# G80_a.net
KiCad netlist of a schematic drawn in EAGLE
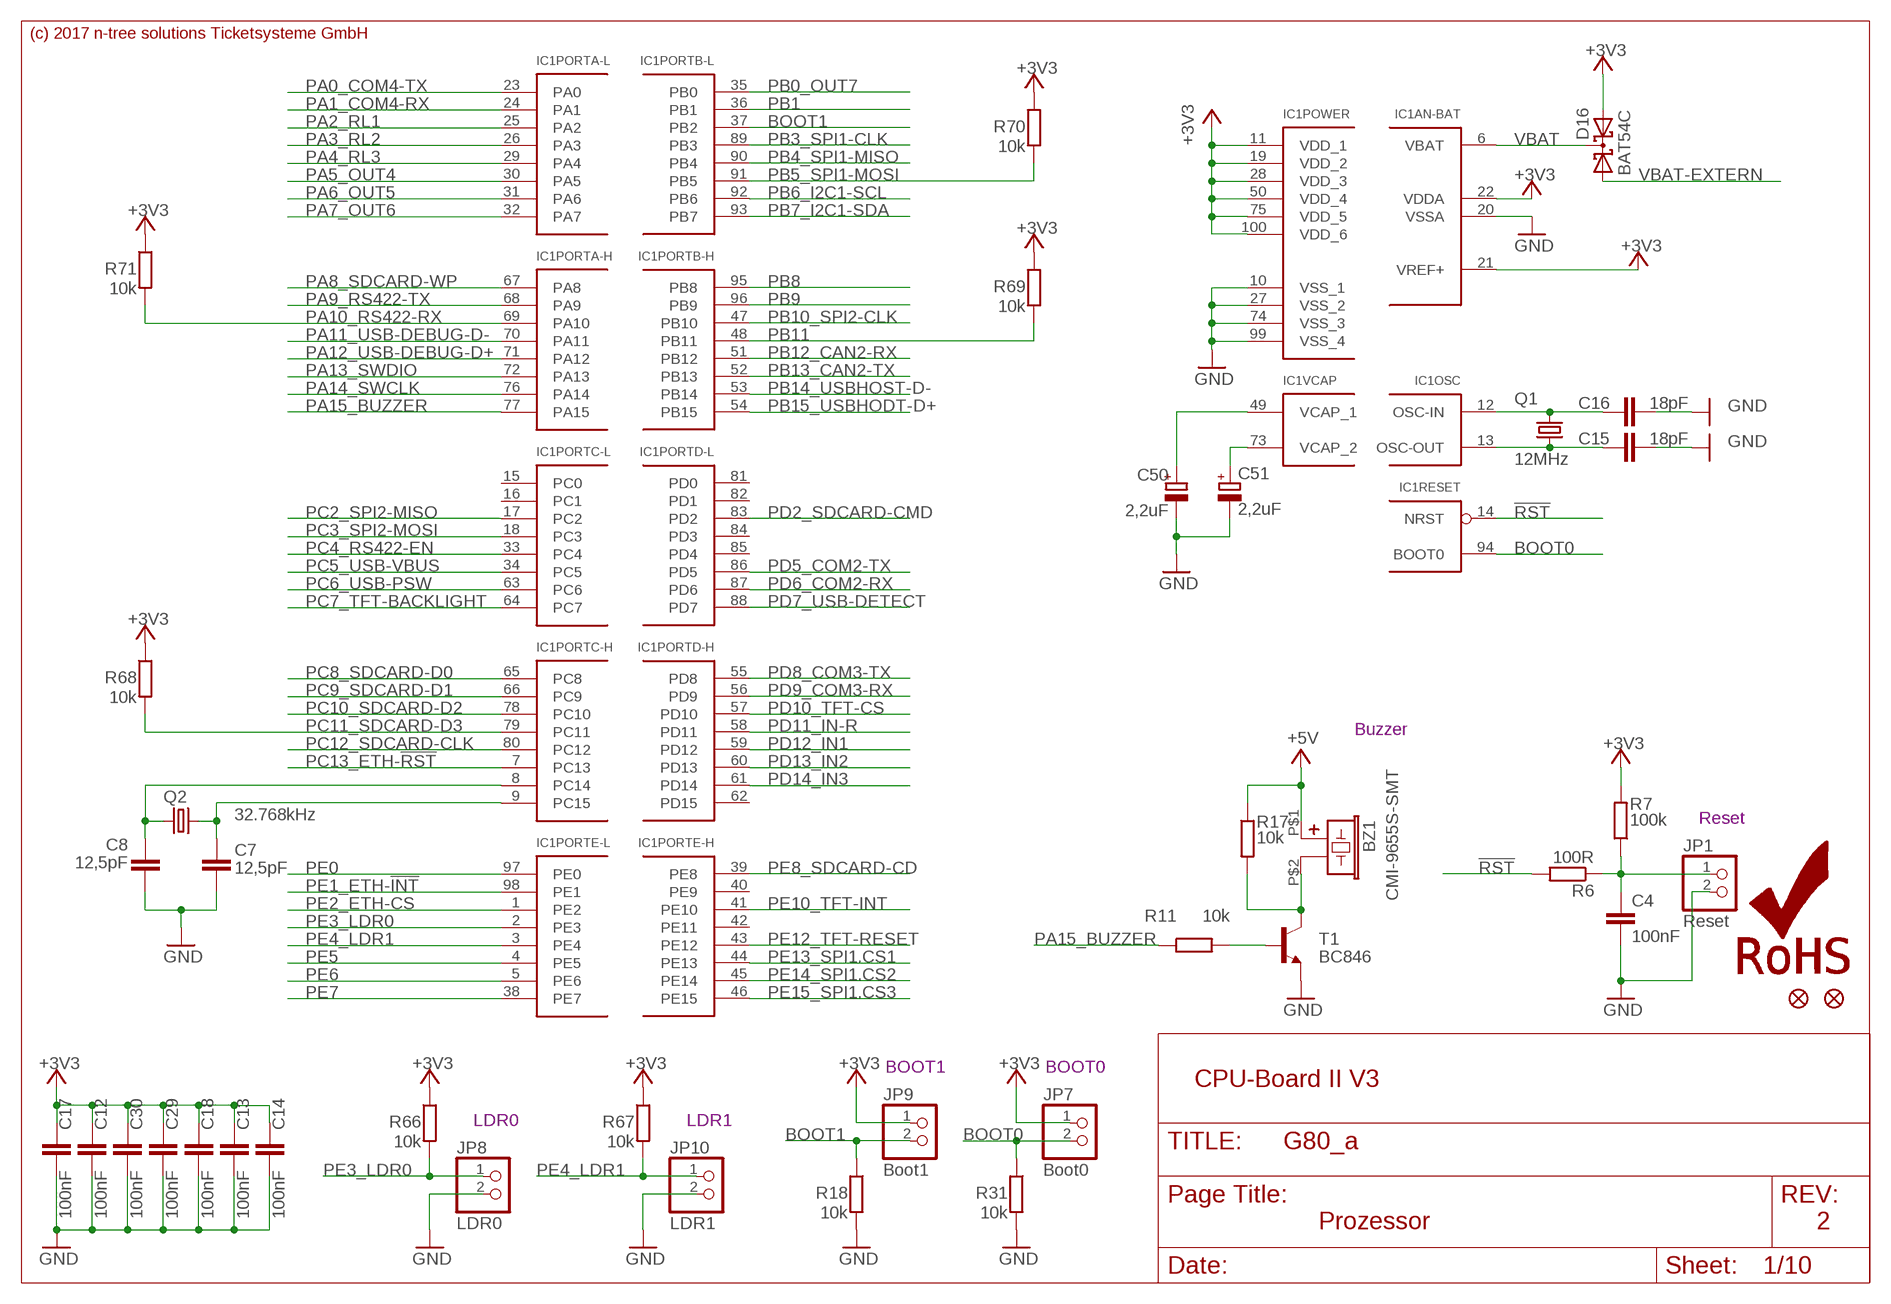
[diagram p0: schematic, sheet 1]
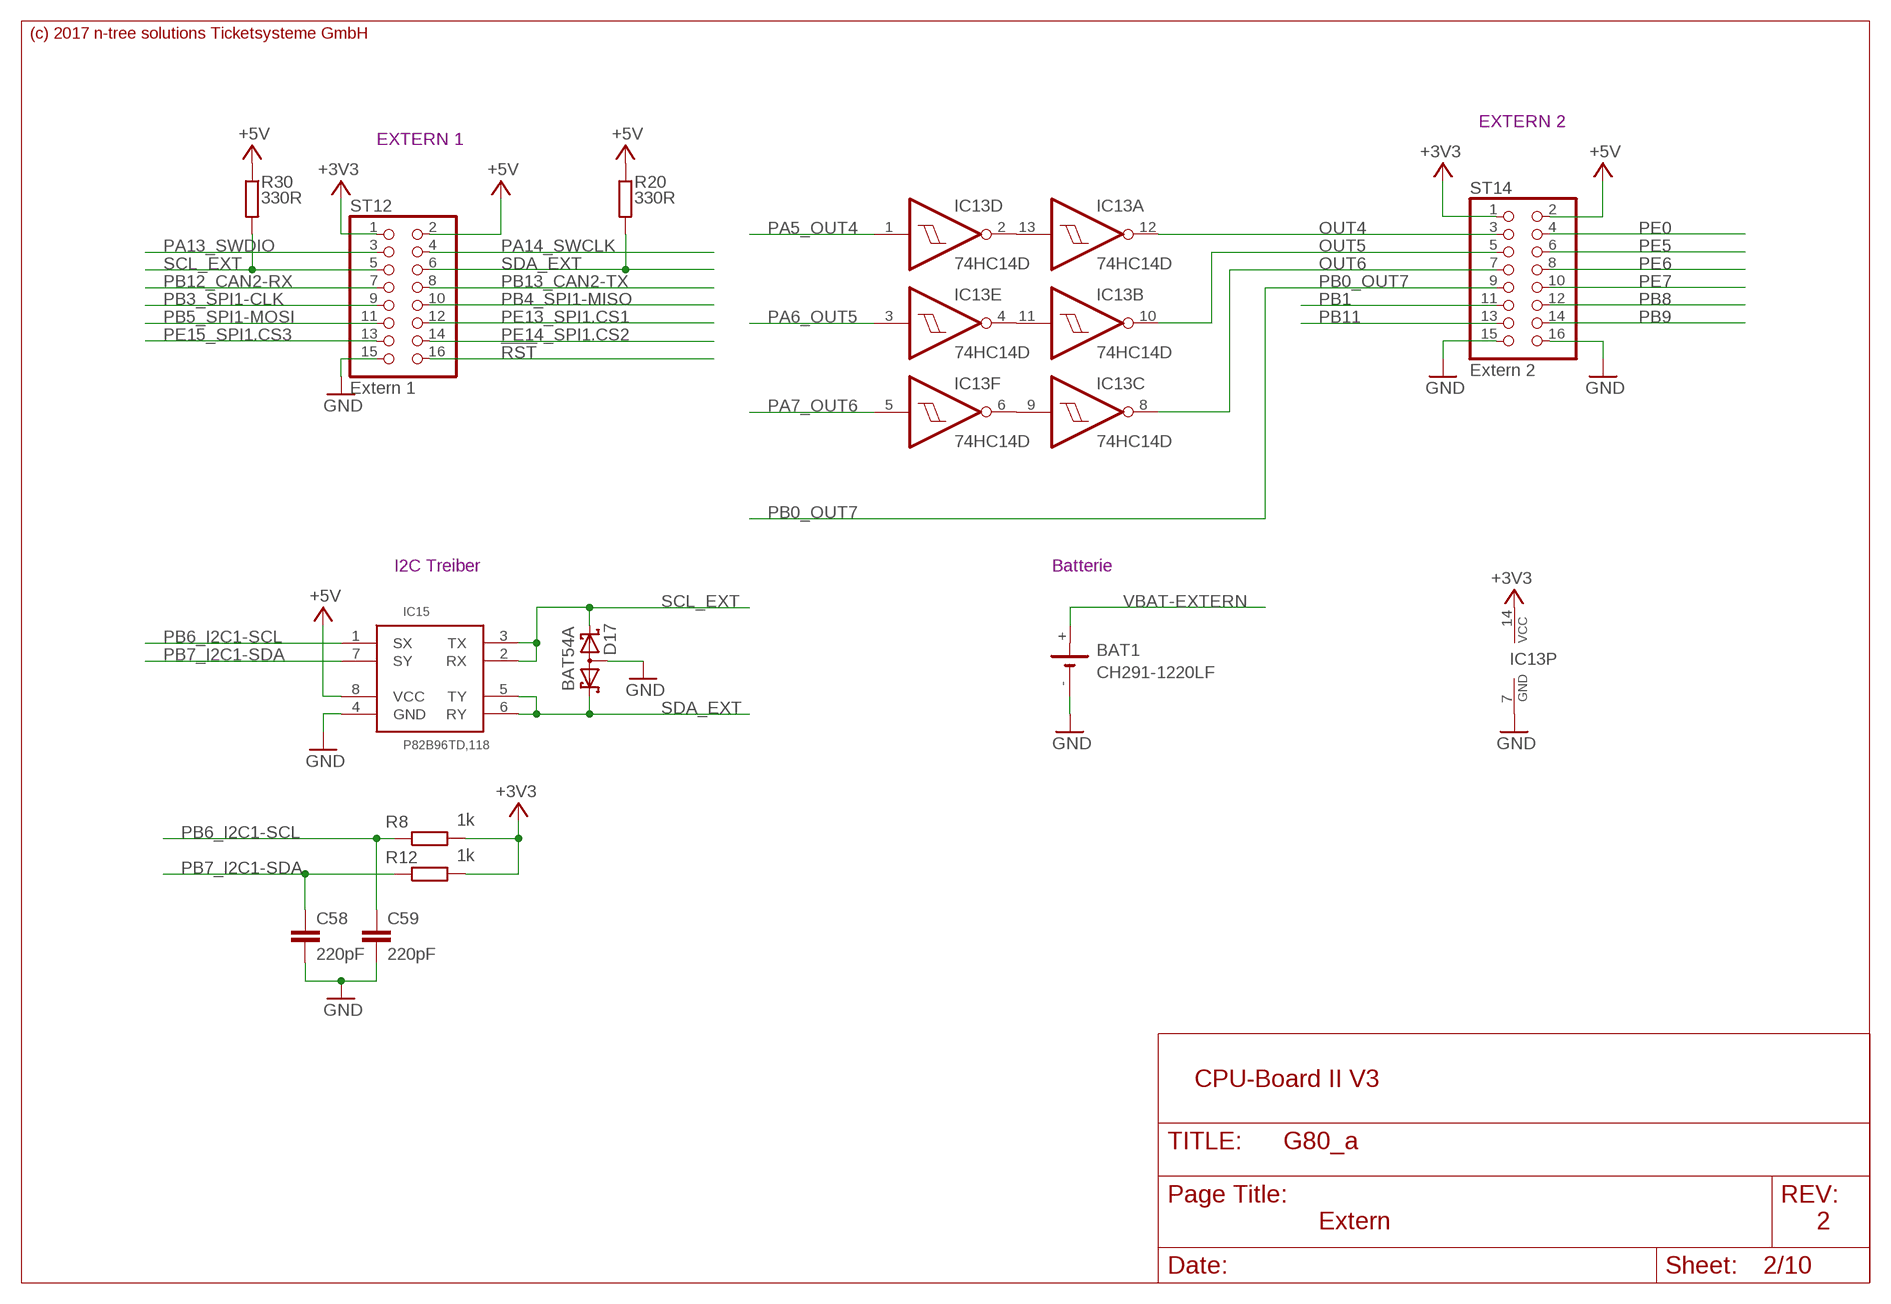
[diagram p1: schematic, sheet 2]
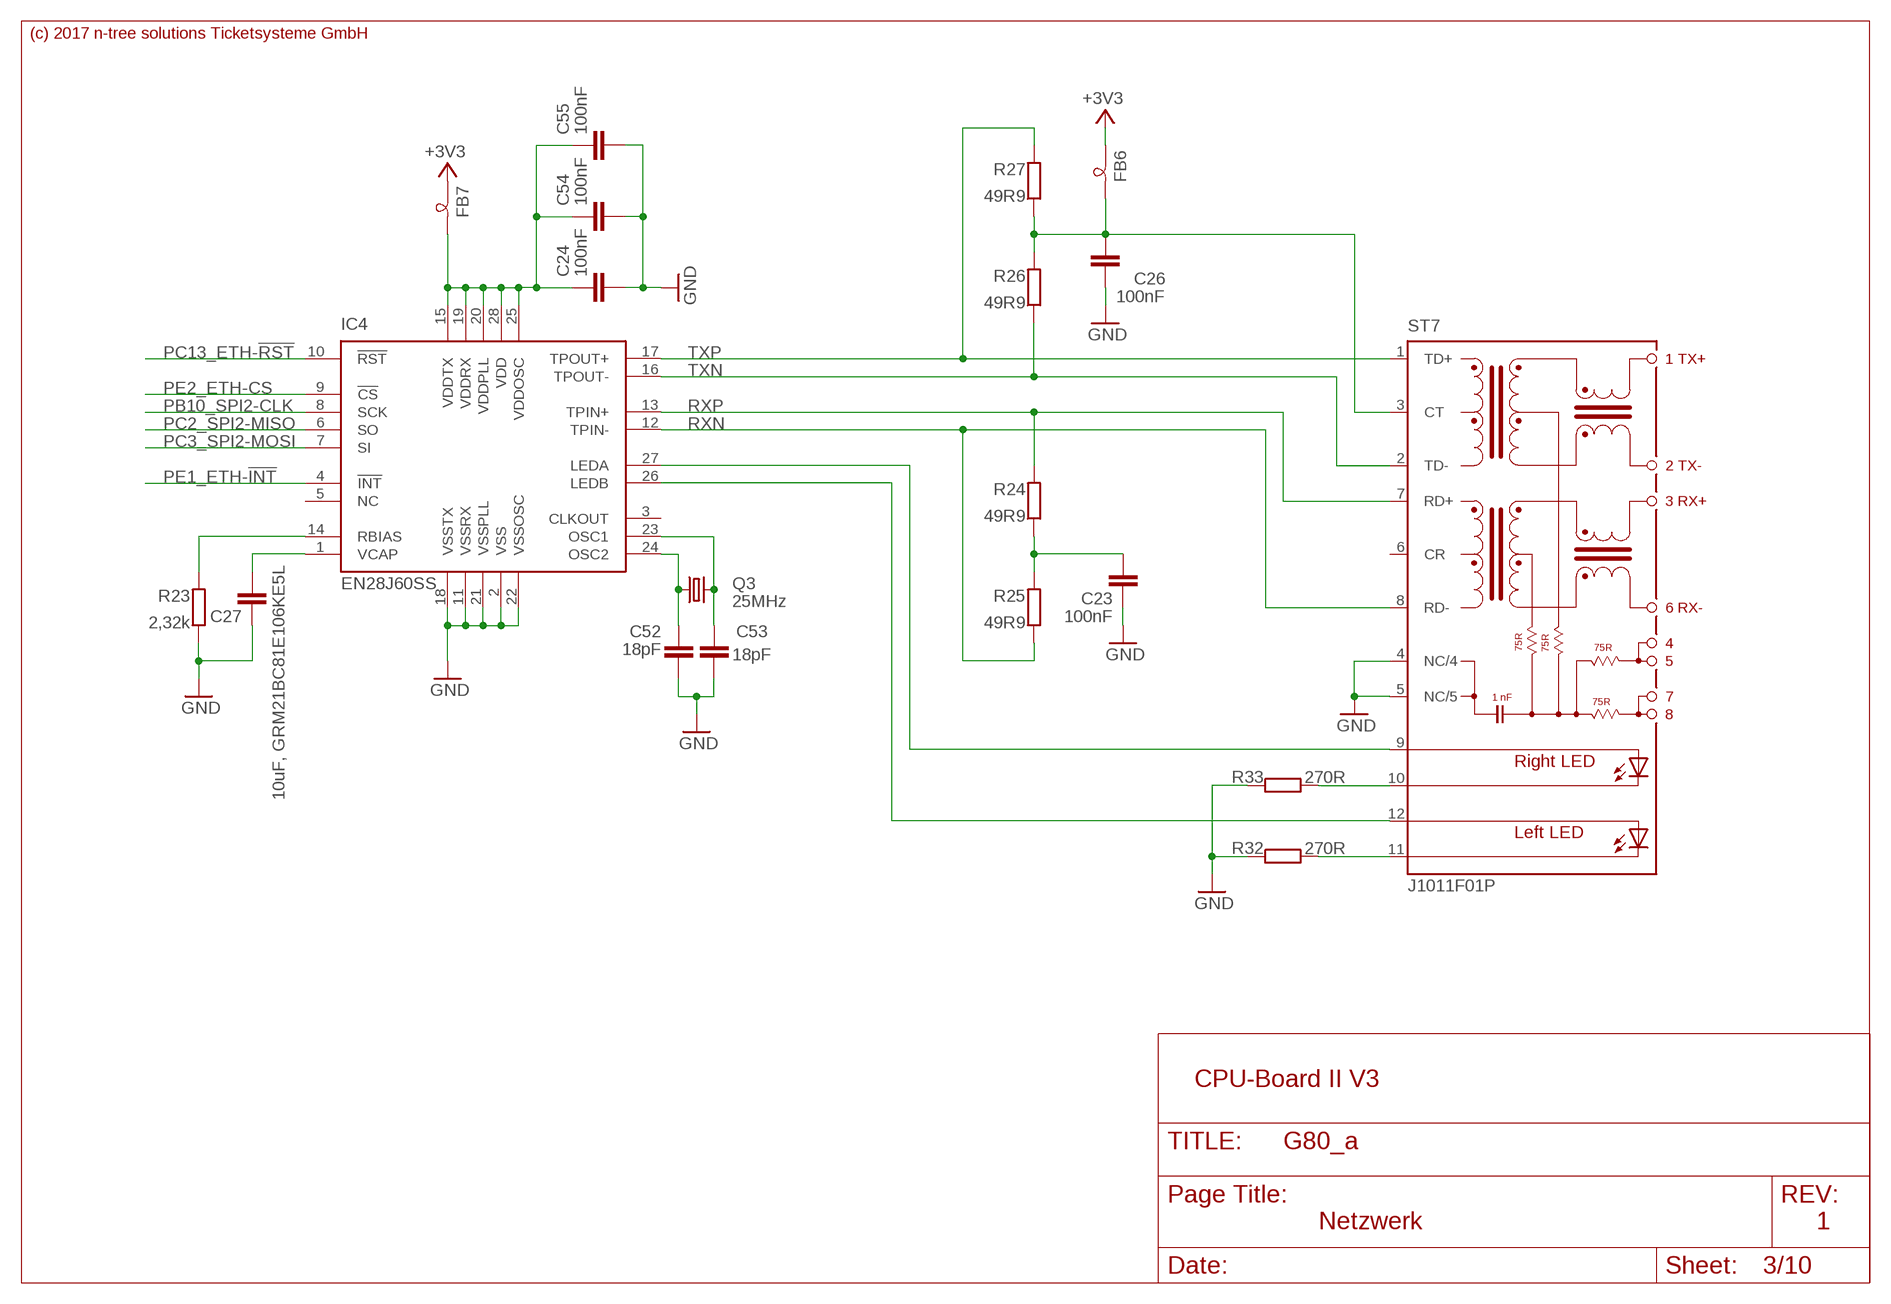
[diagram p2: schematic, sheet 3]
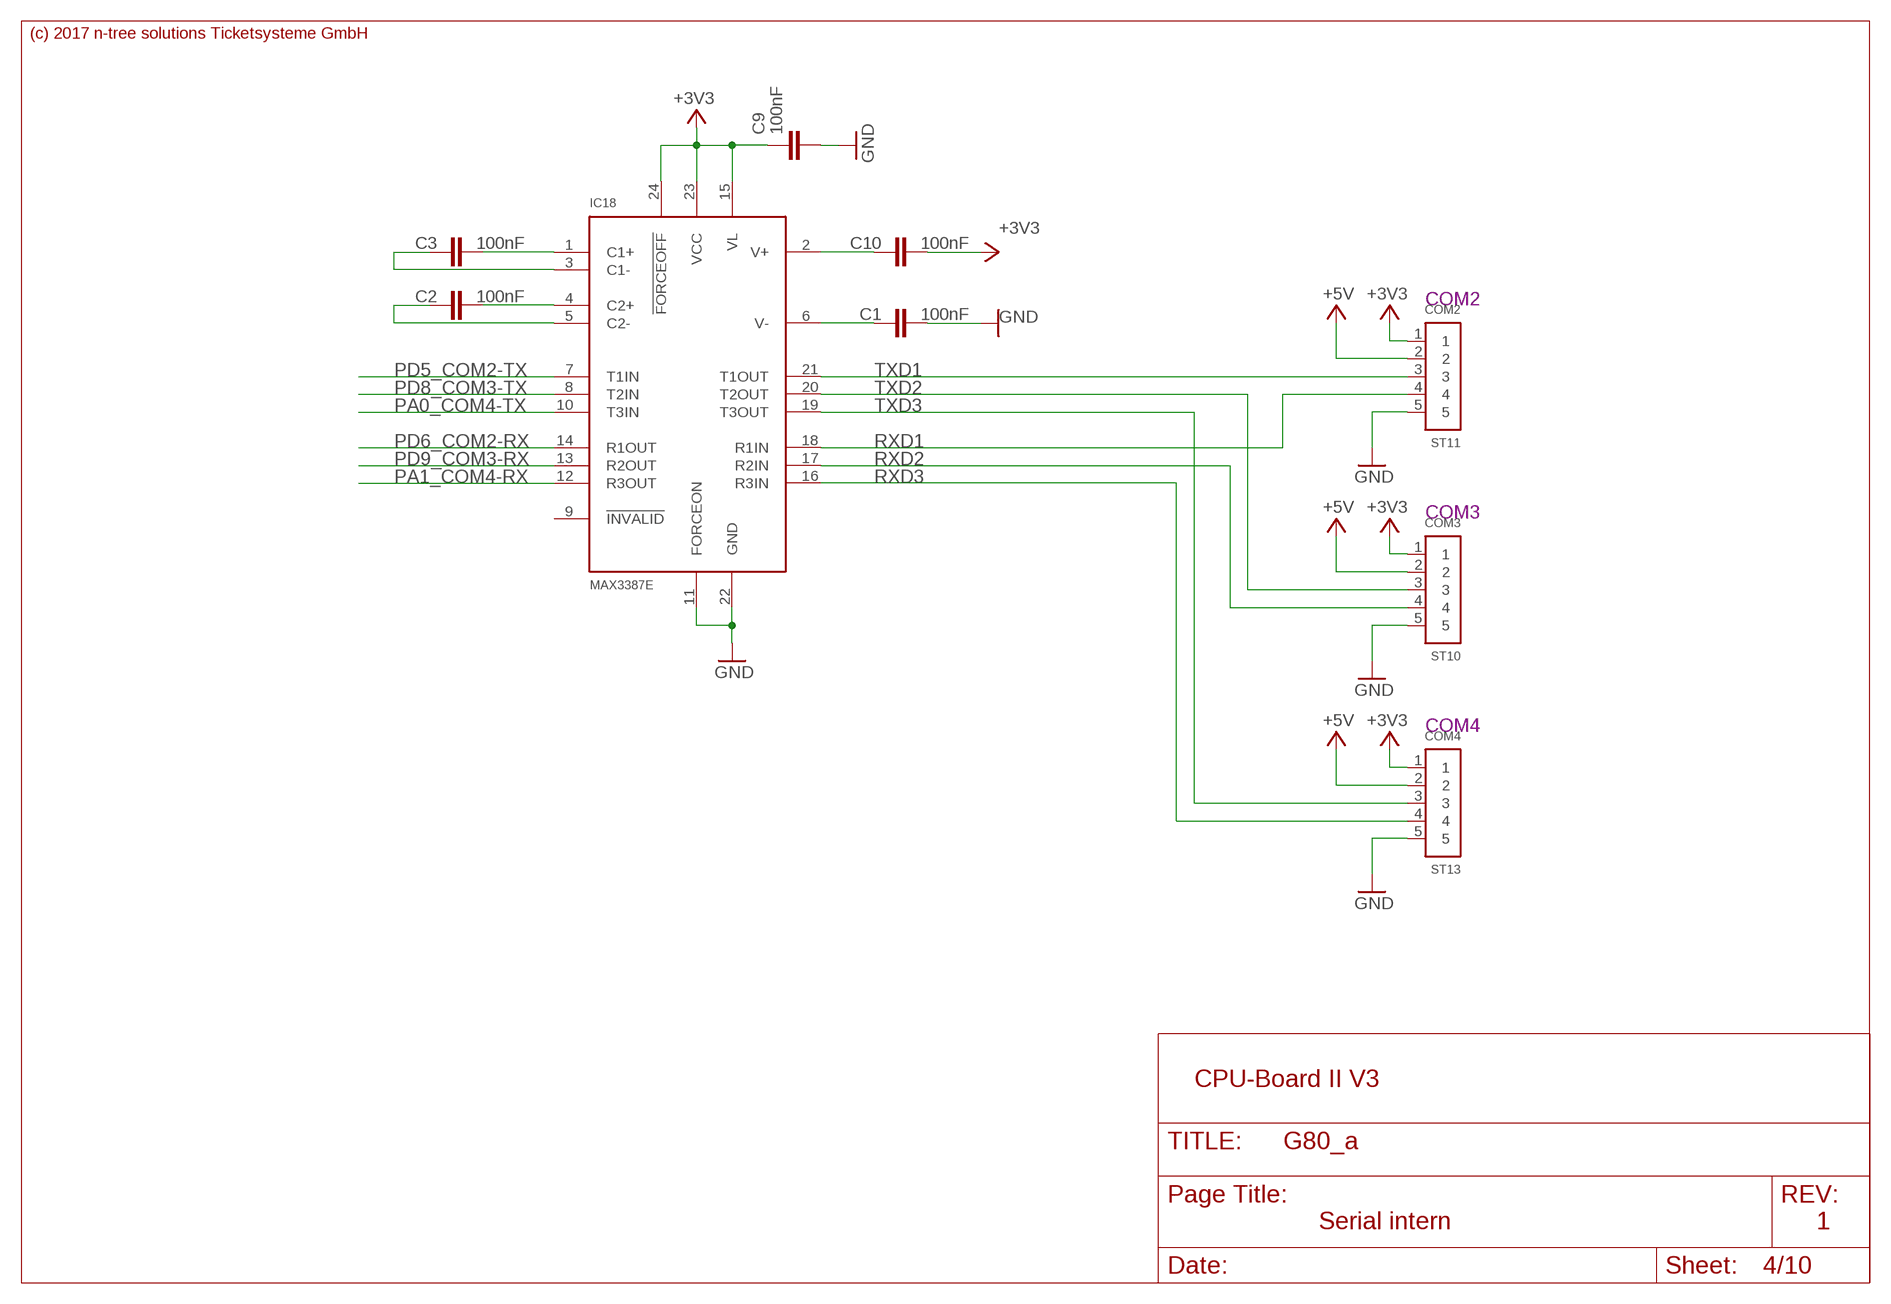
[diagram p3: schematic, sheet 4]
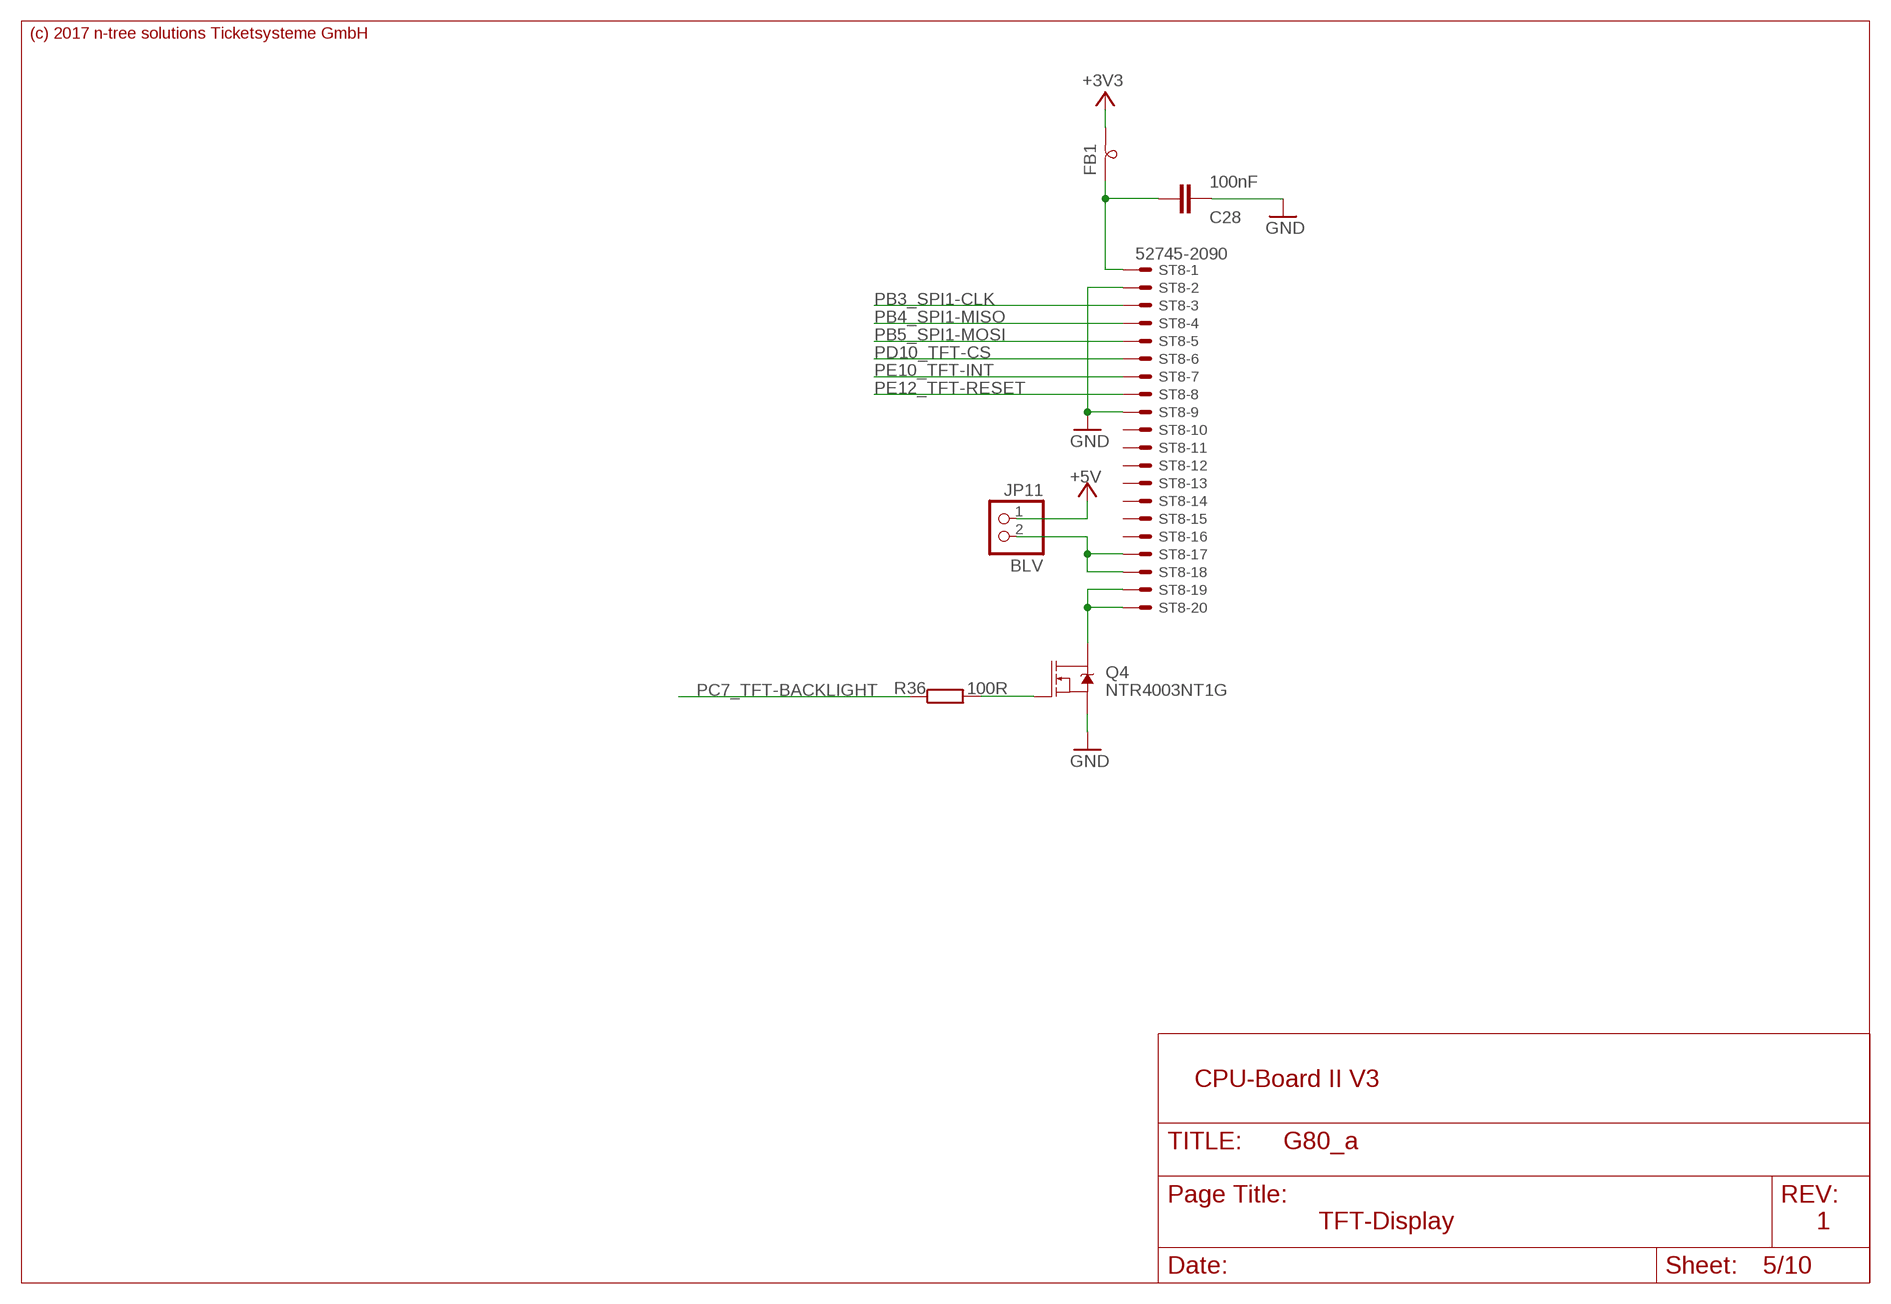
[diagram p4: schematic, sheet 5]
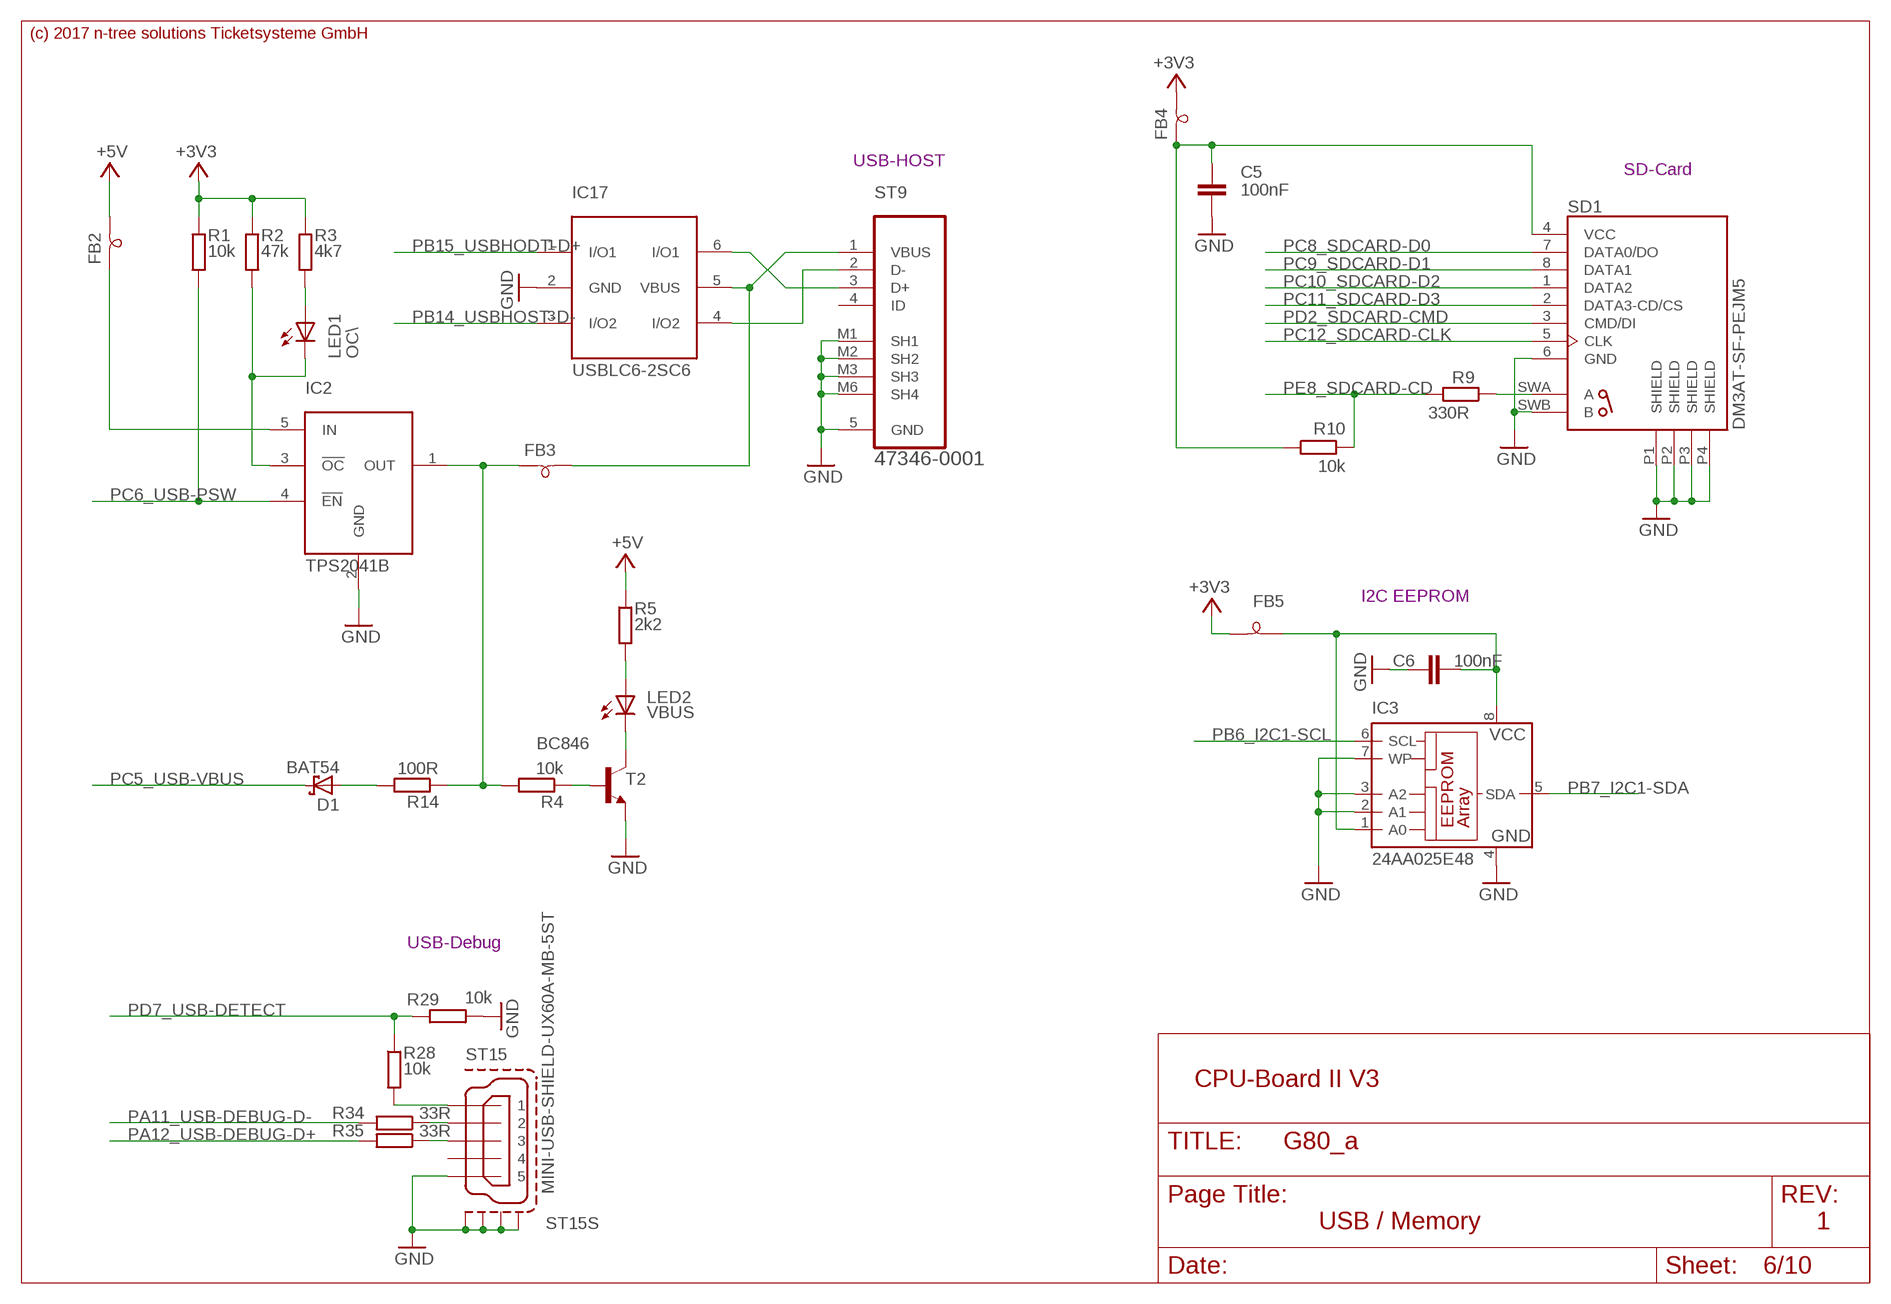
[diagram p5: schematic, sheet 6]
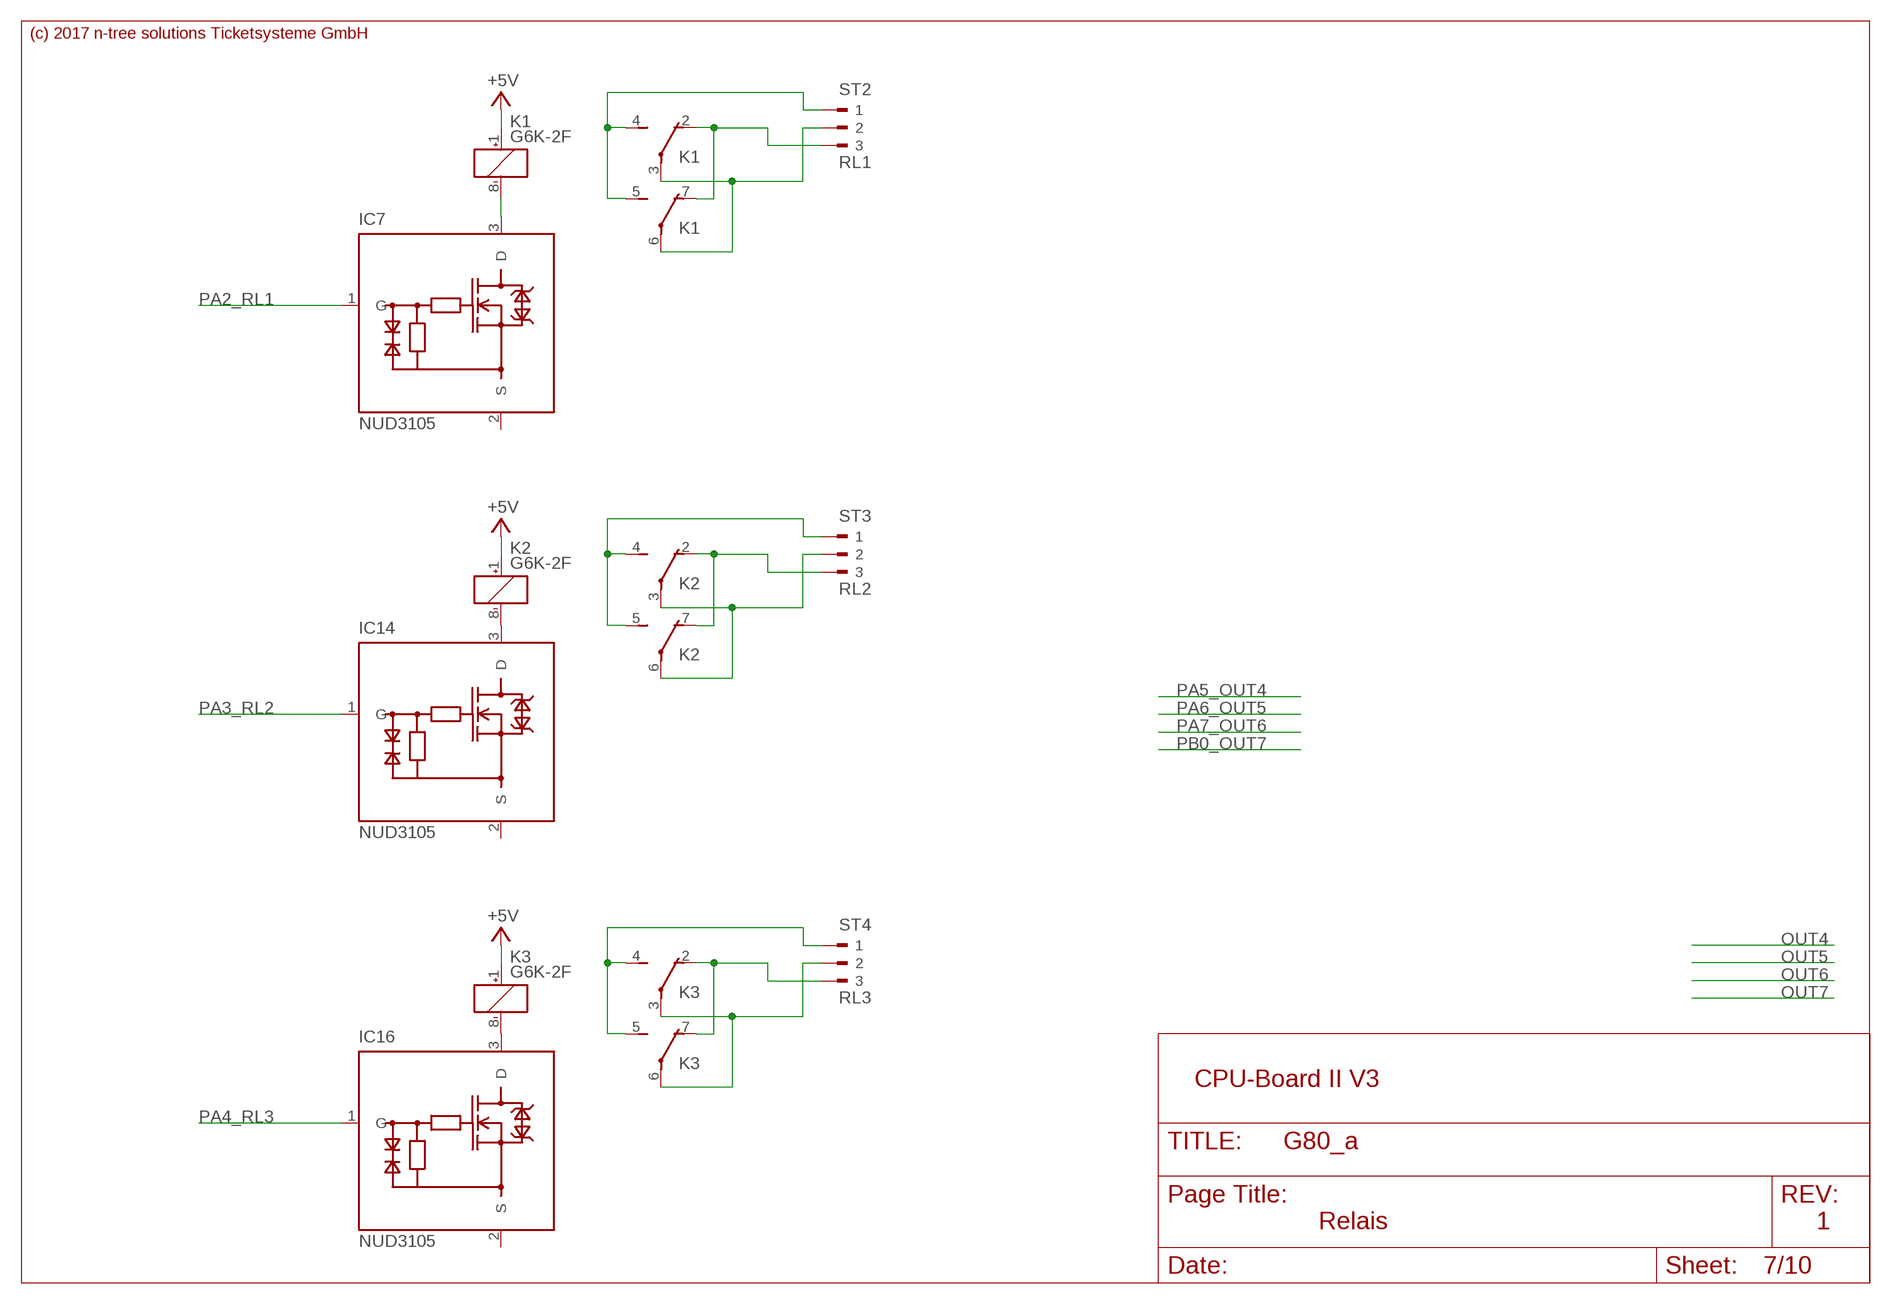
[diagram p6: schematic, sheet 7]
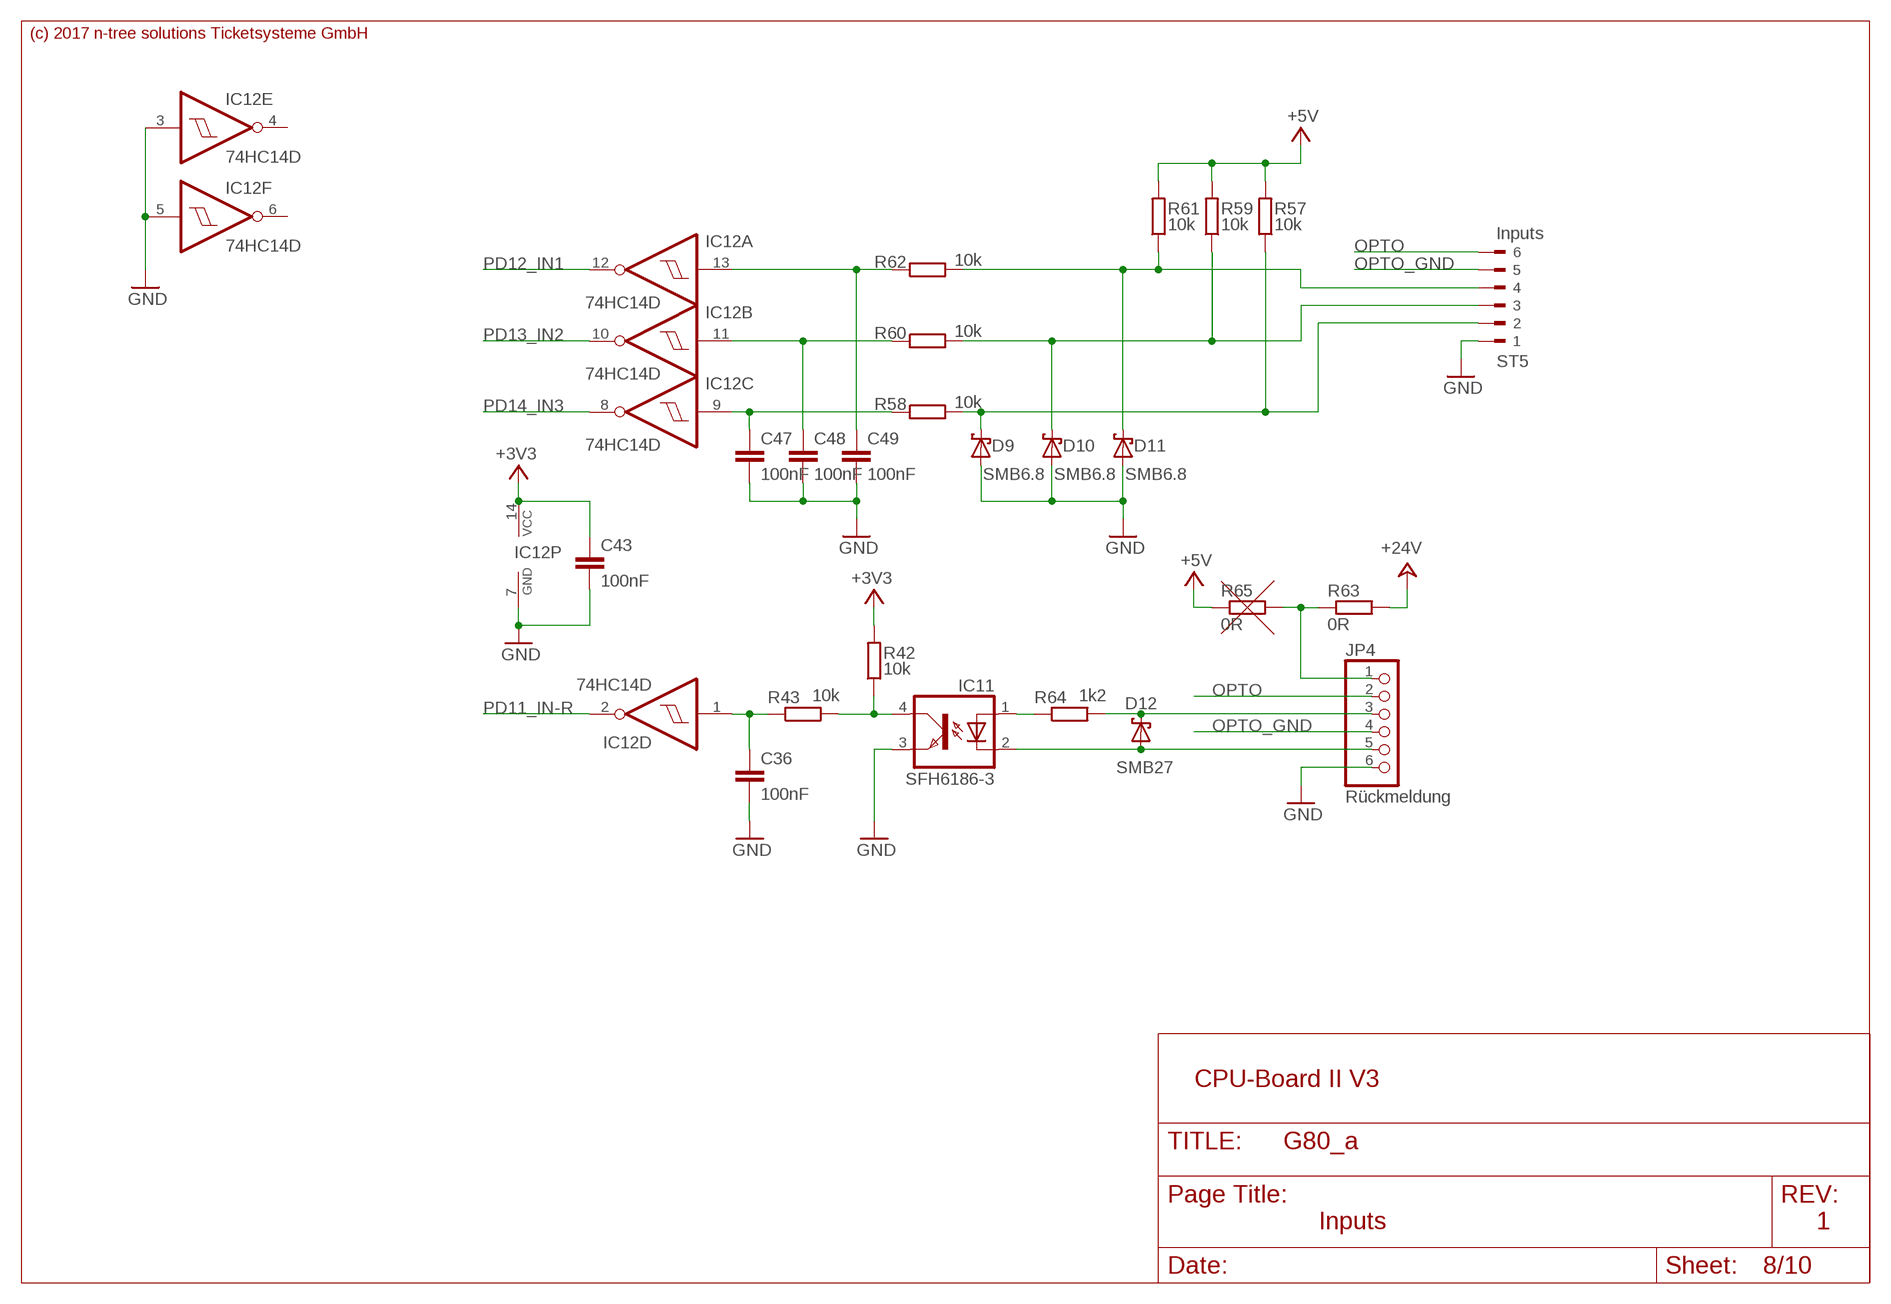
[diagram p7: schematic, sheet 8]
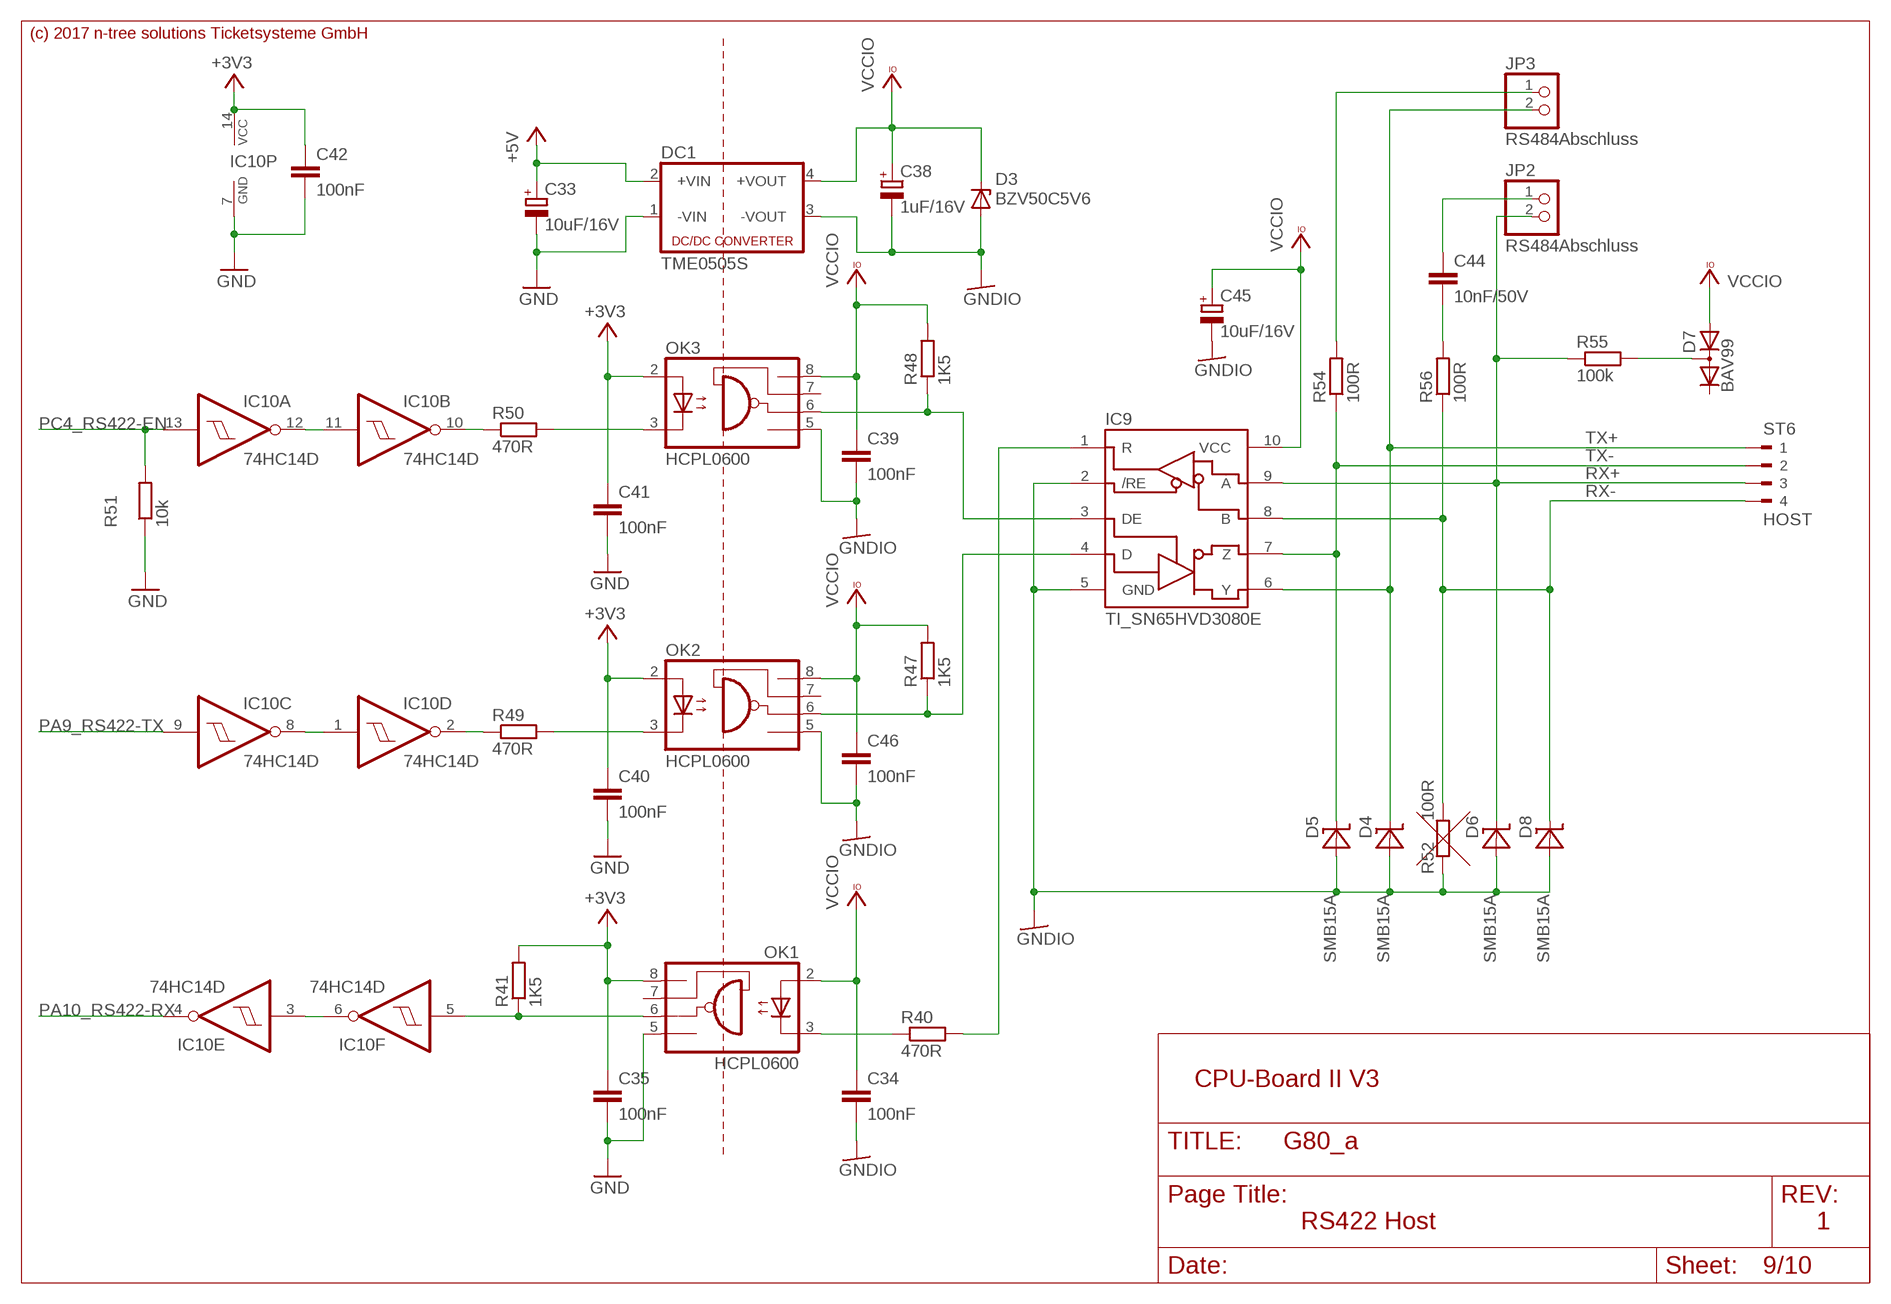
[diagram p8: schematic, sheet 9]
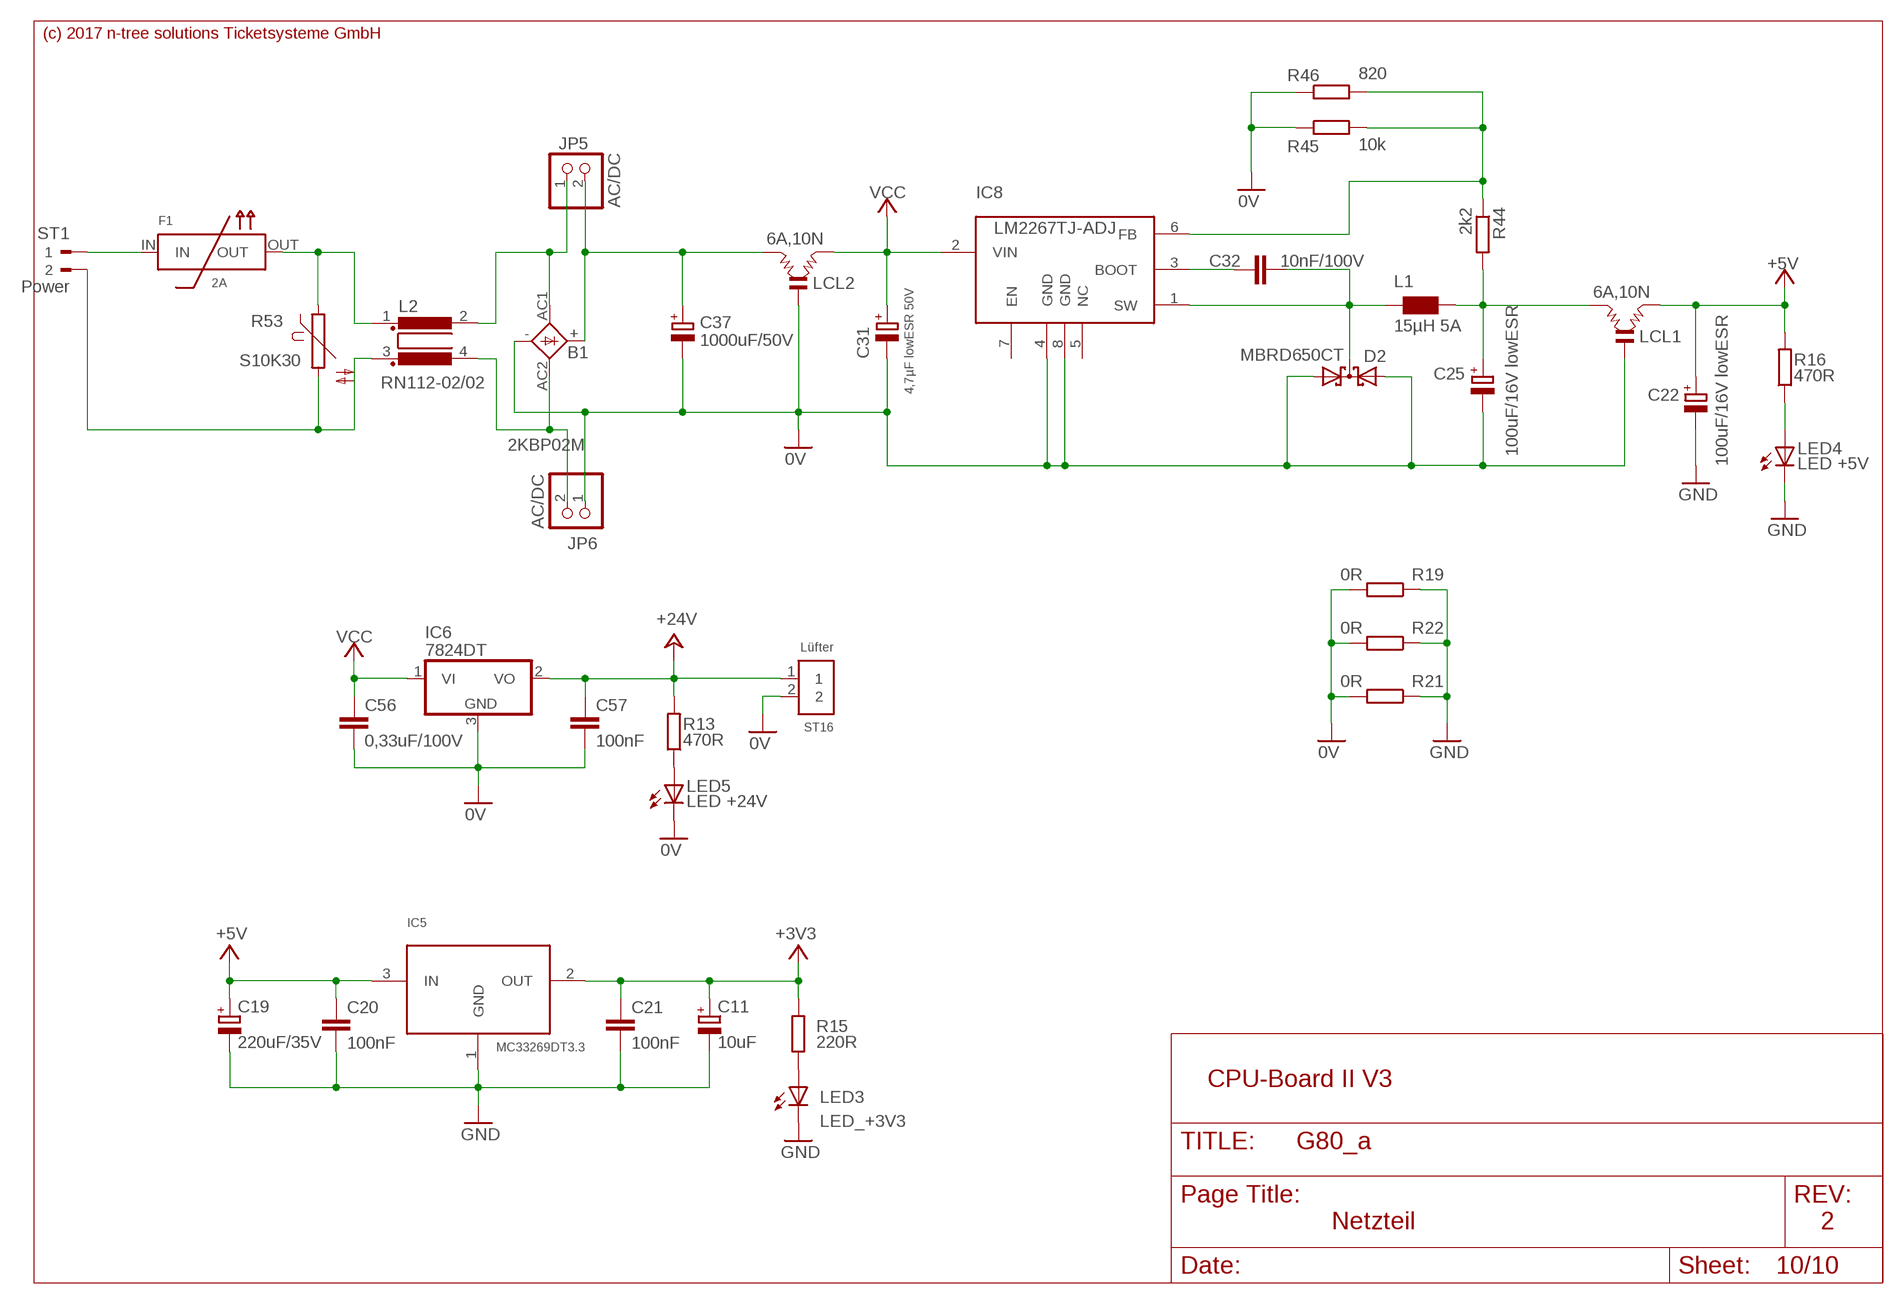
[diagram p9: schematic, sheet 10]

(export (version "E")
  (design (tool "Eeschema 10.0.6"))
  (components
    (comp (ref "C23")
      (value "100nF")
      (footprint "eagle-import:C0603")
      (libsource (lib "eagle-import") (part "C-EUC0603"))
    )
    (comp (ref "C24")
      (value "100nF")
      (footprint "eagle-import:C0603")
      (libsource (lib "eagle-import") (part "C-EUC0603"))
    )
    (comp (ref "C26")
      (value "100nF")
      (footprint "eagle-import:C0603")
      (libsource (lib "eagle-import") (part "C-EUC0603"))
    )
    (comp (ref "C27")
      (value "10uF, GRM21BC81E106KE5L")
      (footprint "eagle-import:C0805")
      (libsource (lib "eagle-import") (part "C-EUC0805"))
    )
    (comp (ref "C52")
      (value "18pF")
      (footprint "eagle-import:C0603")
      (libsource (lib "eagle-import") (part "C-EUC0603"))
    )
    (comp (ref "C53")
      (value "18pF")
      (footprint "eagle-import:C0603")
      (libsource (lib "eagle-import") (part "C-EUC0603"))
    )
    (comp (ref "C54")
      (value "100nF")
      (footprint "eagle-import:C0603")
      (libsource (lib "eagle-import") (part "C-EUC0603"))
    )
    (comp (ref "C55")
      (value "100nF")
      (footprint "eagle-import:C0603")
      (libsource (lib "eagle-import") (part "C-EUC0603"))
    )
    (comp (ref "FB6")
      (value "FERITTE-CHIP-BEAD")
      (footprint "eagle-import:R805")
      (libsource (lib "eagle-import") (part "FERITTE-CHIP-BEAD"))
    )
    (comp (ref "FB7")
      (value "FERITTE-CHIP-BEAD")
      (footprint "eagle-import:R805")
      (libsource (lib "eagle-import") (part "FERITTE-CHIP-BEAD"))
    )
    (comp (ref "IC4")
      (value "EN28J60SS")
      (footprint "eagle-import:SSOP28")
      (libsource (lib "eagle-import") (part "EN28J60SS"))
    )
    (comp (ref "Q3")
      (value "25MHz")
      (footprint "eagle-import:CTS406")
      (libsource (lib "eagle-import") (part "CRYSTALCTS406"))
    )
    (comp (ref "R23")
      (value "2,32k")
      (footprint "eagle-import:R0603")
      (libsource (lib "eagle-import") (part "R-EU_R0603"))
    )
    (comp (ref "R24")
      (value "49R9")
      (footprint "eagle-import:R0603")
      (libsource (lib "eagle-import") (part "R-EU_R0603"))
    )
    (comp (ref "R25")
      (value "49R9")
      (footprint "eagle-import:R0603")
      (libsource (lib "eagle-import") (part "R-EU_R0603"))
    )
    (comp (ref "R26")
      (value "49R9")
      (footprint "eagle-import:R0603")
      (libsource (lib "eagle-import") (part "R-EU_R0603"))
    )
    (comp (ref "R27")
      (value "49R9")
      (footprint "eagle-import:R0603")
      (libsource (lib "eagle-import") (part "R-EU_R0603"))
    )
    (comp (ref "R32")
      (value "270R")
      (footprint "eagle-import:R0603")
      (libsource (lib "eagle-import") (part "R-EU_R0603"))
    )
    (comp (ref "R33")
      (value "270R")
      (footprint "eagle-import:R0603")
      (libsource (lib "eagle-import") (part "R-EU_R0603"))
    )
    (comp (ref "ST7")
      (value "J1011F01P")
      (footprint "eagle-import:J1")
      (libsource (lib "eagle-import") (part "J1011F01P"))
    )
    (comp (ref "C28")
      (value "100nF")
      (footprint "eagle-import:C0603")
      (libsource (lib "eagle-import") (part "C-EUC0603"))
    )
    (comp (ref "FB1")
      (value "FERITTE-CHIP-BEAD")
      (footprint "eagle-import:R805")
      (libsource (lib "eagle-import") (part "FERITTE-CHIP-BEAD"))
    )
    (comp (ref "JP11")
      (value "BLV")
      (footprint "eagle-import:1X02")
      (libsource (lib "eagle-import") (part "PINHD-1X2"))
    )
    (comp (ref "Q4")
      (value "NTR4003NT1G")
      (footprint "eagle-import:SOT23-3")
      (libsource (lib "eagle-import") (part "MOSFET-NCH-BSS138"))
    )
    (comp (ref "R36")
      (value "100R")
      (footprint "eagle-import:R0603")
      (libsource (lib "eagle-import") (part "R-EU_R0603"))
    )
    (comp (ref "ST8")
      (value "52745-2090")
      (footprint "eagle-import:52745-2090")
      (fields (field (name "MF") "WALDOM/MOLEX"))
      (libsource (lib "eagle-import") (part "52745-2090"))
    )
    (comp (ref "C5")
      (value "100nF")
      (footprint "eagle-import:C0603")
      (libsource (lib "eagle-import") (part "C-EUC0603"))
    )
    (comp (ref "C6")
      (value "100nF")
      (footprint "eagle-import:C0603")
      (libsource (lib "eagle-import") (part "C-EUC0603"))
    )
    (comp (ref "D1")
      (value "BAT54")
      (footprint "eagle-import:SOT23")
      (libsource (lib "eagle-import") (part "BAT54"))
    )
    (comp (ref "FB2")
      (value "FERITTE-CHIP-BEAD")
      (footprint "eagle-import:R805")
      (libsource (lib "eagle-import") (part "FERITTE-CHIP-BEAD"))
    )
    (comp (ref "FB3")
      (value "FERITTE-CHIP-BEAD")
      (footprint "eagle-import:R805")
      (libsource (lib "eagle-import") (part "FERITTE-CHIP-BEAD"))
    )
    (comp (ref "FB4")
      (value "FERITTE-CHIP-BEAD")
      (footprint "eagle-import:R805")
      (libsource (lib "eagle-import") (part "FERITTE-CHIP-BEAD"))
    )
    (comp (ref "FB5")
      (value "FERITTE-CHIP-BEAD")
      (footprint "eagle-import:R805")
      (libsource (lib "eagle-import") (part "FERITTE-CHIP-BEAD"))
    )
    (comp (ref "IC2")
      (value "TPS2041B")
      (footprint "eagle-import:SOT23-5")
      (libsource (lib "eagle-import") (part "TPS2041B"))
    )
    (comp (ref "IC3")
      (value "24AA025E48")
      (footprint "eagle-import:SO-08M")
      (fields (field (name "MF") "MICROCHIP") (field (name "MPN") "24AA01-I/SN"))
      (libsource (lib "eagle-import") (part "24SMAA01"))
    )
    (comp (ref "IC17")
      (value "USBLC6-2SC6")
      (footprint "eagle-import:SO23-6L")
      (libsource (lib "eagle-import") (part "USBLC6-2SC6"))
    )
    (comp (ref "LED1")
      (value "OC\\")
      (footprint "eagle-import:CHIPLED_0603")
      (libsource (lib "eagle-import") (part "LEDCHIPLED_0603"))
    )
    (comp (ref "LED2")
      (value "VBUS")
      (footprint "eagle-import:CHIPLED_0603")
      (libsource (lib "eagle-import") (part "LEDCHIPLED_0603"))
    )
    (comp (ref "R1")
      (value "10k")
      (footprint "eagle-import:R0603")
      (libsource (lib "eagle-import") (part "R-EU_R0603"))
    )
    (comp (ref "R2")
      (value "47k")
      (footprint "eagle-import:R0603")
      (libsource (lib "eagle-import") (part "R-EU_R0603"))
    )
    (comp (ref "R3")
      (value "4k7")
      (footprint "eagle-import:R0603")
      (libsource (lib "eagle-import") (part "R-EU_R0603"))
    )
    (comp (ref "R4")
      (value "10k")
      (footprint "eagle-import:R0603")
      (libsource (lib "eagle-import") (part "R-EU_R0603"))
    )
    (comp (ref "R5")
      (value "2k2")
      (footprint "eagle-import:R0603")
      (libsource (lib "eagle-import") (part "R-EU_R0603"))
    )
    (comp (ref "R9")
      (value "330R")
      (footprint "eagle-import:R0603")
      (libsource (lib "eagle-import") (part "R-EU_R0603"))
    )
    (comp (ref "R10")
      (value "10k")
      (footprint "eagle-import:R0603")
      (libsource (lib "eagle-import") (part "R-EU_R0603"))
    )
    (comp (ref "R14")
      (value "100R")
      (footprint "eagle-import:R0603")
      (libsource (lib "eagle-import") (part "R-EU_R0603"))
    )
    (comp (ref "R28")
      (value "10k")
      (footprint "eagle-import:R0603")
      (libsource (lib "eagle-import") (part "R-EU_R0603"))
    )
    (comp (ref "R29")
      (value "10k")
      (footprint "eagle-import:R0603")
      (libsource (lib "eagle-import") (part "R-EU_R0603"))
    )
    (comp (ref "R34")
      (value "33R")
      (footprint "eagle-import:R0603")
      (libsource (lib "eagle-import") (part "R-EU_R0603"))
    )
    (comp (ref "R35")
      (value "33R")
      (footprint "eagle-import:R0603")
      (libsource (lib "eagle-import") (part "R-EU_R0603"))
    )
    (comp (ref "SD1")
      (value "DM3AT-SF-PEJM5")
      (footprint "eagle-import:HRS_DM3AT-SF-PEJM5")
      (fields (field (name "MF") "Hirose"))
      (libsource (lib "eagle-import") (part "DM3AT-SF-PEJM5"))
    )
    (comp (ref "ST9")
      (value "47346-0001")
      (footprint "eagle-import:MOLEX_47346-0001")
      (fields (field (name "MF") "Molex"))
      (libsource (lib "eagle-import") (part "47346-0001"))
    )
    (comp (ref "ST15")
      (value "MINI-USB-SHIELD-UX60A-MB-5ST")
      (footprint "eagle-import:UX60A-MB-5ST")
      (libsource (lib "eagle-import") (part "MINI-USB-SHIELD-UX60A-MB-5ST"))
    )
    (comp (ref "T2")
      (value "BC846")
      (footprint "eagle-import:SOT23-BEC")
      (libsource (lib "eagle-import") (part "-NPN-SOT23-BECBC846"))
    )
    (comp (ref "C33")
      (value "10uF/16V")
      (footprint "eagle-import:C_6032-28R")
      (libsource (lib "eagle-import") (part "CPOL-EUC/6032-28R"))
    )
    (comp (ref "C34")
      (value "100nF")
      (footprint "eagle-import:C0603")
      (libsource (lib "eagle-import") (part "C-EUC0603"))
    )
    (comp (ref "C35")
      (value "100nF")
      (footprint "eagle-import:C0603")
      (libsource (lib "eagle-import") (part "C-EUC0603"))
    )
    (comp (ref "C38")
      (value "1uF/16V")
      (footprint "eagle-import:A_3216-18R")
      (libsource (lib "eagle-import") (part "CPOL-EUA/3216-18R"))
    )
    (comp (ref "C39")
      (value "100nF")
      (footprint "eagle-import:C0603")
      (libsource (lib "eagle-import") (part "C-EUC0603"))
    )
    (comp (ref "C40")
      (value "100nF")
      (footprint "eagle-import:C0603")
      (libsource (lib "eagle-import") (part "C-EUC0603"))
    )
    (comp (ref "C41")
      (value "100nF")
      (footprint "eagle-import:C0603")
      (libsource (lib "eagle-import") (part "C-EUC0603"))
    )
    (comp (ref "C42")
      (value "100nF")
      (footprint "eagle-import:C0603")
      (libsource (lib "eagle-import") (part "C-EUC0603"))
    )
    (comp (ref "C44")
      (value "10nF/50V")
      (footprint "eagle-import:C0603")
      (libsource (lib "eagle-import") (part "C-EUC0603"))
    )
    (comp (ref "C45")
      (value "10uF/16V")
      (footprint "eagle-import:C_6032-28R")
      (libsource (lib "eagle-import") (part "CPOL-EUC/6032-28R"))
    )
    (comp (ref "C46")
      (value "100nF")
      (footprint "eagle-import:C0603")
      (libsource (lib "eagle-import") (part "C-EUC0603"))
    )
    (comp (ref "D3")
      (value "BZV50C5V6")
      (footprint "eagle-import:SOD80C")
      (libsource (lib "eagle-import") (part "ZENER-DIODESOD80C"))
    )
    (comp (ref "D4")
      (value "SMB15A")
      (footprint "eagle-import:SMB")
      (libsource (lib "eagle-import") (part "SMB15A"))
    )
    (comp (ref "D5")
      (value "SMB15A")
      (footprint "eagle-import:SMB")
      (libsource (lib "eagle-import") (part "SMB15A"))
    )
    (comp (ref "D6")
      (value "SMB15A")
      (footprint "eagle-import:SMB")
      (libsource (lib "eagle-import") (part "SMB15A"))
    )
    (comp (ref "D7")
      (value "BAV99")
      (footprint "eagle-import:SOT23")
      (libsource (lib "eagle-import") (part "BAV99"))
    )
    (comp (ref "D8")
      (value "SMB15A")
      (footprint "eagle-import:SMB")
      (libsource (lib "eagle-import") (part "SMB15A"))
    )
    (comp (ref "DC1")
      (value "TME0505S")
      (footprint "eagle-import:NME")
      (libsource (lib "eagle-import") (part "TME0505S"))
    )
    (comp (ref "IC9")
      (value "TI_SN65HVD3080E")
      (footprint "eagle-import:TI_SN65HVD3080E")
      (libsource (lib "eagle-import") (part "TI_SN65HVD3080E"))
    )
    (comp (ref "IC10")
      (value "74HC14D")
      (footprint "eagle-import:SO14")
      (libsource (lib "eagle-import") (part "7414DHC"))
    )
    (comp (ref "JP2")
      (value "RS484Abschluss")
      (footprint "eagle-import:1X02")
      (libsource (lib "eagle-import") (part "PINHD-1X2"))
    )
    (comp (ref "JP3")
      (value "RS484Abschluss")
      (footprint "eagle-import:1X02")
      (libsource (lib "eagle-import") (part "PINHD-1X2"))
    )
    (comp (ref "OK1")
      (value "HCPL0600")
      (footprint "eagle-import:SOIC08")
      (fields (field (name "MF") "AGILENT TECHNOLOGIES") (field (name "MPN") "HCPL-0600-000E"))
      (libsource (lib "eagle-import") (part "HCPL0600"))
    )
    (comp (ref "OK2")
      (value "HCPL0600")
      (footprint "eagle-import:SOIC08")
      (fields (field (name "MF") "AGILENT TECHNOLOGIES") (field (name "MPN") "HCPL-0600-000E"))
      (libsource (lib "eagle-import") (part "HCPL0600"))
    )
    (comp (ref "OK3")
      (value "HCPL0600")
      (footprint "eagle-import:SOIC08")
      (fields (field (name "MF") "AGILENT TECHNOLOGIES") (field (name "MPN") "HCPL-0600-000E"))
      (libsource (lib "eagle-import") (part "HCPL0600"))
    )
    (comp (ref "R40")
      (value "470R")
      (footprint "eagle-import:R0603")
      (libsource (lib "eagle-import") (part "R-EU_R0603"))
    )
    (comp (ref "R41")
      (value "1K5")
      (footprint "eagle-import:R0603")
      (libsource (lib "eagle-import") (part "R-EU_R0603"))
    )
    (comp (ref "R47")
      (value "1K5")
      (footprint "eagle-import:R0603")
      (libsource (lib "eagle-import") (part "R-EU_R0603"))
    )
    (comp (ref "R48")
      (value "1K5")
      (footprint "eagle-import:R0603")
      (libsource (lib "eagle-import") (part "R-EU_R0603"))
    )
    (comp (ref "R49")
      (value "470R")
      (footprint "eagle-import:R0603")
      (libsource (lib "eagle-import") (part "R-EU_R0603"))
    )
    (comp (ref "R50")
      (value "470R")
      (footprint "eagle-import:R0603")
      (libsource (lib "eagle-import") (part "R-EU_R0603"))
    )
    (comp (ref "R51")
      (value "10k")
      (footprint "eagle-import:R0603")
      (libsource (lib "eagle-import") (part "R-EU_R0603"))
    )
    (comp (ref "R52")
      (value "100R")
      (footprint "eagle-import:R0603")
      (libsource (lib "eagle-import") (part "R-EU_R0603"))
    )
    (comp (ref "R54")
      (value "100R")
      (footprint "eagle-import:R0603")
      (libsource (lib "eagle-import") (part "R-EU_R0603"))
    )
    (comp (ref "R55")
      (value "100k")
      (footprint "eagle-import:R0603")
      (libsource (lib "eagle-import") (part "R-EU_R0603"))
    )
    (comp (ref "R56")
      (value "100R")
      (footprint "eagle-import:R0603")
      (libsource (lib "eagle-import") (part "R-EU_R0603"))
    )
    (comp (ref "ST6")
      (value "HOST")
      (footprint "eagle-import:180G-4")
      (libsource (lib "eagle-import") (part "180G-4"))
    )
    (comp (ref "C36")
      (value "100nF")
      (footprint "eagle-import:C0603")
      (libsource (lib "eagle-import") (part "C-EUC0603"))
    )
    (comp (ref "C43")
      (value "100nF")
      (footprint "eagle-import:C0603")
      (libsource (lib "eagle-import") (part "C-EUC0603"))
    )
    (comp (ref "C47")
      (value "100nF")
      (footprint "eagle-import:C0603")
      (libsource (lib "eagle-import") (part "C-EUC0603"))
    )
    (comp (ref "C48")
      (value "100nF")
      (footprint "eagle-import:C0603")
      (libsource (lib "eagle-import") (part "C-EUC0603"))
    )
    (comp (ref "C49")
      (value "100nF")
      (footprint "eagle-import:C0603")
      (libsource (lib "eagle-import") (part "C-EUC0603"))
    )
    (comp (ref "D9")
      (value "SMB6.8")
      (footprint "eagle-import:SMB")
      (libsource (lib "eagle-import") (part "SCHOTTKY-DIODESMD"))
    )
    (comp (ref "D10")
      (value "SMB6.8")
      (footprint "eagle-import:SMB")
      (libsource (lib "eagle-import") (part "SCHOTTKY-DIODESMD"))
    )
    (comp (ref "D11")
      (value "SMB6.8")
      (footprint "eagle-import:SMB")
      (libsource (lib "eagle-import") (part "SCHOTTKY-DIODESMD"))
    )
    (comp (ref "D12")
      (value "SMB27")
      (footprint "eagle-import:SMB")
      (libsource (lib "eagle-import") (part "SCHOTTKY-DIODESMD"))
    )
    (comp (ref "IC11")
      (value "SFH6186-3")
      (footprint "eagle-import:SO-6_4")
      (libsource (lib "eagle-import") (part "SHF6186-3"))
    )
    (comp (ref "IC12")
      (value "74HC14D")
      (footprint "eagle-import:SO14")
      (libsource (lib "eagle-import") (part "7414DHC"))
    )
    (comp (ref "JP4")
      (value "Rückmeldung")
      (footprint "eagle-import:1X06")
      (libsource (lib "eagle-import") (part "PINHD-1X6"))
    )
    (comp (ref "R42")
      (value "10k")
      (footprint "eagle-import:R0603")
      (libsource (lib "eagle-import") (part "R-EU_R0603"))
    )
    (comp (ref "R43")
      (value "10k")
      (footprint "eagle-import:R0603")
      (libsource (lib "eagle-import") (part "R-EU_R0603"))
    )
    (comp (ref "R57")
      (value "10k")
      (footprint "eagle-import:R0603")
      (libsource (lib "eagle-import") (part "R-EU_R0603"))
    )
    (comp (ref "R58")
      (value "10k")
      (footprint "eagle-import:R0603")
      (libsource (lib "eagle-import") (part "R-EU_R0603"))
    )
    (comp (ref "R59")
      (value "10k")
      (footprint "eagle-import:R0603")
      (libsource (lib "eagle-import") (part "R-EU_R0603"))
    )
    (comp (ref "R60")
      (value "10k")
      (footprint "eagle-import:R0603")
      (libsource (lib "eagle-import") (part "R-EU_R0603"))
    )
    (comp (ref "R61")
      (value "10k")
      (footprint "eagle-import:R0603")
      (libsource (lib "eagle-import") (part "R-EU_R0603"))
    )
    (comp (ref "R62")
      (value "10k")
      (footprint "eagle-import:R0603")
      (libsource (lib "eagle-import") (part "R-EU_R0603"))
    )
    (comp (ref "R63")
      (value "0R")
      (footprint "eagle-import:R0603")
      (libsource (lib "eagle-import") (part "R-EU_R0603"))
    )
    (comp (ref "R64")
      (value "1k2")
      (footprint "eagle-import:R0603")
      (libsource (lib "eagle-import") (part "R-EU_R0603"))
    )
    (comp (ref "R65")
      (value "0R")
      (footprint "eagle-import:R0603")
      (libsource (lib "eagle-import") (part "R-EU_R0603"))
    )
    (comp (ref "ST5")
      (value "Inputs")
      (footprint "eagle-import:180G-6")
      (libsource (lib "eagle-import") (part "180G-6"))
    )
    (comp (ref "BAT1")
      (value "CH291-1220LF")
      (footprint "eagle-import:CH291-1220LF")
      (libsource (lib "eagle-import") (part "CH291-1220LF"))
    )
    (comp (ref "C58")
      (value "220pF")
      (footprint "eagle-import:C0603")
      (libsource (lib "eagle-import") (part "C-EUC0603"))
    )
    (comp (ref "C59")
      (value "220pF")
      (footprint "eagle-import:C0603")
      (libsource (lib "eagle-import") (part "C-EUC0603"))
    )
    (comp (ref "D17")
      (value "BAT54A")
      (footprint "eagle-import:SOT23")
      (libsource (lib "eagle-import") (part "BAT54A"))
    )
    (comp (ref "IC13")
      (value "74HC14D")
      (footprint "eagle-import:SO14")
      (libsource (lib "eagle-import") (part "7414DHC"))
    )
    (comp (ref "IC15")
      (value "P82B96TD,118")
      (footprint "eagle-import:SO08")
      (libsource (lib "eagle-import") (part "P82B96'SO8'"))
    )
    (comp (ref "R8")
      (value "1k")
      (footprint "eagle-import:R0603")
      (libsource (lib "eagle-import") (part "R-EU_R0603"))
    )
    (comp (ref "R12")
      (value "1k")
      (footprint "eagle-import:R0603")
      (libsource (lib "eagle-import") (part "R-EU_R0603"))
    )
    (comp (ref "R20")
      (value "330R")
      (footprint "eagle-import:R0603")
      (libsource (lib "eagle-import") (part "R-EU_R0603"))
    )
    (comp (ref "R30")
      (value "330R")
      (footprint "eagle-import:R0603")
      (libsource (lib "eagle-import") (part "R-EU_R0603"))
    )
    (comp (ref "ST12")
      (value "Extern 1")
      (footprint "eagle-import:2X08")
      (libsource (lib "eagle-import") (part "PINHD-2X8"))
    )
    (comp (ref "ST14")
      (value "Extern 2")
      (footprint "eagle-import:2X08")
      (libsource (lib "eagle-import") (part "PINHD-2X8"))
    )
    (comp (ref "C1")
      (value "100nF")
      (footprint "eagle-import:C0603")
      (libsource (lib "eagle-import") (part "C-EUC0603"))
    )
    (comp (ref "C2")
      (value "100nF")
      (footprint "eagle-import:C0603")
      (libsource (lib "eagle-import") (part "C-EUC0603"))
    )
    (comp (ref "C3")
      (value "100nF")
      (footprint "eagle-import:C0603")
      (libsource (lib "eagle-import") (part "C-EUC0603"))
    )
    (comp (ref "C9")
      (value "100nF")
      (footprint "eagle-import:C0603")
      (libsource (lib "eagle-import") (part "C-EUC0603"))
    )
    (comp (ref "C10")
      (value "100nF")
      (footprint "eagle-import:C0603")
      (libsource (lib "eagle-import") (part "C-EUC0603"))
    )
    (comp (ref "IC18")
      (value "MAX3387E")
      (footprint "eagle-import:SSOP24")
      (libsource (lib "eagle-import") (part "MAX3387E"))
    )
    (comp (ref "ST10")
      (value "COM3")
      (footprint "eagle-import:JST-EH5")
      (libsource (lib "eagle-import") (part "JST-EH5"))
    )
    (comp (ref "ST11")
      (value "COM2")
      (footprint "eagle-import:JST-EH5")
      (libsource (lib "eagle-import") (part "JST-EH5"))
    )
    (comp (ref "ST13")
      (value "COM4")
      (footprint "eagle-import:JST-EH5")
      (libsource (lib "eagle-import") (part "JST-EH5"))
    )
    (comp (ref "B1")
      (value "2KBP02M")
      (footprint "eagle-import:2KBP")
      (libsource (lib "eagle-import") (part "2KBP"))
    )
    (comp (ref "C11")
      (value "10uF")
      (footprint "eagle-import:C_6032-28R")
      (libsource (lib "eagle-import") (part "CPOL-EUC/6032-28R"))
    )
    (comp (ref "C19")
      (value "220uF/35V")
      (footprint "eagle-import:150CLZ-0810")
      (libsource (lib "eagle-import") (part "CPOL-EU150CLZ-0810"))
    )
    (comp (ref "C20")
      (value "100nF")
      (footprint "eagle-import:C0603")
      (libsource (lib "eagle-import") (part "C-EUC0603"))
    )
    (comp (ref "C21")
      (value "100nF")
      (footprint "eagle-import:C0603")
      (libsource (lib "eagle-import") (part "C-EUC0603"))
    )
    (comp (ref "C22")
      (value "100uF/16V lowESR")
      (footprint "eagle-import:D_7343-31R")
      (libsource (lib "eagle-import") (part "CPOL-EUD/7343-31R"))
    )
    (comp (ref "C25")
      (value "100uF/16V lowESR")
      (footprint "eagle-import:D_7343-31R")
      (libsource (lib "eagle-import") (part "CPOL-EUD/7343-31R"))
    )
    (comp (ref "C31")
      (value "4,7µF lowESR 50V")
      (footprint "eagle-import:D_7343-31R")
      (libsource (lib "eagle-import") (part "CPOL-EUD/7343-31R"))
    )
    (comp (ref "C32")
      (value "10nF/100V")
      (footprint "eagle-import:C0603")
      (libsource (lib "eagle-import") (part "C-EUC0603"))
    )
    (comp (ref "C37")
      (value "1000uF/50V")
      (footprint "eagle-import:E5-13")
      (libsource (lib "eagle-import") (part "CPOL-EUE5-13"))
    )
    (comp (ref "C56")
      (value "0,33uF/100V")
      (footprint "eagle-import:C1206")
      (libsource (lib "eagle-import") (part "C-EUC1206"))
    )
    (comp (ref "C57")
      (value "100nF")
      (footprint "eagle-import:C0603")
      (libsource (lib "eagle-import") (part "C-EUC0603"))
    )
    (comp (ref "D2")
      (value "MBRD650CT")
      (footprint "eagle-import:DPACK_3")
      (libsource (lib "eagle-import") (part "MBRD650CT"))
    )
    (comp (ref "F1")
      (value "2A")
      (footprint "eagle-import:RXEF025-2")
      (libsource (lib "eagle-import") (part "RXEF0252"))
    )
    (comp (ref "IC5")
      (value "MC33269DT3.3")
      (footprint "eagle-import:D-PAK")
      (libsource (lib "eagle-import") (part "MC33269DT3.3"))
    )
    (comp (ref "IC6")
      (value "7824DT")
      (footprint "eagle-import:TO252")
      (libsource (lib "eagle-import") (part "78DT24"))
    )
    (comp (ref "IC8")
      (value "LM2267TJ-ADJ")
      (footprint "eagle-import:TO263-7")
      (libsource (lib "eagle-import") (part "LM22678"))
    )
    (comp (ref "JP5")
      (value "AC/DC")
      (footprint "eagle-import:1X02")
      (libsource (lib "eagle-import") (part "PINHD-1X2"))
    )
    (comp (ref "JP6")
      (value "AC/DC")
      (footprint "eagle-import:1X02")
      (libsource (lib "eagle-import") (part "PINHD-1X2"))
    )
    (comp (ref "L1")
      (value "15µH 5A")
      (footprint "eagle-import:WE-PD_L_XL_XXL")
      (libsource (lib "eagle-import") (part "WE-PD_L/XL/XXL"))
    )
    (comp (ref "L2")
      (value "RN112-02/02")
      (footprint "eagle-import:RN112")
      (libsource (lib "eagle-import") (part "RN112-2/02"))
    )
    (comp (ref "LCL1")
      (value "6A,10N")
      (footprint "eagle-import:T-FILTERSIL")
      (libsource (lib "eagle-import") (part "DSS6NZ82A103"))
    )
    (comp (ref "LCL2")
      (value "6A,10N")
      (footprint "eagle-import:T-FILTERSIL")
      (libsource (lib "eagle-import") (part "DSS6NZ82A103"))
    )
    (comp (ref "LED3")
      (value "LED_+3V3")
      (footprint "eagle-import:CHIPLED_0603")
      (libsource (lib "eagle-import") (part "LEDCHIPLED_0603"))
    )
    (comp (ref "LED4")
      (value "LED +5V")
      (footprint "eagle-import:CHIPLED_0603")
      (libsource (lib "eagle-import") (part "LEDCHIPLED_0603"))
    )
    (comp (ref "LED5")
      (value "LED +24V")
      (footprint "eagle-import:CHIPLED_0603")
      (libsource (lib "eagle-import") (part "LEDCHIPLED_0603"))
    )
    (comp (ref "R13")
      (value "470R")
      (footprint "eagle-import:R0603")
      (libsource (lib "eagle-import") (part "R-EU_R0603"))
    )
    (comp (ref "R15")
      (value "220R")
      (footprint "eagle-import:R0603")
      (libsource (lib "eagle-import") (part "R-EU_R0603"))
    )
    (comp (ref "R16")
      (value "470R")
      (footprint "eagle-import:R0603")
      (libsource (lib "eagle-import") (part "R-EU_R0603"))
    )
    (comp (ref "R19")
      (value "0R")
      (footprint "eagle-import:R1206")
      (libsource (lib "eagle-import") (part "R-EU_R1206"))
    )
    (comp (ref "R21")
      (value "0R")
      (footprint "eagle-import:R1206")
      (libsource (lib "eagle-import") (part "R-EU_R1206"))
    )
    (comp (ref "R22")
      (value "0R")
      (footprint "eagle-import:R1206")
      (libsource (lib "eagle-import") (part "R-EU_R1206"))
    )
    (comp (ref "R44")
      (value "2k2")
      (footprint "eagle-import:R0603")
      (libsource (lib "eagle-import") (part "R-EU_R0603"))
    )
    (comp (ref "R45")
      (value "10k")
      (footprint "eagle-import:R0603")
      (libsource (lib "eagle-import") (part "R-EU_R0603"))
    )
    (comp (ref "R46")
      (value "820")
      (footprint "eagle-import:R0603")
      (libsource (lib "eagle-import") (part "R-EU_R0603"))
    )
    (comp (ref "R53")
      (value "S10K30")
      (footprint "eagle-import:S10K17")
      (libsource (lib "eagle-import") (part "S10K17"))
    )
    (comp (ref "ST1")
      (value "Power")
      (footprint "eagle-import:180G-2")
      (libsource (lib "eagle-import") (part "180G-2"))
    )
    (comp (ref "ST16")
      (value "Lüfter")
      (footprint "eagle-import:JST-EH2")
      (libsource (lib "eagle-import") (part "JST-EH2"))
    )
    (comp (ref "BZ1")
      (value "CMI-9655S-SMT")
      (footprint "eagle-import:KTG0905CL")
      (libsource (lib "eagle-import") (part "KTG0905CL"))
    )
    (comp (ref "C4")
      (value "100nF")
      (footprint "eagle-import:C0603")
      (libsource (lib "eagle-import") (part "C-EUC0603"))
    )
    (comp (ref "C7")
      (value "12,5pF")
      (footprint "eagle-import:C0603")
      (libsource (lib "eagle-import") (part "C-EUC0603"))
    )
    (comp (ref "C8")
      (value "12,5pF")
      (footprint "eagle-import:C0603")
      (libsource (lib "eagle-import") (part "C-EUC0603"))
    )
    (comp (ref "C12")
      (value "100nF")
      (footprint "eagle-import:C0603")
      (libsource (lib "eagle-import") (part "C-EUC0603"))
    )
    (comp (ref "C13")
      (value "100nF")
      (footprint "eagle-import:C0603")
      (libsource (lib "eagle-import") (part "C-EUC0603"))
    )
    (comp (ref "C14")
      (value "100nF")
      (footprint "eagle-import:C0603")
      (libsource (lib "eagle-import") (part "C-EUC0603"))
    )
    (comp (ref "C15")
      (value "18pF")
      (footprint "eagle-import:C0603")
      (libsource (lib "eagle-import") (part "C-EUC0603"))
    )
    (comp (ref "C16")
      (value "18pF")
      (footprint "eagle-import:C0603")
      (libsource (lib "eagle-import") (part "C-EUC0603"))
    )
    (comp (ref "C17")
      (value "100nF")
      (footprint "eagle-import:C0603")
      (libsource (lib "eagle-import") (part "C-EUC0603"))
    )
    (comp (ref "C18")
      (value "100nF")
      (footprint "eagle-import:C0603")
      (libsource (lib "eagle-import") (part "C-EUC0603"))
    )
    (comp (ref "C29")
      (value "100nF")
      (footprint "eagle-import:C0603")
      (libsource (lib "eagle-import") (part "C-EUC0603"))
    )
    (comp (ref "C30")
      (value "100nF")
      (footprint "eagle-import:C0603")
      (libsource (lib "eagle-import") (part "C-EUC0603"))
    )
    (comp (ref "C50")
      (value "2,2uF")
      (footprint "eagle-import:CT3216")
      (libsource (lib "eagle-import") (part "CPOL-EUCT3216"))
    )
    (comp (ref "C51")
      (value "2,2uF")
      (footprint "eagle-import:CT3216")
      (libsource (lib "eagle-import") (part "CPOL-EUCT3216"))
    )
    (comp (ref "D16")
      (value "BAT54C")
      (footprint "eagle-import:SOT23")
      (libsource (lib "eagle-import") (part "BAT54C"))
    )
    (comp (ref "FID1")
      (value "FIDUCIAL1X2")
      (footprint "eagle-import:FIDUCIAL-1X2")
      (libsource (lib "eagle-import") (part "FIDUCIAL1X2"))
    )
    (comp (ref "FID2")
      (value "FIDUCIAL1X2")
      (footprint "eagle-import:FIDUCIAL-1X2")
      (libsource (lib "eagle-import") (part "FIDUCIAL1X2"))
    )
    (comp (ref "IC1")
      (value "STM32F107")
      (footprint "eagle-import:LQFP100")
      (libsource (lib "eagle-import") (part "G80_SOC"))
    )
    (comp (ref "JP1")
      (value "Reset")
      (footprint "eagle-import:1X02")
      (libsource (lib "eagle-import") (part "PINHD-1X2"))
    )
    (comp (ref "JP7")
      (value "Boot0")
      (footprint "eagle-import:1X02")
      (libsource (lib "eagle-import") (part "PINHD-1X2"))
    )
    (comp (ref "JP8")
      (value "LDR0")
      (footprint "eagle-import:1X02")
      (libsource (lib "eagle-import") (part "PINHD-1X2"))
    )
    (comp (ref "JP9")
      (value "Boot1")
      (footprint "eagle-import:1X02")
      (libsource (lib "eagle-import") (part "PINHD-1X2"))
    )
    (comp (ref "JP10")
      (value "LDR1")
      (footprint "eagle-import:1X02")
      (libsource (lib "eagle-import") (part "PINHD-1X2"))
    )
    (comp (ref "LOGO1")
      (value "ROHS_LOGO")
      (footprint "eagle-import:ROHS_LOGO_0.18_IN")
      (libsource (lib "eagle-import") (part "ROHS_LOGO"))
    )
    (comp (ref "Q1")
      (value "12MHz")
      (footprint "eagle-import:CTS406")
      (libsource (lib "eagle-import") (part "CRYSTALCTS406"))
    )
    (comp (ref "Q2")
      (value "32.768kHz")
      (footprint "eagle-import:3.2X1.5-2-PAD")
      (libsource (lib "eagle-import") (part "CRYSTALS-NOGND-CFPX-217"))
    )
    (comp (ref "R6")
      (value "100R")
      (footprint "eagle-import:R0603")
      (libsource (lib "eagle-import") (part "R-EU_R0603"))
    )
    (comp (ref "R7")
      (value "100k")
      (footprint "eagle-import:R0603")
      (libsource (lib "eagle-import") (part "R-EU_R0603"))
    )
    (comp (ref "R11")
      (value "10k")
      (footprint "eagle-import:R0603")
      (libsource (lib "eagle-import") (part "R-EU_R0603"))
    )
    (comp (ref "R17")
      (value "10k")
      (footprint "eagle-import:R0603")
      (libsource (lib "eagle-import") (part "R-EU_R0603"))
    )
    (comp (ref "R18")
      (value "10k")
      (footprint "eagle-import:R0603")
      (libsource (lib "eagle-import") (part "R-EU_R0603"))
    )
    (comp (ref "R31")
      (value "10k")
      (footprint "eagle-import:R0603")
      (libsource (lib "eagle-import") (part "R-EU_R0603"))
    )
    (comp (ref "R66")
      (value "10k")
      (footprint "eagle-import:R0603")
      (libsource (lib "eagle-import") (part "R-EU_R0603"))
    )
    (comp (ref "R67")
      (value "10k")
      (footprint "eagle-import:R0603")
      (libsource (lib "eagle-import") (part "R-EU_R0603"))
    )
    (comp (ref "R68")
      (value "10k")
      (footprint "eagle-import:R0603")
      (libsource (lib "eagle-import") (part "R-EU_R0603"))
    )
    (comp (ref "R69")
      (value "10k")
      (footprint "eagle-import:R0603")
      (libsource (lib "eagle-import") (part "R-EU_R0603"))
    )
    (comp (ref "R70")
      (value "10k")
      (footprint "eagle-import:R0603")
      (libsource (lib "eagle-import") (part "R-EU_R0603"))
    )
    (comp (ref "R71")
      (value "10k")
      (footprint "eagle-import:R0603")
      (libsource (lib "eagle-import") (part "R-EU_R0603"))
    )
    (comp (ref "T1")
      (value "BC846")
      (footprint "eagle-import:SOT23")
      (libsource (lib "eagle-import") (part "BC846"))
    )
    (comp (ref "IC7")
      (value "NUD3105")
      (footprint "eagle-import:SOT23")
      (libsource (lib "eagle-import") (part "NUD3105"))
    )
    (comp (ref "IC14")
      (value "NUD3105")
      (footprint "eagle-import:SOT23")
      (libsource (lib "eagle-import") (part "NUD3105"))
    )
    (comp (ref "IC16")
      (value "NUD3105")
      (footprint "eagle-import:SOT23")
      (libsource (lib "eagle-import") (part "NUD3105"))
    )
    (comp (ref "K1")
      (value "G6K-2F")
      (footprint "eagle-import:G6K-2F")
      (fields (field (name "MF") "OMRON COMPONENTS USA") (field (name "MPN") "G6K-2F DC24"))
      (libsource (lib "eagle-import") (part "G6K-2F"))
    )
    (comp (ref "K2")
      (value "G6K-2F")
      (footprint "eagle-import:G6K-2F")
      (fields (field (name "MF") "OMRON COMPONENTS USA") (field (name "MPN") "G6K-2F DC24"))
      (libsource (lib "eagle-import") (part "G6K-2F"))
    )
    (comp (ref "K3")
      (value "G6K-2F")
      (footprint "eagle-import:G6K-2F")
      (fields (field (name "MF") "OMRON COMPONENTS USA") (field (name "MPN") "G6K-2F DC24"))
      (libsource (lib "eagle-import") (part "G6K-2F"))
    )
    (comp (ref "ST2")
      (value "RL1")
      (footprint "eagle-import:180G-3")
      (libsource (lib "eagle-import") (part "180G-3"))
    )
    (comp (ref "ST3")
      (value "RL2")
      (footprint "eagle-import:180G-3")
      (libsource (lib "eagle-import") (part "180G-3"))
    )
    (comp (ref "ST4")
      (value "RL3")
      (footprint "eagle-import:180G-3")
      (libsource (lib "eagle-import") (part "180G-3"))
    )
  )
  (nets
    (net (code "1") (name "+3V3") (class "Default")
      (node (ref "C10") (pin "2") (pinfunction "2_2") (pintype "passive"))
      (node (ref "C11") (pin "+") (pinfunction "+_+") (pintype "passive"))
      (node (ref "C12") (pin "1") (pinfunction "1_1") (pintype "passive"))
      (node (ref "C13") (pin "1") (pinfunction "1_1") (pintype "passive"))
      (node (ref "C14") (pin "1") (pinfunction "1_1") (pintype "passive"))
      (node (ref "C17") (pin "1") (pinfunction "1_1") (pintype "passive"))
      (node (ref "C18") (pin "1") (pinfunction "1_1") (pintype "passive"))
      (node (ref "C21") (pin "1") (pinfunction "1_1") (pintype "passive"))
      (node (ref "C29") (pin "1") (pinfunction "1_1") (pintype "passive"))
      (node (ref "C30") (pin "1") (pinfunction "1_1") (pintype "passive"))
      (node (ref "C35") (pin "1") (pinfunction "1_1") (pintype "passive"))
      (node (ref "C40") (pin "1") (pinfunction "1_1") (pintype "passive"))
      (node (ref "C41") (pin "1") (pinfunction "1_1") (pintype "passive"))
      (node (ref "C42") (pin "1") (pinfunction "1_1") (pintype "passive"))
      (node (ref "C43") (pin "1") (pinfunction "1_1") (pintype "passive"))
      (node (ref "C9") (pin "1") (pinfunction "1_1") (pintype "passive"))
      (node (ref "D16") (pin "2") (pinfunction "A2_2") (pintype "passive"))
      (node (ref "FB1") (pin "2") (pinfunction "2_2") (pintype "passive"))
      (node (ref "FB4") (pin "2") (pinfunction "2_2") (pintype "passive"))
      (node (ref "FB5") (pin "2") (pinfunction "2_2") (pintype "passive"))
      (node (ref "FB6") (pin "1") (pinfunction "1_1") (pintype "passive"))
      (node (ref "FB7") (pin "1") (pinfunction "1_1") (pintype "passive"))
      (node (ref "IC1") (pin "100") (pinfunction "VDD_6_100") (pintype "power_in"))
      (node (ref "IC1") (pin "11") (pinfunction "VDD_1_11") (pintype "power_in"))
      (node (ref "IC1") (pin "19") (pinfunction "VDD_2_19") (pintype "power_in"))
      (node (ref "IC1") (pin "21") (pinfunction "VREF+_21") (pintype "bidirectional"))
      (node (ref "IC1") (pin "22") (pinfunction "VDDA_22") (pintype "bidirectional"))
      (node (ref "IC1") (pin "28") (pinfunction "VDD_3_28") (pintype "power_in"))
      (node (ref "IC1") (pin "50") (pinfunction "VDD_4_50") (pintype "power_in"))
      (node (ref "IC1") (pin "75") (pinfunction "VDD_5_75") (pintype "power_in"))
      (node (ref "IC10") (pin "14") (pinfunction "VCC_14") (pintype "power_in"))
      (node (ref "IC12") (pin "14") (pinfunction "VCC_14") (pintype "power_in"))
      (node (ref "IC13") (pin "14") (pinfunction "VCC_14") (pintype "power_in"))
      (node (ref "IC18") (pin "15") (pinfunction "VL_15") (pintype "power_in"))
      (node (ref "IC18") (pin "23") (pinfunction "VCC_23") (pintype "power_in"))
      (node (ref "IC18") (pin "24") (pinfunction "~{FORCEOFF}_24") (pintype "bidirectional"))
      (node (ref "IC5") (pin "2") (pinfunction "OUT_2") (pintype "bidirectional"))
      (node (ref "JP7") (pin "1") (pinfunction "1_1") (pintype "passive"))
      (node (ref "JP9") (pin "1") (pinfunction "1_1") (pintype "passive"))
      (node (ref "OK1") (pin "8") (pinfunction "VCC_8") (pintype "passive"))
      (node (ref "OK2") (pin "2") (pinfunction "A_2") (pintype "passive"))
      (node (ref "OK3") (pin "2") (pinfunction "A_2") (pintype "passive"))
      (node (ref "R1") (pin "1") (pinfunction "1_1") (pintype "passive"))
      (node (ref "R12") (pin "2") (pinfunction "2_2") (pintype "passive"))
      (node (ref "R15") (pin "2") (pinfunction "2_2") (pintype "passive"))
      (node (ref "R2") (pin "1") (pinfunction "1_1") (pintype "passive"))
      (node (ref "R3") (pin "1") (pinfunction "1_1") (pintype "passive"))
      (node (ref "R41") (pin "2") (pinfunction "2_2") (pintype "passive"))
      (node (ref "R42") (pin "2") (pinfunction "2_2") (pintype "passive"))
      (node (ref "R66") (pin "1") (pinfunction "1_1") (pintype "passive"))
      (node (ref "R67") (pin "1") (pinfunction "1_1") (pintype "passive"))
      (node (ref "R68") (pin "1") (pinfunction "1_1") (pintype "passive"))
      (node (ref "R69") (pin "1") (pinfunction "1_1") (pintype "passive"))
      (node (ref "R7") (pin "2") (pinfunction "2_2") (pintype "passive"))
      (node (ref "R70") (pin "1") (pinfunction "1_1") (pintype "passive"))
      (node (ref "R71") (pin "1") (pinfunction "1_1") (pintype "passive"))
      (node (ref "R8") (pin "2") (pinfunction "2_2") (pintype "passive"))
      (node (ref "ST10") (pin "1") (pinfunction "1_1") (pintype "bidirectional"))
      (node (ref "ST11") (pin "1") (pinfunction "1_1") (pintype "bidirectional"))
      (node (ref "ST12") (pin "1") (pinfunction "1_1") (pintype "passive"))
      (node (ref "ST13") (pin "1") (pinfunction "1_1") (pintype "bidirectional"))
      (node (ref "ST14") (pin "1") (pinfunction "1_1") (pintype "passive"))
    )
    (net (code "2") (name "+5V") (class "Default")
      (node (ref "BZ1") (pin "P$1") (pinfunction "1_P$1") (pintype "passive"))
      (node (ref "C19") (pin "+") (pinfunction "+_+") (pintype "passive"))
      (node (ref "C20") (pin "1") (pinfunction "1_1") (pintype "passive"))
      (node (ref "C22") (pin "+") (pinfunction "+_+") (pintype "passive"))
      (node (ref "C33") (pin "+") (pinfunction "+_+") (pintype "passive"))
      (node (ref "DC1") (pin "2") (pinfunction "+VIN_2") (pintype "passive"))
      (node (ref "FB2") (pin "2") (pinfunction "2_2") (pintype "passive"))
      (node (ref "IC15") (pin "8") (pinfunction "VCC_8") (pintype "power_in"))
      (node (ref "IC5") (pin "3") (pinfunction "IN_3") (pintype "bidirectional"))
      (node (ref "JP11") (pin "1") (pinfunction "1_1") (pintype "passive"))
      (node (ref "K1") (pin "1") (pinfunction "+_1") (pintype "passive"))
      (node (ref "K2") (pin "1") (pinfunction "+_1") (pintype "passive"))
      (node (ref "K3") (pin "1") (pinfunction "+_1") (pintype "passive"))
      (node (ref "LCL1") (pin "3") (pinfunction "2_3") (pintype "passive"))
      (node (ref "R16") (pin "2") (pinfunction "2_2") (pintype "passive"))
      (node (ref "R17") (pin "1") (pinfunction "1_1") (pintype "passive"))
      (node (ref "R20") (pin "1") (pinfunction "1_1") (pintype "passive"))
      (node (ref "R30") (pin "1") (pinfunction "1_1") (pintype "passive"))
      (node (ref "R5") (pin "1") (pinfunction "1_1") (pintype "passive"))
      (node (ref "R57") (pin "2") (pinfunction "2_2") (pintype "passive"))
      (node (ref "R59") (pin "2") (pinfunction "2_2") (pintype "passive"))
      (node (ref "R61") (pin "2") (pinfunction "2_2") (pintype "passive"))
      (node (ref "R65") (pin "1") (pinfunction "1_1") (pintype "passive"))
      (node (ref "ST10") (pin "2") (pinfunction "2_2") (pintype "bidirectional"))
      (node (ref "ST11") (pin "2") (pinfunction "2_2") (pintype "bidirectional"))
      (node (ref "ST12") (pin "2") (pinfunction "2_2") (pintype "passive"))
      (node (ref "ST13") (pin "2") (pinfunction "2_2") (pintype "bidirectional"))
      (node (ref "ST14") (pin "2") (pinfunction "2_2") (pintype "passive"))
    )
    (net (code "3") (name "+24V") (class "Default")
      (node (ref "C57") (pin "1") (pinfunction "1_1") (pintype "passive"))
      (node (ref "IC6") (pin "2") (pinfunction "VO_2") (pintype "passive"))
      (node (ref "R13") (pin "2") (pinfunction "2_2") (pintype "passive"))
      (node (ref "R63") (pin "2") (pinfunction "2_2") (pintype "passive"))
      (node (ref "ST16") (pin "1") (pinfunction "1_1") (pintype "bidirectional"))
    )
    (net (code "4") (name "0V") (class "Default")
      (node (ref "B1") (pin "-") (pinfunction "-_-") (pintype "passive"))
      (node (ref "C25") (pin "-") (pinfunction "-_-") (pintype "passive"))
      (node (ref "C31") (pin "-") (pinfunction "-_-") (pintype "passive"))
      (node (ref "C37") (pin "-") (pinfunction "-_-") (pintype "passive"))
      (node (ref "C56") (pin "2") (pinfunction "2_2") (pintype "passive"))
      (node (ref "C57") (pin "2") (pinfunction "2_2") (pintype "passive"))
      (node (ref "D2") (pin "1") (pinfunction "1_1") (pintype "passive"))
      (node (ref "D2") (pin "3") (pinfunction "3_3") (pintype "passive"))
      (node (ref "IC6") (pin "3") (pinfunction "GND_3") (pintype "passive"))
      (node (ref "IC8") (pin "4") (pinfunction "GND_4") (pintype "power_in"))
      (node (ref "IC8") (pin "8") (pinfunction "GND_8") (pintype "power_in"))
      (node (ref "JP6") (pin "1") (pinfunction "1_1") (pintype "passive"))
      (node (ref "LCL1") (pin "2") (pinfunction "GND_2") (pintype "power_in"))
      (node (ref "LCL2") (pin "2") (pinfunction "GND_2") (pintype "power_in"))
      (node (ref "LED5") (pin "C") (pinfunction "C_C") (pintype "passive"))
      (node (ref "R19") (pin "2") (pinfunction "2_2") (pintype "passive"))
      (node (ref "R21") (pin "2") (pinfunction "2_2") (pintype "passive"))
      (node (ref "R22") (pin "2") (pinfunction "2_2") (pintype "passive"))
      (node (ref "R45") (pin "1") (pinfunction "1_1") (pintype "passive"))
      (node (ref "R46") (pin "1") (pinfunction "1_1") (pintype "passive"))
      (node (ref "ST16") (pin "2") (pinfunction "2_2") (pintype "bidirectional"))
    )
    (net (code "5") (name "BOOT0") (class "Default")
      (node (ref "IC1") (pin "94") (pinfunction "BOOT0_94") (pintype "bidirectional"))
      (node (ref "JP7") (pin "2") (pinfunction "2_2") (pintype "passive"))
      (node (ref "R31") (pin "1") (pinfunction "1_1") (pintype "passive"))
    )
    (net (code "6") (name "BOOT1") (class "Default")
      (node (ref "IC1") (pin "37") (pinfunction "PB2_37") (pintype "bidirectional"))
      (node (ref "JP9") (pin "2") (pinfunction "2_2") (pintype "passive"))
      (node (ref "R18") (pin "1") (pinfunction "1_1") (pintype "passive"))
    )
    (net (code "7") (name "GND") (class "Default")
      (node (ref "BAT1") (pin "-") (pinfunction "-_-") (pintype "passive"))
      (node (ref "C1") (pin "2") (pinfunction "2_2") (pintype "passive"))
      (node (ref "C11") (pin "-") (pinfunction "-_-") (pintype "passive"))
      (node (ref "C12") (pin "2") (pinfunction "2_2") (pintype "passive"))
      (node (ref "C13") (pin "2") (pinfunction "2_2") (pintype "passive"))
      (node (ref "C14") (pin "2") (pinfunction "2_2") (pintype "passive"))
      (node (ref "C15") (pin "2") (pinfunction "2_2") (pintype "passive"))
      (node (ref "C16") (pin "2") (pinfunction "2_2") (pintype "passive"))
      (node (ref "C17") (pin "2") (pinfunction "2_2") (pintype "passive"))
      (node (ref "C18") (pin "2") (pinfunction "2_2") (pintype "passive"))
      (node (ref "C19") (pin "-") (pinfunction "-_-") (pintype "passive"))
      (node (ref "C20") (pin "2") (pinfunction "2_2") (pintype "passive"))
      (node (ref "C21") (pin "2") (pinfunction "2_2") (pintype "passive"))
      (node (ref "C22") (pin "-") (pinfunction "-_-") (pintype "passive"))
      (node (ref "C23") (pin "2") (pinfunction "2_2") (pintype "passive"))
      (node (ref "C24") (pin "2") (pinfunction "2_2") (pintype "passive"))
      (node (ref "C26") (pin "2") (pinfunction "2_2") (pintype "passive"))
      (node (ref "C27") (pin "2") (pinfunction "2_2") (pintype "passive"))
      (node (ref "C28") (pin "2") (pinfunction "2_2") (pintype "passive"))
      (node (ref "C29") (pin "2") (pinfunction "2_2") (pintype "passive"))
      (node (ref "C30") (pin "2") (pinfunction "2_2") (pintype "passive"))
      (node (ref "C33") (pin "-") (pinfunction "-_-") (pintype "passive"))
      (node (ref "C35") (pin "2") (pinfunction "2_2") (pintype "passive"))
      (node (ref "C36") (pin "2") (pinfunction "2_2") (pintype "passive"))
      (node (ref "C4") (pin "2") (pinfunction "2_2") (pintype "passive"))
      (node (ref "C40") (pin "2") (pinfunction "2_2") (pintype "passive"))
      (node (ref "C41") (pin "2") (pinfunction "2_2") (pintype "passive"))
      (node (ref "C42") (pin "2") (pinfunction "2_2") (pintype "passive"))
      (node (ref "C43") (pin "2") (pinfunction "2_2") (pintype "passive"))
      (node (ref "C47") (pin "2") (pinfunction "2_2") (pintype "passive"))
      (node (ref "C48") (pin "2") (pinfunction "2_2") (pintype "passive"))
      (node (ref "C49") (pin "2") (pinfunction "2_2") (pintype "passive"))
      (node (ref "C5") (pin "2") (pinfunction "2_2") (pintype "passive"))
      (node (ref "C50") (pin "-") (pinfunction "-_-") (pintype "passive"))
      (node (ref "C51") (pin "-") (pinfunction "-_-") (pintype "passive"))
      (node (ref "C52") (pin "2") (pinfunction "2_2") (pintype "passive"))
      (node (ref "C53") (pin "2") (pinfunction "2_2") (pintype "passive"))
      (node (ref "C54") (pin "2") (pinfunction "2_2") (pintype "passive"))
      (node (ref "C55") (pin "2") (pinfunction "2_2") (pintype "passive"))
      (node (ref "C58") (pin "2") (pinfunction "2_2") (pintype "passive"))
      (node (ref "C59") (pin "2") (pinfunction "2_2") (pintype "passive"))
      (node (ref "C6") (pin "1") (pinfunction "1_1") (pintype "passive"))
      (node (ref "C7") (pin "2") (pinfunction "2_2") (pintype "passive"))
      (node (ref "C8") (pin "2") (pinfunction "2_2") (pintype "passive"))
      (node (ref "C9") (pin "2") (pinfunction "2_2") (pintype "passive"))
      (node (ref "D10") (pin "A") (pinfunction "A_A") (pintype "passive"))
      (node (ref "D11") (pin "A") (pinfunction "A_A") (pintype "passive"))
      (node (ref "D17") (pin "3") (pinfunction "AA_3") (pintype "passive"))
      (node (ref "D9") (pin "A") (pinfunction "A_A") (pintype "passive"))
      (node (ref "DC1") (pin "1") (pinfunction "-VIN_1") (pintype "passive"))
      (node (ref "IC1") (pin "10") (pinfunction "VSS_1_10") (pintype "power_in"))
      (node (ref "IC1") (pin "20") (pinfunction "VSSA_20") (pintype "bidirectional"))
      (node (ref "IC1") (pin "27") (pinfunction "VSS_2_27") (pintype "power_in"))
      (node (ref "IC1") (pin "74") (pinfunction "VSS_3_74") (pintype "power_in"))
      (node (ref "IC1") (pin "99") (pinfunction "VSS_4_99") (pintype "power_in"))
      (node (ref "IC10") (pin "7") (pinfunction "GND_7") (pintype "power_in"))
      (node (ref "IC11") (pin "3") (pinfunction "EMIT_3") (pintype "passive"))
      (node (ref "IC12") (pin "3") (pinfunction "I_3") (pintype "input"))
      (node (ref "IC12") (pin "5") (pinfunction "I_5") (pintype "input"))
      (node (ref "IC12") (pin "7") (pinfunction "GND_7") (pintype "power_in"))
      (node (ref "IC13") (pin "7") (pinfunction "GND_7") (pintype "power_in"))
      (node (ref "IC15") (pin "4") (pinfunction "GND_4") (pintype "power_in"))
      (node (ref "IC17") (pin "2") (pinfunction "GND_2") (pintype "bidirectional"))
      (node (ref "IC18") (pin "11") (pinfunction "FORCEON_11") (pintype "bidirectional"))
      (node (ref "IC18") (pin "22") (pinfunction "GND_22") (pintype "power_in"))
      (node (ref "IC2") (pin "2") (pinfunction "GND_2") (pintype "power_in"))
      (node (ref "IC3") (pin "2") (pinfunction "A1_2") (pintype "input"))
      (node (ref "IC3") (pin "3") (pinfunction "A2_3") (pintype "input"))
      (node (ref "IC3") (pin "4") (pinfunction "GND_4") (pintype "power_in"))
      (node (ref "IC3") (pin "7") (pinfunction "WP_7") (pintype "input"))
      (node (ref "IC4") (pin "11") (pinfunction "VSSRX_11") (pintype "power_in"))
      (node (ref "IC4") (pin "18") (pinfunction "VSSTX_18") (pintype "power_in"))
      (node (ref "IC4") (pin "2") (pinfunction "VSS_2") (pintype "power_in"))
      (node (ref "IC4") (pin "21") (pinfunction "VSSPLL_21") (pintype "power_in"))
      (node (ref "IC4") (pin "22") (pinfunction "VSSOSC_22") (pintype "power_in"))
      (node (ref "IC5") (pin "1") (pinfunction "GND_1") (pintype "bidirectional"))
      (node (ref "JP1") (pin "2") (pinfunction "2_2") (pintype "passive"))
      (node (ref "JP10") (pin "2") (pinfunction "2_2") (pintype "passive"))
      (node (ref "JP4") (pin "6") (pinfunction "6_6") (pintype "passive"))
      (node (ref "JP8") (pin "2") (pinfunction "2_2") (pintype "passive"))
      (node (ref "LED3") (pin "C") (pinfunction "C_C") (pintype "passive"))
      (node (ref "LED4") (pin "C") (pinfunction "C_C") (pintype "passive"))
      (node (ref "OK1") (pin "5") (pinfunction "GND_5") (pintype "passive"))
      (node (ref "Q4") (pin "2") (pinfunction "S_2") (pintype "bidirectional"))
      (node (ref "R18") (pin "2") (pinfunction "2_2") (pintype "passive"))
      (node (ref "R19") (pin "1") (pinfunction "1_1") (pintype "passive"))
      (node (ref "R21") (pin "1") (pinfunction "1_1") (pintype "passive"))
      (node (ref "R22") (pin "1") (pinfunction "1_1") (pintype "passive"))
      (node (ref "R23") (pin "1") (pinfunction "1_1") (pintype "passive"))
      (node (ref "R29") (pin "2") (pinfunction "2_2") (pintype "passive"))
      (node (ref "R31") (pin "2") (pinfunction "2_2") (pintype "passive"))
      (node (ref "R32") (pin "1") (pinfunction "1_1") (pintype "passive"))
      (node (ref "R33") (pin "1") (pinfunction "1_1") (pintype "passive"))
      (node (ref "R51") (pin "1") (pinfunction "1_1") (pintype "passive"))
      (node (ref "SD1") (pin "6") (pinfunction "GND_6") (pintype "power_in"))
      (node (ref "SD1") (pin "P1") (pinfunction "SHIELD_P1") (pintype "passive"))
      (node (ref "SD1") (pin "P2") (pinfunction "SHIELD_P2") (pintype "passive"))
      (node (ref "SD1") (pin "P3") (pinfunction "SHIELD_P3") (pintype "passive"))
      (node (ref "SD1") (pin "P4") (pinfunction "SHIELD_P4") (pintype "passive"))
      (node (ref "SD1") (pin "SWB") (pinfunction "B_SWB") (pintype "bidirectional"))
      (node (ref "ST10") (pin "5") (pinfunction "5_5") (pintype "bidirectional"))
      (node (ref "ST11") (pin "5") (pinfunction "5_5") (pintype "bidirectional"))
      (node (ref "ST12") (pin "15") (pinfunction "15_15") (pintype "passive"))
      (node (ref "ST13") (pin "5") (pinfunction "5_5") (pintype "bidirectional"))
      (node (ref "ST14") (pin "15") (pinfunction "15_15") (pintype "passive"))
      (node (ref "ST14") (pin "16") (pinfunction "16_16") (pintype "passive"))
      (node (ref "ST15") (pin "5") (pinfunction "5_5") (pintype "input"))
      (node (ref "ST15") (pin "M1") (pinfunction "S1_M1") (pintype "passive"))
      (node (ref "ST15") (pin "M2") (pinfunction "S2_M2") (pintype "passive"))
      (node (ref "ST15") (pin "M3") (pinfunction "S3_M3") (pintype "passive"))
      (node (ref "ST15") (pin "M4") (pinfunction "S4_M4") (pintype "passive"))
      (node (ref "ST5") (pin "1") (pinfunction "1_1") (pintype "passive"))
      (node (ref "ST7") (pin "4") (pinfunction "NC/4_4") (pintype "input"))
      (node (ref "ST7") (pin "5") (pinfunction "NC/5_5") (pintype "input"))
      (node (ref "ST8") (pin "2") (pinfunction "S_2") (pintype "passive"))
      (node (ref "ST8") (pin "9") (pinfunction "S_9") (pintype "passive"))
      (node (ref "ST9") (pin "5") (pinfunction "GND_5") (pintype "power_in"))
      (node (ref "ST9") (pin "M1") (pinfunction "SH1_M1") (pintype "bidirectional"))
      (node (ref "ST9") (pin "M2") (pinfunction "SH2_M2") (pintype "bidirectional"))
      (node (ref "ST9") (pin "M3") (pinfunction "SH3_M3") (pintype "bidirectional"))
      (node (ref "ST9") (pin "M6") (pinfunction "SH4_M6") (pintype "bidirectional"))
      (node (ref "T1") (pin "2") (pinfunction "E_2") (pintype "passive"))
      (node (ref "T2") (pin "E") (pinfunction "E_E") (pintype "passive"))
    )
    (net (code "8") (name "GNDIO") (class "Default")
      (node (ref "C34") (pin "2") (pinfunction "2_2") (pintype "passive"))
      (node (ref "C38") (pin "-") (pinfunction "-_-") (pintype "passive"))
      (node (ref "C39") (pin "2") (pinfunction "2_2") (pintype "passive"))
      (node (ref "C45") (pin "-") (pinfunction "-_-") (pintype "passive"))
      (node (ref "C46") (pin "2") (pinfunction "2_2") (pintype "passive"))
      (node (ref "D3") (pin "A") (pinfunction "A_A") (pintype "passive"))
      (node (ref "D4") (pin "2") (pinfunction "A_2") (pintype "passive"))
      (node (ref "D5") (pin "2") (pinfunction "A_2") (pintype "passive"))
      (node (ref "D6") (pin "2") (pinfunction "A_2") (pintype "passive"))
      (node (ref "D8") (pin "2") (pinfunction "A_2") (pintype "passive"))
      (node (ref "DC1") (pin "3") (pinfunction "-VOUT_3") (pintype "passive"))
      (node (ref "IC9") (pin "2") (pinfunction "/RE_2") (pintype "bidirectional"))
      (node (ref "IC9") (pin "5") (pinfunction "GND_5") (pintype "power_in"))
      (node (ref "OK2") (pin "5") (pinfunction "GND_5") (pintype "passive"))
      (node (ref "OK3") (pin "5") (pinfunction "GND_5") (pintype "passive"))
      (node (ref "R52") (pin "1") (pinfunction "1_1") (pintype "passive"))
    )
    (net (code "9") (name "Net-(B1-Pad+)") (class "Default")
      (node (ref "B1") (pin "+") (pinfunction "+_+") (pintype "passive"))
      (node (ref "C37") (pin "+") (pinfunction "+_+") (pintype "passive"))
      (node (ref "JP5") (pin "2") (pinfunction "2_2") (pintype "passive"))
      (node (ref "LCL2") (pin "1") (pinfunction "1_1") (pintype "passive"))
    )
    (net (code "10") (name "Net-(B1-PadAC1)") (class "Default")
      (node (ref "B1") (pin "AC1") (pinfunction "AC1_AC1") (pintype "passive"))
      (node (ref "JP5") (pin "1") (pinfunction "1_1") (pintype "passive"))
      (node (ref "L2") (pin "2") (pinfunction "2_2") (pintype "passive"))
    )
    (net (code "11") (name "Net-(B1-PadAC2)") (class "Default")
      (node (ref "B1") (pin "AC2") (pinfunction "AC2_AC2") (pintype "passive"))
      (node (ref "JP6") (pin "2") (pinfunction "2_2") (pintype "passive"))
      (node (ref "L2") (pin "4") (pinfunction "4_4") (pintype "passive"))
    )
    (net (code "12") (name "Net-(BZ1-2)") (class "Default")
      (node (ref "BZ1") (pin "P$2") (pinfunction "2_P$2") (pintype "passive"))
      (node (ref "R17") (pin "2") (pinfunction "2_2") (pintype "passive"))
      (node (ref "T1") (pin "3") (pinfunction "C_3") (pintype "passive"))
    )
    (net (code "13") (name "Net-(C4-Pad1)") (class "Default")
      (node (ref "C4") (pin "1") (pinfunction "1_1") (pintype "passive"))
      (node (ref "JP1") (pin "1") (pinfunction "1_1") (pintype "passive"))
      (node (ref "R6") (pin "1") (pinfunction "1_1") (pintype "passive"))
      (node (ref "R7") (pin "1") (pinfunction "1_1") (pintype "passive"))
    )
    (net (code "14") (name "Net-(C23-Pad1)") (class "Default")
      (node (ref "C23") (pin "1") (pinfunction "1_1") (pintype "passive"))
      (node (ref "R24") (pin "1") (pinfunction "1_1") (pintype "passive"))
      (node (ref "R25") (pin "2") (pinfunction "2_2") (pintype "passive"))
    )
    (net (code "15") (name "Net-(C44-Pad1)") (class "Default")
      (node (ref "C44") (pin "1") (pinfunction "1_1") (pintype "passive"))
      (node (ref "JP2") (pin "1") (pinfunction "1_1") (pintype "passive"))
    )
    (net (code "16") (name "Net-(C44-Pad2)") (class "Default")
      (node (ref "C44") (pin "2") (pinfunction "2_2") (pintype "passive"))
      (node (ref "R56") (pin "2") (pinfunction "2_2") (pintype "passive"))
    )
    (net (code "17") (name "Net-(D1-A)") (class "Default")
      (node (ref "D1") (pin "1") (pinfunction "A_1") (pintype "passive"))
      (node (ref "R14") (pin "2") (pinfunction "2_2") (pintype "passive"))
    )
    (net (code "18") (name "Net-(D7-AC)") (class "Default")
      (node (ref "D7") (pin "3") (pinfunction "AC_3") (pintype "passive"))
      (node (ref "R55") (pin "2") (pinfunction "2_2") (pintype "passive"))
    )
    (net (code "19") (name "Net-(D9-PadC)") (class "Default")
      (node (ref "D9") (pin "C") (pinfunction "C_C") (pintype "passive"))
      (node (ref "R57") (pin "1") (pinfunction "1_1") (pintype "passive"))
      (node (ref "R58") (pin "2") (pinfunction "2_2") (pintype "passive"))
      (node (ref "ST5") (pin "2") (pinfunction "2_2") (pintype "passive"))
    )
    (net (code "20") (name "Net-(D10-PadC)") (class "Default")
      (node (ref "D10") (pin "C") (pinfunction "C_C") (pintype "passive"))
      (node (ref "R59") (pin "1") (pinfunction "1_1") (pintype "passive"))
      (node (ref "R60") (pin "2") (pinfunction "2_2") (pintype "passive"))
      (node (ref "ST5") (pin "3") (pinfunction "3_3") (pintype "passive"))
    )
    (net (code "21") (name "Net-(D11-PadC)") (class "Default")
      (node (ref "D11") (pin "C") (pinfunction "C_C") (pintype "passive"))
      (node (ref "R61") (pin "1") (pinfunction "1_1") (pintype "passive"))
      (node (ref "R62") (pin "2") (pinfunction "2_2") (pintype "passive"))
      (node (ref "ST5") (pin "4") (pinfunction "4_4") (pintype "passive"))
    )
    (net (code "22") (name "Net-(D12-PadC)") (class "Default")
      (node (ref "D12") (pin "C") (pinfunction "C_C") (pintype "passive"))
      (node (ref "JP4") (pin "3") (pinfunction "3_3") (pintype "passive"))
      (node (ref "R64") (pin "2") (pinfunction "2_2") (pintype "passive"))
    )
    (net (code "23") (name "Net-(F1-PadIN)") (class "Default")
      (node (ref "F1") (pin "IN") (pinfunction "IN_IN") (pintype "bidirectional"))
      (node (ref "ST1") (pin "1") (pinfunction "1_1") (pintype "passive"))
    )
    (net (code "24") (name "Net-(F1-PadOUT)") (class "Default")
      (node (ref "F1") (pin "OUT") (pinfunction "OUT_OUT") (pintype "bidirectional"))
      (node (ref "L2") (pin "1") (pinfunction "1_1") (pintype "passive"))
      (node (ref "R53") (pin "1") (pinfunction "1_1") (pintype "passive"))
    )
    (net (code "25") (name "Net-(IC1B-OSC-IN)") (class "Default")
      (node (ref "C16") (pin "1") (pinfunction "1_1") (pintype "passive"))
      (node (ref "IC1") (pin "12") (pinfunction "OSC-IN_12") (pintype "bidirectional"))
      (node (ref "Q1") (pin "3") (pinfunction "2_3") (pintype "passive"))
    )
    (net (code "26") (name "Net-(IC1B-OSC-OUT)") (class "Default")
      (node (ref "C15") (pin "1") (pinfunction "1_1") (pintype "passive"))
      (node (ref "IC1") (pin "13") (pinfunction "OSC-OUT_13") (pintype "bidirectional"))
      (node (ref "Q1") (pin "1") (pinfunction "1_1") (pintype "passive"))
    )
    (net (code "27") (name "Net-(IC1G-PC14)") (class "Default")
      (node (ref "C8") (pin "1") (pinfunction "1_1") (pintype "passive"))
      (node (ref "IC1") (pin "8") (pinfunction "PC14_8") (pintype "bidirectional"))
      (node (ref "Q2") (pin "1") (pinfunction "1_1") (pintype "passive"))
    )
    (net (code "28") (name "Net-(IC1G-PC15)") (class "Default")
      (node (ref "C7") (pin "1") (pinfunction "1_1") (pintype "passive"))
      (node (ref "IC1") (pin "9") (pinfunction "PC15_9") (pintype "bidirectional"))
      (node (ref "Q2") (pin "2") (pinfunction "2_2") (pintype "passive"))
    )
    (net (code "29") (name "Net-(IC1O-VCAP_1)") (class "Default")
      (node (ref "C50") (pin "+") (pinfunction "+_+") (pintype "passive"))
      (node (ref "IC1") (pin "49") (pinfunction "VCAP_1_49") (pintype "bidirectional"))
    )
    (net (code "30") (name "Net-(IC1O-VCAP_2)") (class "Default")
      (node (ref "C51") (pin "+") (pinfunction "+_+") (pintype "passive"))
      (node (ref "IC1") (pin "73") (pinfunction "VCAP_2_73") (pintype "bidirectional"))
    )
    (net (code "31") (name "Net-(IC2-IN)") (class "Default")
      (node (ref "FB2") (pin "1") (pinfunction "1_1") (pintype "passive"))
      (node (ref "IC2") (pin "5") (pinfunction "IN_5") (pintype "bidirectional"))
    )
    (net (code "32") (name "Net-(IC2-OUT)") (class "Default")
      (node (ref "FB3") (pin "1") (pinfunction "1_1") (pintype "passive"))
      (node (ref "IC2") (pin "1") (pinfunction "OUT_1") (pintype "bidirectional"))
      (node (ref "R14") (pin "1") (pinfunction "1_1") (pintype "passive"))
      (node (ref "R4") (pin "2") (pinfunction "2_2") (pintype "passive"))
    )
    (net (code "33") (name "Net-(IC2-~{OC})") (class "Default")
      (node (ref "IC2") (pin "3") (pinfunction "~{OC}_3") (pintype "bidirectional"))
      (node (ref "LED1") (pin "C") (pinfunction "C_C") (pintype "passive"))
      (node (ref "R2") (pin "2") (pinfunction "2_2") (pintype "passive"))
    )
    (net (code "34") (name "Net-(IC3-A0)") (class "Default")
      (node (ref "C6") (pin "2") (pinfunction "2_2") (pintype "passive"))
      (node (ref "FB5") (pin "1") (pinfunction "1_1") (pintype "passive"))
      (node (ref "IC3") (pin "1") (pinfunction "A0_1") (pintype "input"))
      (node (ref "IC3") (pin "8") (pinfunction "VCC_8") (pintype "power_in"))
    )
    (net (code "35") (name "Net-(IC4-LEDA)") (class "Default")
      (node (ref "IC4") (pin "27") (pinfunction "LEDA_27") (pintype "output"))
      (node (ref "ST7") (pin "9") (pinfunction "A-R_9") (pintype "passive"))
    )
    (net (code "36") (name "Net-(IC4-LEDB)") (class "Default")
      (node (ref "IC4") (pin "26") (pinfunction "LEDB_26") (pintype "output"))
      (node (ref "ST7") (pin "12") (pinfunction "AL_12") (pintype "passive"))
    )
    (net (code "37") (name "Net-(IC4-OSC1)") (class "Default")
      (node (ref "C53") (pin "1") (pinfunction "1_1") (pintype "passive"))
      (node (ref "IC4") (pin "23") (pinfunction "OSC1_23") (pintype "input"))
      (node (ref "Q3") (pin "3") (pinfunction "2_3") (pintype "passive"))
    )
    (net (code "38") (name "Net-(IC4-OSC2)") (class "Default")
      (node (ref "C52") (pin "1") (pinfunction "1_1") (pintype "passive"))
      (node (ref "IC4") (pin "24") (pinfunction "OSC2_24") (pintype "output"))
      (node (ref "Q3") (pin "1") (pinfunction "1_1") (pintype "passive"))
    )
    (net (code "39") (name "Net-(IC4-RBIAS)") (class "Default")
      (node (ref "IC4") (pin "14") (pinfunction "RBIAS_14") (pintype "input"))
      (node (ref "R23") (pin "2") (pinfunction "2_2") (pintype "passive"))
    )
    (net (code "40") (name "Net-(IC4-VCAP)") (class "Default")
      (node (ref "C27") (pin "1") (pinfunction "1_1") (pintype "passive"))
      (node (ref "IC4") (pin "1") (pinfunction "VCAP_1") (pintype "power_in"))
    )
    (net (code "41") (name "Net-(IC4-VDD)") (class "Default")
      (node (ref "C24") (pin "1") (pinfunction "1_1") (pintype "passive"))
      (node (ref "C54") (pin "1") (pinfunction "1_1") (pintype "passive"))
      (node (ref "C55") (pin "1") (pinfunction "1_1") (pintype "passive"))
      (node (ref "FB7") (pin "2") (pinfunction "2_2") (pintype "passive"))
      (node (ref "IC4") (pin "15") (pinfunction "VDDTX_15") (pintype "power_in"))
      (node (ref "IC4") (pin "19") (pinfunction "VDDRX_19") (pintype "power_in"))
      (node (ref "IC4") (pin "20") (pinfunction "VDDPLL_20") (pintype "power_in"))
      (node (ref "IC4") (pin "25") (pinfunction "VDDOSC_25") (pintype "power_in"))
      (node (ref "IC4") (pin "28") (pinfunction "VDD_28") (pintype "power_in"))
    )
    (net (code "42") (name "Net-(IC7-D)") (class "Default")
      (node (ref "IC7") (pin "3") (pinfunction "D_3") (pintype "bidirectional"))
      (node (ref "K1") (pin "8") (pinfunction "-_8") (pintype "passive"))
    )
    (net (code "43") (name "Net-(IC8-BOOT)") (class "Default")
      (node (ref "C32") (pin "1") (pinfunction "1_1") (pintype "passive"))
      (node (ref "IC8") (pin "3") (pinfunction "BOOT_3") (pintype "bidirectional"))
    )
    (net (code "44") (name "Net-(IC8-FB)") (class "Default")
      (node (ref "IC8") (pin "6") (pinfunction "FB_6") (pintype "bidirectional"))
      (node (ref "R44") (pin "1") (pinfunction "1_1") (pintype "passive"))
      (node (ref "R45") (pin "2") (pinfunction "2_2") (pintype "passive"))
      (node (ref "R46") (pin "2") (pinfunction "2_2") (pintype "passive"))
    )
    (net (code "45") (name "Net-(IC8-SW)") (class "Default")
      (node (ref "C32") (pin "2") (pinfunction "2_2") (pintype "passive"))
      (node (ref "D2") (pin "4") (pinfunction "4_4") (pintype "passive"))
      (node (ref "IC8") (pin "1") (pinfunction "SW_1") (pintype "bidirectional"))
      (node (ref "L1") (pin "2") (pinfunction "1_2") (pintype "passive"))
    )
    (net (code "46") (name "Net-(IC9-D)") (class "Default")
      (node (ref "IC9") (pin "4") (pinfunction "D_4") (pintype "bidirectional"))
      (node (ref "OK2") (pin "6") (pinfunction "VO_6") (pintype "passive"))
      (node (ref "R47") (pin "1") (pinfunction "1_1") (pintype "passive"))
    )
    (net (code "47") (name "Net-(IC9-DE)") (class "Default")
      (node (ref "IC9") (pin "3") (pinfunction "DE_3") (pintype "bidirectional"))
      (node (ref "OK3") (pin "6") (pinfunction "VO_6") (pintype "passive"))
      (node (ref "R48") (pin "1") (pinfunction "1_1") (pintype "passive"))
    )
    (net (code "48") (name "Net-(IC9-R)") (class "Default")
      (node (ref "IC9") (pin "1") (pinfunction "R_1") (pintype "bidirectional"))
      (node (ref "R40") (pin "2") (pinfunction "2_2") (pintype "passive"))
    )
    (net (code "49") (name "Net-(IC10A-O)") (class "Default")
      (node (ref "IC10") (pin "11") (pinfunction "I_11") (pintype "input"))
      (node (ref "IC10") (pin "12") (pinfunction "O_12") (pintype "output"))
    )
    (net (code "50") (name "Net-(IC10B-O)") (class "Default")
      (node (ref "IC10") (pin "10") (pinfunction "O_10") (pintype "output"))
      (node (ref "R50") (pin "1") (pinfunction "1_1") (pintype "passive"))
    )
    (net (code "51") (name "Net-(IC10C-O)") (class "Default")
      (node (ref "IC10") (pin "1") (pinfunction "I_1") (pintype "input"))
      (node (ref "IC10") (pin "8") (pinfunction "O_8") (pintype "output"))
    )
    (net (code "52") (name "Net-(IC10D-O)") (class "Default")
      (node (ref "IC10") (pin "2") (pinfunction "O_2") (pintype "output"))
      (node (ref "R49") (pin "1") (pinfunction "1_1") (pintype "passive"))
    )
    (net (code "53") (name "Net-(IC10E-I)") (class "Default")
      (node (ref "IC10") (pin "3") (pinfunction "I_3") (pintype "input"))
      (node (ref "IC10") (pin "6") (pinfunction "O_6") (pintype "output"))
    )
    (net (code "54") (name "Net-(IC10F-I)") (class "Default")
      (node (ref "IC10") (pin "5") (pinfunction "I_5") (pintype "input"))
      (node (ref "OK1") (pin "6") (pinfunction "VO_6") (pintype "passive"))
      (node (ref "R41") (pin "1") (pinfunction "1_1") (pintype "passive"))
    )
    (net (code "55") (name "Net-(IC11-A)") (class "Default")
      (node (ref "IC11") (pin "1") (pinfunction "A_1") (pintype "passive"))
      (node (ref "R64") (pin "1") (pinfunction "1_1") (pintype "passive"))
    )
    (net (code "56") (name "Net-(IC11-C)") (class "Default")
      (node (ref "D12") (pin "A") (pinfunction "A_A") (pintype "passive"))
      (node (ref "IC11") (pin "2") (pinfunction "C_2") (pintype "passive"))
      (node (ref "JP4") (pin "5") (pinfunction "5_5") (pintype "passive"))
    )
    (net (code "57") (name "Net-(IC11-COL)") (class "Default")
      (node (ref "IC11") (pin "4") (pinfunction "COL_4") (pintype "passive"))
      (node (ref "R42") (pin "1") (pinfunction "1_1") (pintype "passive"))
      (node (ref "R43") (pin "2") (pinfunction "2_2") (pintype "passive"))
    )
    (net (code "58") (name "Net-(IC12A-I)") (class "Default")
      (node (ref "C49") (pin "1") (pinfunction "1_1") (pintype "passive"))
      (node (ref "IC12") (pin "13") (pinfunction "I_13") (pintype "input"))
      (node (ref "R62") (pin "1") (pinfunction "1_1") (pintype "passive"))
    )
    (net (code "59") (name "Net-(IC12B-I)") (class "Default")
      (node (ref "C48") (pin "1") (pinfunction "1_1") (pintype "passive"))
      (node (ref "IC12") (pin "11") (pinfunction "I_11") (pintype "input"))
      (node (ref "R60") (pin "1") (pinfunction "1_1") (pintype "passive"))
    )
    (net (code "60") (name "Net-(IC12C-I)") (class "Default")
      (node (ref "C47") (pin "1") (pinfunction "1_1") (pintype "passive"))
      (node (ref "IC12") (pin "9") (pinfunction "I_9") (pintype "input"))
      (node (ref "R58") (pin "1") (pinfunction "1_1") (pintype "passive"))
    )
    (net (code "61") (name "Net-(IC12D-I)") (class "Default")
      (node (ref "C36") (pin "1") (pinfunction "1_1") (pintype "passive"))
      (node (ref "IC12") (pin "1") (pinfunction "I_1") (pintype "input"))
      (node (ref "R43") (pin "1") (pinfunction "1_1") (pintype "passive"))
    )
    (net (code "62") (name "Net-(IC13A-I)") (class "Default")
      (node (ref "IC13") (pin "13") (pinfunction "I_13") (pintype "input"))
      (node (ref "IC13") (pin "2") (pinfunction "O_2") (pintype "output"))
    )
    (net (code "63") (name "Net-(IC13B-I)") (class "Default")
      (node (ref "IC13") (pin "11") (pinfunction "I_11") (pintype "input"))
      (node (ref "IC13") (pin "4") (pinfunction "O_4") (pintype "output"))
    )
    (net (code "64") (name "Net-(IC13C-I)") (class "Default")
      (node (ref "IC13") (pin "6") (pinfunction "O_6") (pintype "output"))
      (node (ref "IC13") (pin "9") (pinfunction "I_9") (pintype "input"))
    )
    (net (code "65") (name "Net-(IC14-D)") (class "Default")
      (node (ref "IC14") (pin "3") (pinfunction "D_3") (pintype "bidirectional"))
      (node (ref "K2") (pin "8") (pinfunction "-_8") (pintype "passive"))
    )
    (net (code "66") (name "Net-(IC16-D)") (class "Default")
      (node (ref "IC16") (pin "3") (pinfunction "D_3") (pintype "bidirectional"))
      (node (ref "K3") (pin "8") (pinfunction "-_8") (pintype "passive"))
    )
    (net (code "67") (name "Net-(IC17-VBUS)") (class "Default")
      (node (ref "FB3") (pin "2") (pinfunction "2_2") (pintype "passive"))
      (node (ref "IC17") (pin "5") (pinfunction "VBUS_5") (pintype "bidirectional"))
      (node (ref "ST9") (pin "1") (pinfunction "VBUS_1") (pintype "power_in"))
    )
    (net (code "68") (name "Net-(IC18-C1+)") (class "Default")
      (node (ref "C3") (pin "2") (pinfunction "2_2") (pintype "passive"))
      (node (ref "IC18") (pin "1") (pinfunction "C1+_1") (pintype "bidirectional"))
    )
    (net (code "69") (name "Net-(IC18-C1-)") (class "Default")
      (node (ref "C3") (pin "1") (pinfunction "1_1") (pintype "passive"))
      (node (ref "IC18") (pin "3") (pinfunction "C1-_3") (pintype "bidirectional"))
    )
    (net (code "70") (name "Net-(IC18-C2+)") (class "Default")
      (node (ref "C2") (pin "2") (pinfunction "2_2") (pintype "passive"))
      (node (ref "IC18") (pin "4") (pinfunction "C2+_4") (pintype "bidirectional"))
    )
    (net (code "71") (name "Net-(IC18-C2-)") (class "Default")
      (node (ref "C2") (pin "1") (pinfunction "1_1") (pintype "passive"))
      (node (ref "IC18") (pin "5") (pinfunction "C2-_5") (pintype "bidirectional"))
    )
    (net (code "72") (name "Net-(IC18-V+)") (class "Default")
      (node (ref "C10") (pin "1") (pinfunction "1_1") (pintype "passive"))
      (node (ref "IC18") (pin "2") (pinfunction "V+_2") (pintype "bidirectional"))
    )
    (net (code "73") (name "Net-(IC18-V-)") (class "Default")
      (node (ref "C1") (pin "1") (pinfunction "1_1") (pintype "passive"))
      (node (ref "IC18") (pin "6") (pinfunction "V-_6") (pintype "bidirectional"))
    )
    (net (code "74") (name "Net-(JP3-Pad1)") (class "Default")
      (node (ref "JP3") (pin "1") (pinfunction "1_1") (pintype "passive"))
      (node (ref "R54") (pin "2") (pinfunction "2_2") (pintype "passive"))
    )
    (net (code "75") (name "Net-(JP4-Pad1)") (class "Default")
      (node (ref "JP4") (pin "1") (pinfunction "1_1") (pintype "passive"))
      (node (ref "R63") (pin "1") (pinfunction "1_1") (pintype "passive"))
      (node (ref "R65") (pin "2") (pinfunction "2_2") (pintype "passive"))
    )
    (net (code "76") (name "Net-(K1B-O)") (class "Default")
      (node (ref "K1") (pin "2") (pinfunction "O_2") (pintype "passive"))
      (node (ref "K1") (pin "7") (pinfunction "O_7") (pintype "passive"))
      (node (ref "ST2") (pin "3") (pinfunction "3_3") (pintype "passive"))
    )
    (net (code "77") (name "Net-(K1B-P)") (class "Default")
      (node (ref "K1") (pin "3") (pinfunction "P_3") (pintype "passive"))
      (node (ref "K1") (pin "6") (pinfunction "P_6") (pintype "passive"))
      (node (ref "ST2") (pin "2") (pinfunction "2_2") (pintype "passive"))
    )
    (net (code "78") (name "Net-(K1B-S)") (class "Default")
      (node (ref "K1") (pin "4") (pinfunction "S_4") (pintype "passive"))
      (node (ref "K1") (pin "5") (pinfunction "S_5") (pintype "passive"))
      (node (ref "ST2") (pin "1") (pinfunction "1_1") (pintype "passive"))
    )
    (net (code "79") (name "Net-(K2B-O)") (class "Default")
      (node (ref "K2") (pin "2") (pinfunction "O_2") (pintype "passive"))
      (node (ref "K2") (pin "7") (pinfunction "O_7") (pintype "passive"))
      (node (ref "ST3") (pin "3") (pinfunction "3_3") (pintype "passive"))
    )
    (net (code "80") (name "Net-(K2B-P)") (class "Default")
      (node (ref "K2") (pin "3") (pinfunction "P_3") (pintype "passive"))
      (node (ref "K2") (pin "6") (pinfunction "P_6") (pintype "passive"))
      (node (ref "ST3") (pin "2") (pinfunction "2_2") (pintype "passive"))
    )
    (net (code "81") (name "Net-(K2B-S)") (class "Default")
      (node (ref "K2") (pin "4") (pinfunction "S_4") (pintype "passive"))
      (node (ref "K2") (pin "5") (pinfunction "S_5") (pintype "passive"))
      (node (ref "ST3") (pin "1") (pinfunction "1_1") (pintype "passive"))
    )
    (net (code "82") (name "Net-(K3B-O)") (class "Default")
      (node (ref "K3") (pin "2") (pinfunction "O_2") (pintype "passive"))
      (node (ref "K3") (pin "7") (pinfunction "O_7") (pintype "passive"))
      (node (ref "ST4") (pin "3") (pinfunction "3_3") (pintype "passive"))
    )
    (net (code "83") (name "Net-(K3B-P)") (class "Default")
      (node (ref "K3") (pin "3") (pinfunction "P_3") (pintype "passive"))
      (node (ref "K3") (pin "6") (pinfunction "P_6") (pintype "passive"))
      (node (ref "ST4") (pin "2") (pinfunction "2_2") (pintype "passive"))
    )
    (net (code "84") (name "Net-(K3B-S)") (class "Default")
      (node (ref "K3") (pin "4") (pinfunction "S_4") (pintype "passive"))
      (node (ref "K3") (pin "5") (pinfunction "S_5") (pintype "passive"))
      (node (ref "ST4") (pin "1") (pinfunction "1_1") (pintype "passive"))
    )
    (net (code "85") (name "Net-(L1-2)") (class "Default")
      (node (ref "C25") (pin "+") (pinfunction "+_+") (pintype "passive"))
      (node (ref "L1") (pin "1") (pinfunction "2_1") (pintype "passive"))
      (node (ref "LCL1") (pin "1") (pinfunction "1_1") (pintype "passive"))
      (node (ref "R44") (pin "2") (pinfunction "2_2") (pintype "passive"))
    )
    (net (code "86") (name "Net-(L2-Pad3)") (class "Default")
      (node (ref "L2") (pin "3") (pinfunction "3_3") (pintype "passive"))
      (node (ref "R53") (pin "2") (pinfunction "2_2") (pintype "passive"))
      (node (ref "ST1") (pin "2") (pinfunction "2_2") (pintype "passive"))
    )
    (net (code "87") (name "Net-(LED1-PadA)") (class "Default")
      (node (ref "LED1") (pin "A") (pinfunction "A_A") (pintype "passive"))
      (node (ref "R3") (pin "2") (pinfunction "2_2") (pintype "passive"))
    )
    (net (code "88") (name "Net-(LED2-PadA)") (class "Default")
      (node (ref "LED2") (pin "A") (pinfunction "A_A") (pintype "passive"))
      (node (ref "R5") (pin "2") (pinfunction "2_2") (pintype "passive"))
    )
    (net (code "89") (name "Net-(LED2-PadC)") (class "Default")
      (node (ref "LED2") (pin "C") (pinfunction "C_C") (pintype "passive"))
      (node (ref "T2") (pin "C") (pinfunction "C_C") (pintype "passive"))
    )
    (net (code "90") (name "Net-(LED3-PadA)") (class "Default")
      (node (ref "LED3") (pin "A") (pinfunction "A_A") (pintype "passive"))
      (node (ref "R15") (pin "1") (pinfunction "1_1") (pintype "passive"))
    )
    (net (code "91") (name "Net-(LED4-PadA)") (class "Default")
      (node (ref "LED4") (pin "A") (pinfunction "A_A") (pintype "passive"))
      (node (ref "R16") (pin "1") (pinfunction "1_1") (pintype "passive"))
    )
    (net (code "92") (name "Net-(LED5-PadA)") (class "Default")
      (node (ref "LED5") (pin "A") (pinfunction "A_A") (pintype "passive"))
      (node (ref "R13") (pin "1") (pinfunction "1_1") (pintype "passive"))
    )
    (net (code "93") (name "Net-(OK1-C)") (class "Default")
      (node (ref "OK1") (pin "3") (pinfunction "C_3") (pintype "passive"))
      (node (ref "R40") (pin "1") (pinfunction "1_1") (pintype "passive"))
    )
    (net (code "94") (name "Net-(OK2-C)") (class "Default")
      (node (ref "OK2") (pin "3") (pinfunction "C_3") (pintype "passive"))
      (node (ref "R49") (pin "2") (pinfunction "2_2") (pintype "passive"))
    )
    (net (code "95") (name "Net-(OK3-C)") (class "Default")
      (node (ref "OK3") (pin "3") (pinfunction "C_3") (pintype "passive"))
      (node (ref "R50") (pin "2") (pinfunction "2_2") (pintype "passive"))
    )
    (net (code "96") (name "Net-(Q4-D)") (class "Default")
      (node (ref "Q4") (pin "3") (pinfunction "D_3") (pintype "bidirectional"))
      (node (ref "ST8") (pin "19") (pinfunction "S_19") (pintype "passive"))
      (node (ref "ST8") (pin "20") (pinfunction "S_20") (pintype "passive"))
    )
    (net (code "97") (name "Net-(Q4-G)") (class "Default")
      (node (ref "Q4") (pin "1") (pinfunction "G_1") (pintype "bidirectional"))
      (node (ref "R36") (pin "2") (pinfunction "2_2") (pintype "passive"))
    )
    (net (code "98") (name "Net-(R4-Pad1)") (class "Default")
      (node (ref "R4") (pin "1") (pinfunction "1_1") (pintype "passive"))
      (node (ref "T2") (pin "B") (pinfunction "B_B") (pintype "passive"))
    )
    (net (code "99") (name "Net-(R28-Pad2)") (class "Default")
      (node (ref "R28") (pin "2") (pinfunction "2_2") (pintype "passive"))
      (node (ref "ST15") (pin "1") (pinfunction "1_1") (pintype "input"))
    )
    (net (code "100") (name "Net-(R34-Pad1)") (class "Default")
      (node (ref "R34") (pin "1") (pinfunction "1_1") (pintype "passive"))
      (node (ref "ST15") (pin "2") (pinfunction "2_2") (pintype "input"))
    )
    (net (code "101") (name "Net-(R35-Pad1)") (class "Default")
      (node (ref "R35") (pin "1") (pinfunction "1_1") (pintype "passive"))
      (node (ref "ST15") (pin "3") (pinfunction "3_3") (pintype "input"))
    )
    (net (code "102") (name "Net-(SD1-A)") (class "Default")
      (node (ref "R9") (pin "1") (pinfunction "1_1") (pintype "passive"))
      (node (ref "SD1") (pin "SWA") (pinfunction "A_SWA") (pintype "bidirectional"))
    )
    (net (code "103") (name "Net-(SD1-VCC)") (class "Default")
      (node (ref "C5") (pin "1") (pinfunction "1_1") (pintype "passive"))
      (node (ref "FB4") (pin "1") (pinfunction "1_1") (pintype "passive"))
      (node (ref "R10") (pin "1") (pinfunction "1_1") (pintype "passive"))
      (node (ref "SD1") (pin "4") (pinfunction "VCC_4") (pintype "power_in"))
    )
    (net (code "104") (name "Net-(ST7-C-L)") (class "Default")
      (node (ref "R32") (pin "2") (pinfunction "2_2") (pintype "passive"))
      (node (ref "ST7") (pin "11") (pinfunction "C-L_11") (pintype "passive"))
    )
    (net (code "105") (name "Net-(ST7-C-R)") (class "Default")
      (node (ref "R33") (pin "2") (pinfunction "2_2") (pintype "passive"))
      (node (ref "ST7") (pin "10") (pinfunction "C-R_10") (pintype "passive"))
    )
    (net (code "106") (name "Net-(ST7-CT)") (class "Default")
      (node (ref "C26") (pin "1") (pinfunction "1_1") (pintype "passive"))
      (node (ref "FB6") (pin "2") (pinfunction "2_2") (pintype "passive"))
      (node (ref "R26") (pin "2") (pinfunction "2_2") (pintype "passive"))
      (node (ref "R27") (pin "1") (pinfunction "1_1") (pintype "passive"))
      (node (ref "ST7") (pin "3") (pinfunction "CT_3") (pintype "input"))
    )
    (net (code "107") (name "Net-(ST8A-S)") (class "Default")
      (node (ref "C28") (pin "1") (pinfunction "1_1") (pintype "passive"))
      (node (ref "FB1") (pin "1") (pinfunction "1_1") (pintype "passive"))
      (node (ref "ST8") (pin "1") (pinfunction "S_1") (pintype "passive"))
    )
    (net (code "108") (name "Net-(ST8I-S)") (class "Default")
      (node (ref "JP11") (pin "2") (pinfunction "2_2") (pintype "passive"))
      (node (ref "ST8") (pin "17") (pinfunction "S_17") (pintype "passive"))
      (node (ref "ST8") (pin "18") (pinfunction "S_18") (pintype "passive"))
    )
    (net (code "109") (name "Net-(ST9-D+)") (class "Default")
      (node (ref "IC17") (pin "6") (pinfunction "I/O1_6") (pintype "bidirectional"))
      (node (ref "ST9") (pin "3") (pinfunction "D+_3") (pintype "bidirectional"))
    )
    (net (code "110") (name "Net-(ST9-D-)") (class "Default")
      (node (ref "IC17") (pin "4") (pinfunction "I/O2_4") (pintype "bidirectional"))
      (node (ref "ST9") (pin "2") (pinfunction "D-_2") (pintype "bidirectional"))
    )
    (net (code "111") (name "Net-(T1-B)") (class "Default")
      (node (ref "R11") (pin "2") (pinfunction "2_2") (pintype "passive"))
      (node (ref "T1") (pin "1") (pinfunction "B_1") (pintype "passive"))
    )
    (net (code "112") (name "OPTO") (class "Default")
      (node (ref "JP4") (pin "2") (pinfunction "2_2") (pintype "passive"))
      (node (ref "ST5") (pin "6") (pinfunction "6_6") (pintype "passive"))
    )
    (net (code "113") (name "OPTO_GND") (class "Default")
      (node (ref "JP4") (pin "4") (pinfunction "4_4") (pintype "passive"))
      (node (ref "ST5") (pin "5") (pinfunction "5_5") (pintype "passive"))
    )
    (net (code "114") (name "OUT4") (class "Default")
      (node (ref "IC13") (pin "12") (pinfunction "O_12") (pintype "output"))
      (node (ref "ST14") (pin "3") (pinfunction "3_3") (pintype "passive"))
    )
    (net (code "115") (name "OUT5") (class "Default")
      (node (ref "IC13") (pin "10") (pinfunction "O_10") (pintype "output"))
      (node (ref "ST14") (pin "5") (pinfunction "5_5") (pintype "passive"))
    )
    (net (code "116") (name "OUT6") (class "Default")
      (node (ref "IC13") (pin "8") (pinfunction "O_8") (pintype "output"))
      (node (ref "ST14") (pin "7") (pinfunction "7_7") (pintype "passive"))
    )
    (net (code "118") (name "PA0_COM4-TX") (class "Default")
      (node (ref "IC1") (pin "23") (pinfunction "PA0_23") (pintype "bidirectional"))
      (node (ref "IC18") (pin "10") (pinfunction "T3IN_10") (pintype "input"))
    )
    (net (code "119") (name "PA1_COM4-RX") (class "Default")
      (node (ref "IC1") (pin "24") (pinfunction "PA1_24") (pintype "bidirectional"))
      (node (ref "IC18") (pin "12") (pinfunction "R3OUT_12") (pintype "output"))
    )
    (net (code "120") (name "PA2_RL1") (class "Default")
      (node (ref "IC1") (pin "25") (pinfunction "PA2_25") (pintype "bidirectional"))
      (node (ref "IC7") (pin "1") (pinfunction "G_1") (pintype "bidirectional"))
    )
    (net (code "121") (name "PA3_RL2") (class "Default")
      (node (ref "IC1") (pin "26") (pinfunction "PA3_26") (pintype "bidirectional"))
      (node (ref "IC14") (pin "1") (pinfunction "G_1") (pintype "bidirectional"))
    )
    (net (code "122") (name "PA4_RL3") (class "Default")
      (node (ref "IC1") (pin "29") (pinfunction "PA4_29") (pintype "bidirectional"))
      (node (ref "IC16") (pin "1") (pinfunction "G_1") (pintype "bidirectional"))
    )
    (net (code "123") (name "PA5_OUT4") (class "Default")
      (node (ref "IC1") (pin "30") (pinfunction "PA5_30") (pintype "bidirectional"))
      (node (ref "IC13") (pin "1") (pinfunction "I_1") (pintype "input"))
    )
    (net (code "124") (name "PA6_OUT5") (class "Default")
      (node (ref "IC1") (pin "31") (pinfunction "PA6_31") (pintype "bidirectional"))
      (node (ref "IC13") (pin "3") (pinfunction "I_3") (pintype "input"))
    )
    (net (code "125") (name "PA7_OUT6") (class "Default")
      (node (ref "IC1") (pin "32") (pinfunction "PA7_32") (pintype "bidirectional"))
      (node (ref "IC13") (pin "5") (pinfunction "I_5") (pintype "input"))
    )
    (net (code "126") (name "PA8_SDCARD-WP") (class "Default")
      (node (ref "IC1") (pin "67") (pinfunction "PA8_67") (pintype "bidirectional"))
    )
    (net (code "127") (name "PA9_RS422-TX") (class "Default")
      (node (ref "IC1") (pin "68") (pinfunction "PA9_68") (pintype "bidirectional"))
      (node (ref "IC10") (pin "9") (pinfunction "I_9") (pintype "input"))
    )
    (net (code "128") (name "PA10_RS422-RX") (class "Default")
      (node (ref "IC1") (pin "69") (pinfunction "PA10_69") (pintype "bidirectional"))
      (node (ref "IC10") (pin "4") (pinfunction "O_4") (pintype "output"))
      (node (ref "R71") (pin "2") (pinfunction "2_2") (pintype "passive"))
    )
    (net (code "129") (name "PA11_USB-DEBUG-D-") (class "Default")
      (node (ref "IC1") (pin "70") (pinfunction "PA11_70") (pintype "bidirectional"))
      (node (ref "R34") (pin "2") (pinfunction "2_2") (pintype "passive"))
    )
    (net (code "130") (name "PA12_USB-DEBUG-D+") (class "Default")
      (node (ref "IC1") (pin "71") (pinfunction "PA12_71") (pintype "bidirectional"))
      (node (ref "R35") (pin "2") (pinfunction "2_2") (pintype "passive"))
    )
    (net (code "131") (name "PA13_SWDIO") (class "Default")
      (node (ref "IC1") (pin "72") (pinfunction "PA13_72") (pintype "bidirectional"))
      (node (ref "ST12") (pin "3") (pinfunction "3_3") (pintype "passive"))
    )
    (net (code "132") (name "PA14_SWCLK") (class "Default")
      (node (ref "IC1") (pin "76") (pinfunction "PA14_76") (pintype "bidirectional"))
      (node (ref "ST12") (pin "4") (pinfunction "4_4") (pintype "passive"))
    )
    (net (code "133") (name "PA15_BUZZER") (class "Default")
      (node (ref "IC1") (pin "77") (pinfunction "PA15_77") (pintype "bidirectional"))
      (node (ref "R11") (pin "1") (pinfunction "1_1") (pintype "passive"))
    )
    (net (code "134") (name "PB0_OUT7") (class "Default")
      (node (ref "IC1") (pin "35") (pinfunction "PB0_35") (pintype "bidirectional"))
      (node (ref "ST14") (pin "9") (pinfunction "9_9") (pintype "passive"))
    )
    (net (code "135") (name "PB1") (class "Default")
      (node (ref "IC1") (pin "36") (pinfunction "PB1_36") (pintype "bidirectional"))
      (node (ref "ST14") (pin "11") (pinfunction "11_11") (pintype "passive"))
    )
    (net (code "136") (name "PB3_SPI1-CLK") (class "Default")
      (node (ref "IC1") (pin "89") (pinfunction "PB3_89") (pintype "bidirectional"))
      (node (ref "ST12") (pin "9") (pinfunction "9_9") (pintype "passive"))
      (node (ref "ST8") (pin "3") (pinfunction "S_3") (pintype "passive"))
    )
    (net (code "137") (name "PB4_SPI1-MISO") (class "Default")
      (node (ref "IC1") (pin "90") (pinfunction "PB4_90") (pintype "bidirectional"))
      (node (ref "ST12") (pin "10") (pinfunction "10_10") (pintype "passive"))
      (node (ref "ST8") (pin "4") (pinfunction "S_4") (pintype "passive"))
    )
    (net (code "138") (name "PB5_SPI1-MOSI") (class "Default")
      (node (ref "IC1") (pin "91") (pinfunction "PB5_91") (pintype "bidirectional"))
      (node (ref "R70") (pin "2") (pinfunction "2_2") (pintype "passive"))
      (node (ref "ST12") (pin "11") (pinfunction "11_11") (pintype "passive"))
      (node (ref "ST8") (pin "5") (pinfunction "S_5") (pintype "passive"))
    )
    (net (code "139") (name "PB6_I2C1-SCL") (class "Default")
      (node (ref "C59") (pin "1") (pinfunction "1_1") (pintype "passive"))
      (node (ref "IC1") (pin "92") (pinfunction "PB6_92") (pintype "bidirectional"))
      (node (ref "IC15") (pin "1") (pinfunction "SX_1") (pintype "input"))
      (node (ref "IC3") (pin "6") (pinfunction "SCL_6") (pintype "input"))
      (node (ref "R8") (pin "1") (pinfunction "1_1") (pintype "passive"))
    )
    (net (code "140") (name "PB7_I2C1-SDA") (class "Default")
      (node (ref "C58") (pin "1") (pinfunction "1_1") (pintype "passive"))
      (node (ref "IC1") (pin "93") (pinfunction "PB7_93") (pintype "bidirectional"))
      (node (ref "IC15") (pin "7") (pinfunction "SY_7") (pintype "input"))
      (node (ref "IC3") (pin "5") (pinfunction "SDA_5") (pintype "bidirectional"))
      (node (ref "R12") (pin "1") (pinfunction "1_1") (pintype "passive"))
    )
    (net (code "141") (name "PB8") (class "Default")
      (node (ref "IC1") (pin "95") (pinfunction "PB8_95") (pintype "bidirectional"))
      (node (ref "ST14") (pin "12") (pinfunction "12_12") (pintype "passive"))
    )
    (net (code "142") (name "PB9") (class "Default")
      (node (ref "IC1") (pin "96") (pinfunction "PB9_96") (pintype "bidirectional"))
      (node (ref "ST14") (pin "14") (pinfunction "14_14") (pintype "passive"))
    )
    (net (code "143") (name "PB10_SPI2-CLK") (class "Default")
      (node (ref "IC1") (pin "47") (pinfunction "PB10_47") (pintype "bidirectional"))
      (node (ref "IC4") (pin "8") (pinfunction "SCK_8") (pintype "input"))
    )
    (net (code "144") (name "PB11") (class "Default")
      (node (ref "IC1") (pin "48") (pinfunction "PB11_48") (pintype "bidirectional"))
      (node (ref "R69") (pin "2") (pinfunction "2_2") (pintype "passive"))
      (node (ref "ST14") (pin "13") (pinfunction "13_13") (pintype "passive"))
    )
    (net (code "145") (name "PB12_CAN2-RX") (class "Default")
      (node (ref "IC1") (pin "51") (pinfunction "PB12_51") (pintype "bidirectional"))
      (node (ref "ST12") (pin "7") (pinfunction "7_7") (pintype "passive"))
    )
    (net (code "146") (name "PB13_CAN2-TX") (class "Default")
      (node (ref "IC1") (pin "52") (pinfunction "PB13_52") (pintype "bidirectional"))
      (node (ref "ST12") (pin "8") (pinfunction "8_8") (pintype "passive"))
    )
    (net (code "147") (name "PB14_USBHOST-D-") (class "Default")
      (node (ref "IC1") (pin "53") (pinfunction "PB14_53") (pintype "bidirectional"))
      (node (ref "IC17") (pin "3") (pinfunction "I/O2_3") (pintype "bidirectional"))
    )
    (net (code "148") (name "PB15_USBHODT-D+") (class "Default")
      (node (ref "IC1") (pin "54") (pinfunction "PB15_54") (pintype "bidirectional"))
      (node (ref "IC17") (pin "1") (pinfunction "I/O1_1") (pintype "bidirectional"))
    )
    (net (code "149") (name "PC2_SPI2-MISO") (class "Default")
      (node (ref "IC1") (pin "17") (pinfunction "PC2_17") (pintype "bidirectional"))
      (node (ref "IC4") (pin "6") (pinfunction "SO_6") (pintype "output"))
    )
    (net (code "150") (name "PC3_SPI2-MOSI") (class "Default")
      (node (ref "IC1") (pin "18") (pinfunction "PC3_18") (pintype "bidirectional"))
      (node (ref "IC4") (pin "7") (pinfunction "SI_7") (pintype "input"))
    )
    (net (code "151") (name "PC4_RS422-EN") (class "Default")
      (node (ref "IC1") (pin "33") (pinfunction "PC4_33") (pintype "bidirectional"))
      (node (ref "IC10") (pin "13") (pinfunction "I_13") (pintype "input"))
      (node (ref "R51") (pin "2") (pinfunction "2_2") (pintype "passive"))
    )
    (net (code "152") (name "PC5_USB-VBUS") (class "Default")
      (node (ref "D1") (pin "3") (pinfunction "C_3") (pintype "passive"))
      (node (ref "IC1") (pin "34") (pinfunction "PC5_34") (pintype "bidirectional"))
    )
    (net (code "153") (name "PC6_USB-PSW") (class "Default")
      (node (ref "IC1") (pin "63") (pinfunction "PC6_63") (pintype "bidirectional"))
      (node (ref "IC2") (pin "4") (pinfunction "~{EN}_4") (pintype "bidirectional"))
      (node (ref "R1") (pin "2") (pinfunction "2_2") (pintype "passive"))
    )
    (net (code "154") (name "PC7_TFT-BACKLIGHT") (class "Default")
      (node (ref "IC1") (pin "64") (pinfunction "PC7_64") (pintype "bidirectional"))
      (node (ref "R36") (pin "1") (pinfunction "1_1") (pintype "passive"))
    )
    (net (code "155") (name "PC8_SDCARD-D0") (class "Default")
      (node (ref "IC1") (pin "65") (pinfunction "PC8_65") (pintype "bidirectional"))
      (node (ref "SD1") (pin "7") (pinfunction "DATA0/DO_7") (pintype "bidirectional"))
    )
    (net (code "156") (name "PC9_SDCARD-D1") (class "Default")
      (node (ref "IC1") (pin "66") (pinfunction "PC9_66") (pintype "bidirectional"))
      (node (ref "SD1") (pin "8") (pinfunction "DATA1_8") (pintype "bidirectional"))
    )
    (net (code "157") (name "PC10_SDCARD-D2") (class "Default")
      (node (ref "IC1") (pin "78") (pinfunction "PC10_78") (pintype "bidirectional"))
      (node (ref "SD1") (pin "1") (pinfunction "DATA2_1") (pintype "bidirectional"))
    )
    (net (code "158") (name "PC11_SDCARD-D3") (class "Default")
      (node (ref "IC1") (pin "79") (pinfunction "PC11_79") (pintype "bidirectional"))
      (node (ref "R68") (pin "2") (pinfunction "2_2") (pintype "passive"))
      (node (ref "SD1") (pin "2") (pinfunction "DATA3-CD/CS_2") (pintype "bidirectional"))
    )
    (net (code "159") (name "PC12_SDCARD-CLK") (class "Default")
      (node (ref "IC1") (pin "80") (pinfunction "PC12_80") (pintype "bidirectional"))
      (node (ref "SD1") (pin "5") (pinfunction "CLK_5") (pintype "bidirectional"))
    )
    (net (code "160") (name "PC13_ETH-~{RST}") (class "Default")
      (node (ref "IC1") (pin "7") (pinfunction "PC13_7") (pintype "bidirectional"))
      (node (ref "IC4") (pin "10") (pinfunction "~{RST}_10") (pintype "input"))
    )
    (net (code "161") (name "PD2_SDCARD-CMD") (class "Default")
      (node (ref "IC1") (pin "83") (pinfunction "PD2_83") (pintype "bidirectional"))
      (node (ref "SD1") (pin "3") (pinfunction "CMD/DI_3") (pintype "bidirectional"))
    )
    (net (code "162") (name "PD5_COM2-TX") (class "Default")
      (node (ref "IC1") (pin "86") (pinfunction "PD5_86") (pintype "bidirectional"))
      (node (ref "IC18") (pin "7") (pinfunction "T1IN_7") (pintype "input"))
    )
    (net (code "163") (name "PD6_COM2-RX") (class "Default")
      (node (ref "IC1") (pin "87") (pinfunction "PD6_87") (pintype "bidirectional"))
      (node (ref "IC18") (pin "14") (pinfunction "R1OUT_14") (pintype "output"))
    )
    (net (code "164") (name "PD7_USB-DETECT") (class "Default")
      (node (ref "IC1") (pin "88") (pinfunction "PD7_88") (pintype "bidirectional"))
      (node (ref "R28") (pin "1") (pinfunction "1_1") (pintype "passive"))
      (node (ref "R29") (pin "1") (pinfunction "1_1") (pintype "passive"))
    )
    (net (code "165") (name "PD8_COM3-TX") (class "Default")
      (node (ref "IC1") (pin "55") (pinfunction "PD8_55") (pintype "bidirectional"))
      (node (ref "IC18") (pin "8") (pinfunction "T2IN_8") (pintype "input"))
    )
    (net (code "166") (name "PD9_COM3-RX") (class "Default")
      (node (ref "IC1") (pin "56") (pinfunction "PD9_56") (pintype "bidirectional"))
      (node (ref "IC18") (pin "13") (pinfunction "R2OUT_13") (pintype "output"))
    )
    (net (code "167") (name "PD10_TFT-CS") (class "Default")
      (node (ref "IC1") (pin "57") (pinfunction "PD10_57") (pintype "bidirectional"))
      (node (ref "ST8") (pin "6") (pinfunction "S_6") (pintype "passive"))
    )
    (net (code "168") (name "PD11_IN-R") (class "Default")
      (node (ref "IC1") (pin "58") (pinfunction "PD11_58") (pintype "bidirectional"))
      (node (ref "IC12") (pin "2") (pinfunction "O_2") (pintype "output"))
    )
    (net (code "169") (name "PD12_IN1") (class "Default")
      (node (ref "IC1") (pin "59") (pinfunction "PD12_59") (pintype "bidirectional"))
      (node (ref "IC12") (pin "12") (pinfunction "O_12") (pintype "output"))
    )
    (net (code "170") (name "PD13_IN2") (class "Default")
      (node (ref "IC1") (pin "60") (pinfunction "PD13_60") (pintype "bidirectional"))
      (node (ref "IC12") (pin "10") (pinfunction "O_10") (pintype "output"))
    )
    (net (code "171") (name "PD14_IN3") (class "Default")
      (node (ref "IC1") (pin "61") (pinfunction "PD14_61") (pintype "bidirectional"))
      (node (ref "IC12") (pin "8") (pinfunction "O_8") (pintype "output"))
    )
    (net (code "172") (name "PE0") (class "Default")
      (node (ref "IC1") (pin "97") (pinfunction "PE0_97") (pintype "bidirectional"))
      (node (ref "ST14") (pin "4") (pinfunction "4_4") (pintype "passive"))
    )
    (net (code "173") (name "PE1_ETH-~{INT}") (class "Default")
      (node (ref "IC1") (pin "98") (pinfunction "PE1_98") (pintype "bidirectional"))
      (node (ref "IC4") (pin "4") (pinfunction "~{INT}_4") (pintype "output"))
    )
    (net (code "174") (name "PE2_ETH-CS") (class "Default")
      (node (ref "IC1") (pin "1") (pinfunction "PE2_1") (pintype "bidirectional"))
      (node (ref "IC4") (pin "9") (pinfunction "~{CS}_9") (pintype "input"))
    )
    (net (code "175") (name "PE3_LDR0") (class "Default")
      (node (ref "IC1") (pin "2") (pinfunction "PE3_2") (pintype "bidirectional"))
      (node (ref "JP8") (pin "1") (pinfunction "1_1") (pintype "passive"))
      (node (ref "R66") (pin "2") (pinfunction "2_2") (pintype "passive"))
    )
    (net (code "176") (name "PE4_LDR1") (class "Default")
      (node (ref "IC1") (pin "3") (pinfunction "PE4_3") (pintype "bidirectional"))
      (node (ref "JP10") (pin "1") (pinfunction "1_1") (pintype "passive"))
      (node (ref "R67") (pin "2") (pinfunction "2_2") (pintype "passive"))
    )
    (net (code "177") (name "PE5") (class "Default")
      (node (ref "IC1") (pin "4") (pinfunction "PE5_4") (pintype "bidirectional"))
      (node (ref "ST14") (pin "6") (pinfunction "6_6") (pintype "passive"))
    )
    (net (code "178") (name "PE6") (class "Default")
      (node (ref "IC1") (pin "5") (pinfunction "PE6_5") (pintype "bidirectional"))
      (node (ref "ST14") (pin "8") (pinfunction "8_8") (pintype "passive"))
    )
    (net (code "179") (name "PE7") (class "Default")
      (node (ref "IC1") (pin "38") (pinfunction "PE7_38") (pintype "bidirectional"))
      (node (ref "ST14") (pin "10") (pinfunction "10_10") (pintype "passive"))
    )
    (net (code "180") (name "PE8_SDCARD-CD") (class "Default")
      (node (ref "IC1") (pin "39") (pinfunction "PE8_39") (pintype "bidirectional"))
      (node (ref "R10") (pin "2") (pinfunction "2_2") (pintype "passive"))
      (node (ref "R9") (pin "2") (pinfunction "2_2") (pintype "passive"))
    )
    (net (code "181") (name "PE10_TFT-INT") (class "Default")
      (node (ref "IC1") (pin "41") (pinfunction "PE10_41") (pintype "bidirectional"))
      (node (ref "ST8") (pin "7") (pinfunction "S_7") (pintype "passive"))
    )
    (net (code "182") (name "PE12_TFT-RESET") (class "Default")
      (node (ref "IC1") (pin "43") (pinfunction "PE12_43") (pintype "bidirectional"))
      (node (ref "ST8") (pin "8") (pinfunction "S_8") (pintype "passive"))
    )
    (net (code "183") (name "PE13_SPI1.CS1") (class "Default")
      (node (ref "IC1") (pin "44") (pinfunction "PE13_44") (pintype "bidirectional"))
      (node (ref "ST12") (pin "12") (pinfunction "12_12") (pintype "passive"))
    )
    (net (code "184") (name "PE14_SPI1.CS2") (class "Default")
      (node (ref "IC1") (pin "45") (pinfunction "PE14_45") (pintype "bidirectional"))
      (node (ref "ST12") (pin "14") (pinfunction "14_14") (pintype "passive"))
    )
    (net (code "185") (name "PE15_SPI1.CS3") (class "Default")
      (node (ref "IC1") (pin "46") (pinfunction "PE15_46") (pintype "bidirectional"))
      (node (ref "ST12") (pin "13") (pinfunction "13_13") (pintype "passive"))
    )
    (net (code "186") (name "RX+") (class "Default")
      (node (ref "D6") (pin "1") (pinfunction "C_1") (pintype "passive"))
      (node (ref "IC9") (pin "9") (pinfunction "A_9") (pintype "bidirectional"))
      (node (ref "JP2") (pin "2") (pinfunction "2_2") (pintype "passive"))
      (node (ref "R55") (pin "1") (pinfunction "1_1") (pintype "passive"))
      (node (ref "ST6") (pin "3") (pinfunction "3_3") (pintype "passive"))
    )
    (net (code "187") (name "RX-") (class "Default")
      (node (ref "D8") (pin "1") (pinfunction "C_1") (pintype "passive"))
      (node (ref "IC9") (pin "8") (pinfunction "B_8") (pintype "bidirectional"))
      (node (ref "R52") (pin "2") (pinfunction "2_2") (pintype "passive"))
      (node (ref "R56") (pin "1") (pinfunction "1_1") (pintype "passive"))
      (node (ref "ST6") (pin "4") (pinfunction "4_4") (pintype "passive"))
    )
    (net (code "188") (name "RXD1") (class "Default")
      (node (ref "IC18") (pin "18") (pinfunction "R1IN_18") (pintype "input"))
      (node (ref "ST11") (pin "4") (pinfunction "4_4") (pintype "bidirectional"))
    )
    (net (code "189") (name "RXD2") (class "Default")
      (node (ref "IC18") (pin "17") (pinfunction "R2IN_17") (pintype "input"))
      (node (ref "ST10") (pin "4") (pinfunction "4_4") (pintype "bidirectional"))
    )
    (net (code "190") (name "RXD3") (class "Default")
      (node (ref "IC18") (pin "16") (pinfunction "R3IN_16") (pintype "input"))
      (node (ref "ST13") (pin "4") (pinfunction "4_4") (pintype "bidirectional"))
    )
    (net (code "191") (name "RXN") (class "Default")
      (node (ref "IC4") (pin "12") (pinfunction "TPIN-_12") (pintype "input"))
      (node (ref "R25") (pin "1") (pinfunction "1_1") (pintype "passive"))
      (node (ref "ST7") (pin "8") (pinfunction "RD-_8") (pintype "input"))
    )
    (net (code "192") (name "RXP") (class "Default")
      (node (ref "IC4") (pin "13") (pinfunction "TPIN+_13") (pintype "input"))
      (node (ref "R24") (pin "2") (pinfunction "2_2") (pintype "passive"))
      (node (ref "ST7") (pin "7") (pinfunction "RD+_7") (pintype "input"))
    )
    (net (code "193") (name "SCL_EXT") (class "Default")
      (node (ref "D17") (pin "2") (pinfunction "K2_2") (pintype "passive"))
      (node (ref "IC15") (pin "2") (pinfunction "RX_2") (pintype "input"))
      (node (ref "IC15") (pin "3") (pinfunction "TX_3") (pintype "output"))
      (node (ref "R30") (pin "2") (pinfunction "2_2") (pintype "passive"))
      (node (ref "ST12") (pin "5") (pinfunction "5_5") (pintype "passive"))
    )
    (net (code "194") (name "SDA_EXT") (class "Default")
      (node (ref "D17") (pin "1") (pinfunction "K1_1") (pintype "passive"))
      (node (ref "IC15") (pin "5") (pinfunction "TY_5") (pintype "output"))
      (node (ref "IC15") (pin "6") (pinfunction "RY_6") (pintype "input"))
      (node (ref "R20") (pin "2") (pinfunction "2_2") (pintype "passive"))
      (node (ref "ST12") (pin "6") (pinfunction "6_6") (pintype "passive"))
    )
    (net (code "195") (name "TX+") (class "Default")
      (node (ref "D4") (pin "1") (pinfunction "C_1") (pintype "passive"))
      (node (ref "IC9") (pin "6") (pinfunction "Y_6") (pintype "bidirectional"))
      (node (ref "JP3") (pin "2") (pinfunction "2_2") (pintype "passive"))
      (node (ref "ST6") (pin "1") (pinfunction "1_1") (pintype "passive"))
    )
    (net (code "196") (name "TX-") (class "Default")
      (node (ref "D5") (pin "1") (pinfunction "C_1") (pintype "passive"))
      (node (ref "IC9") (pin "7") (pinfunction "Z_7") (pintype "bidirectional"))
      (node (ref "R54") (pin "1") (pinfunction "1_1") (pintype "passive"))
      (node (ref "ST6") (pin "2") (pinfunction "2_2") (pintype "passive"))
    )
    (net (code "197") (name "TXD1") (class "Default")
      (node (ref "IC18") (pin "21") (pinfunction "T1OUT_21") (pintype "output"))
      (node (ref "ST11") (pin "3") (pinfunction "3_3") (pintype "bidirectional"))
    )
    (net (code "198") (name "TXD2") (class "Default")
      (node (ref "IC18") (pin "20") (pinfunction "T2OUT_20") (pintype "output"))
      (node (ref "ST10") (pin "3") (pinfunction "3_3") (pintype "bidirectional"))
    )
    (net (code "199") (name "TXD3") (class "Default")
      (node (ref "IC18") (pin "19") (pinfunction "T3OUT_19") (pintype "output"))
      (node (ref "ST13") (pin "3") (pinfunction "3_3") (pintype "bidirectional"))
    )
    (net (code "200") (name "TXN") (class "Default")
      (node (ref "IC4") (pin "16") (pinfunction "TPOUT-_16") (pintype "output"))
      (node (ref "R26") (pin "1") (pinfunction "1_1") (pintype "passive"))
      (node (ref "ST7") (pin "2") (pinfunction "TD-_2") (pintype "input"))
    )
    (net (code "201") (name "TXP") (class "Default")
      (node (ref "IC4") (pin "17") (pinfunction "TPOUT+_17") (pintype "output"))
      (node (ref "R27") (pin "2") (pinfunction "2_2") (pintype "passive"))
      (node (ref "ST7") (pin "1") (pinfunction "TD+_1") (pintype "input"))
    )
    (net (code "202") (name "VBAT") (class "Default")
      (node (ref "D16") (pin "3") (pinfunction "CC_3") (pintype "passive"))
      (node (ref "IC1") (pin "6") (pinfunction "VBAT_6") (pintype "bidirectional"))
    )
    (net (code "203") (name "VBAT-EXTERN") (class "Default")
      (node (ref "BAT1") (pin "+") (pinfunction "+_+") (pintype "passive"))
      (node (ref "D16") (pin "1") (pinfunction "A1_1") (pintype "passive"))
    )
    (net (code "204") (name "VCC") (class "Default")
      (node (ref "C31") (pin "+") (pinfunction "+_+") (pintype "passive"))
      (node (ref "C56") (pin "1") (pinfunction "1_1") (pintype "passive"))
      (node (ref "IC6") (pin "1") (pinfunction "VI_1") (pintype "input"))
      (node (ref "IC8") (pin "2") (pinfunction "VIN_2") (pintype "bidirectional"))
      (node (ref "LCL2") (pin "3") (pinfunction "2_3") (pintype "passive"))
    )
    (net (code "205") (name "VCCIO") (class "Default")
      (node (ref "C34") (pin "1") (pinfunction "1_1") (pintype "passive"))
      (node (ref "C38") (pin "+") (pinfunction "+_+") (pintype "passive"))
      (node (ref "C39") (pin "1") (pinfunction "1_1") (pintype "passive"))
      (node (ref "C45") (pin "+") (pinfunction "+_+") (pintype "passive"))
      (node (ref "C46") (pin "1") (pinfunction "1_1") (pintype "passive"))
      (node (ref "D3") (pin "C") (pinfunction "C_C") (pintype "passive"))
      (node (ref "D7") (pin "1") (pinfunction "A_1") (pintype "passive"))
      (node (ref "DC1") (pin "4") (pinfunction "+VOUT_4") (pintype "passive"))
      (node (ref "IC9") (pin "10") (pinfunction "VCC_10") (pintype "power_in"))
      (node (ref "OK1") (pin "2") (pinfunction "A_2") (pintype "passive"))
      (node (ref "OK2") (pin "8") (pinfunction "VCC_8") (pintype "passive"))
      (node (ref "OK3") (pin "8") (pinfunction "VCC_8") (pintype "passive"))
      (node (ref "R47") (pin "2") (pinfunction "2_2") (pintype "passive"))
      (node (ref "R48") (pin "2") (pinfunction "2_2") (pintype "passive"))
    )
    (net (code "206") (name "unconnected-(D7-C-Pad2)") (class "Default")
      (node (ref "D7") (pin "2") (pinfunction "C_2") (pintype "passive"))
    )
    (net (code "207") (name "unconnected-(IC1H-PC0-Pad15)") (class "Default")
      (node (ref "IC1") (pin "15") (pinfunction "PC0_15") (pintype "bidirectional"))
    )
    (net (code "208") (name "unconnected-(IC1H-PC1-Pad16)") (class "Default")
      (node (ref "IC1") (pin "16") (pinfunction "PC1_16") (pintype "bidirectional"))
    )
    (net (code "209") (name "unconnected-(IC1I-PD15-Pad62)") (class "Default")
      (node (ref "IC1") (pin "62") (pinfunction "PD15_62") (pintype "bidirectional"))
    )
    (net (code "210") (name "unconnected-(IC1J-PD0-Pad81)") (class "Default")
      (node (ref "IC1") (pin "81") (pinfunction "PD0_81") (pintype "bidirectional"))
    )
    (net (code "211") (name "unconnected-(IC1J-PD1-Pad82)") (class "Default")
      (node (ref "IC1") (pin "82") (pinfunction "PD1_82") (pintype "bidirectional"))
    )
    (net (code "212") (name "unconnected-(IC1J-PD3-Pad84)") (class "Default")
      (node (ref "IC1") (pin "84") (pinfunction "PD3_84") (pintype "bidirectional"))
    )
    (net (code "213") (name "unconnected-(IC1J-PD4-Pad85)") (class "Default")
      (node (ref "IC1") (pin "85") (pinfunction "PD4_85") (pintype "bidirectional"))
    )
    (net (code "214") (name "unconnected-(IC1K-PE9-Pad40)") (class "Default")
      (node (ref "IC1") (pin "40") (pinfunction "PE9_40") (pintype "bidirectional"))
    )
    (net (code "215") (name "unconnected-(IC1K-PE11-Pad42)") (class "Default")
      (node (ref "IC1") (pin "42") (pinfunction "PE11_42") (pintype "bidirectional"))
    )
    (net (code "216") (name "unconnected-(IC4-CLKOUT-Pad3)") (class "Default")
      (node (ref "IC4") (pin "3") (pinfunction "CLKOUT_3") (pintype "output"))
    )
    (net (code "217") (name "unconnected-(IC4-NC-Pad5)") (class "Default")
      (node (ref "IC4") (pin "5") (pinfunction "NC_5") (pintype "bidirectional"))
    )
    (net (code "218") (name "unconnected-(IC7-S-Pad2)") (class "Default")
      (node (ref "IC7") (pin "2") (pinfunction "S_2") (pintype "bidirectional"))
    )
    (net (code "219") (name "unconnected-(IC8-EN-Pad7)") (class "Default")
      (node (ref "IC8") (pin "7") (pinfunction "EN_7") (pintype "bidirectional"))
    )
    (net (code "220") (name "unconnected-(IC8-NC-Pad5)") (class "Default")
      (node (ref "IC8") (pin "5") (pinfunction "NC_5") (pintype "no_connect"))
    )
    (net (code "221") (name "unconnected-(IC12E-O-Pad4)") (class "Default")
      (node (ref "IC12") (pin "4") (pinfunction "O_4") (pintype "output"))
    )
    (net (code "222") (name "unconnected-(IC12F-O-Pad6)") (class "Default")
      (node (ref "IC12") (pin "6") (pinfunction "O_6") (pintype "output"))
    )
    (net (code "223") (name "unconnected-(IC14-S-Pad2)") (class "Default")
      (node (ref "IC14") (pin "2") (pinfunction "S_2") (pintype "bidirectional"))
    )
    (net (code "224") (name "unconnected-(IC16-S-Pad2)") (class "Default")
      (node (ref "IC16") (pin "2") (pinfunction "S_2") (pintype "bidirectional"))
    )
    (net (code "225") (name "unconnected-(IC18-~{INVALID}-Pad9)") (class "Default")
      (node (ref "IC18") (pin "9") (pinfunction "~{INVALID}_9") (pintype "output"))
    )
    (net (code "226") (name "unconnected-(OK1-VE-Pad7)") (class "Default")
      (node (ref "OK1") (pin "7") (pinfunction "VE_7") (pintype "passive"))
    )
    (net (code "227") (name "unconnected-(OK2-VE-Pad7)") (class "Default")
      (node (ref "OK2") (pin "7") (pinfunction "VE_7") (pintype "passive"))
    )
    (net (code "228") (name "unconnected-(OK3-VE-Pad7)") (class "Default")
      (node (ref "OK3") (pin "7") (pinfunction "VE_7") (pintype "passive"))
    )
    (net (code "229") (name "unconnected-(ST7-CR-Pad6)") (class "Default")
      (node (ref "ST7") (pin "6") (pinfunction "CR_6") (pintype "input"))
    )
    (net (code "230") (name "unconnected-(ST8B-S-Pad10)") (class "Default")
      (node (ref "ST8") (pin "10") (pinfunction "S_10") (pintype "passive"))
    )
    (net (code "231") (name "unconnected-(ST8C-S-Pad11)") (class "Default")
      (node (ref "ST8") (pin "11") (pinfunction "S_11") (pintype "passive"))
    )
    (net (code "232") (name "unconnected-(ST8D-S-Pad12)") (class "Default")
      (node (ref "ST8") (pin "12") (pinfunction "S_12") (pintype "passive"))
    )
    (net (code "233") (name "unconnected-(ST8E-S-Pad13)") (class "Default")
      (node (ref "ST8") (pin "13") (pinfunction "S_13") (pintype "passive"))
    )
    (net (code "234") (name "unconnected-(ST8F-S-Pad14)") (class "Default")
      (node (ref "ST8") (pin "14") (pinfunction "S_14") (pintype "passive"))
    )
    (net (code "235") (name "unconnected-(ST8G-S-Pad15)") (class "Default")
      (node (ref "ST8") (pin "15") (pinfunction "S_15") (pintype "passive"))
    )
    (net (code "236") (name "unconnected-(ST8H-S-Pad16)") (class "Default")
      (node (ref "ST8") (pin "16") (pinfunction "S_16") (pintype "passive"))
    )
    (net (code "237") (name "unconnected-(ST9-ID-Pad4)") (class "Default")
      (node (ref "ST9") (pin "4") (pinfunction "ID_4") (pintype "bidirectional"))
    )
    (net (code "238") (name "unconnected-(ST15-Pad4)") (class "Default")
      (node (ref "ST15") (pin "4") (pinfunction "4_4") (pintype "input"))
    )
    (net (code "239") (name "~{RST}") (class "Default")
      (node (ref "IC1") (pin "14") (pinfunction "NRST_14") (pintype "bidirectional"))
      (node (ref "R6") (pin "2") (pinfunction "2_2") (pintype "passive"))
      (node (ref "ST12") (pin "16") (pinfunction "16_16") (pintype "passive"))
    )
  )
)
